# ENERGIS_Rack-PDU_1_1_0.net
KiCad netlist of a schematic drawn in EAGLE
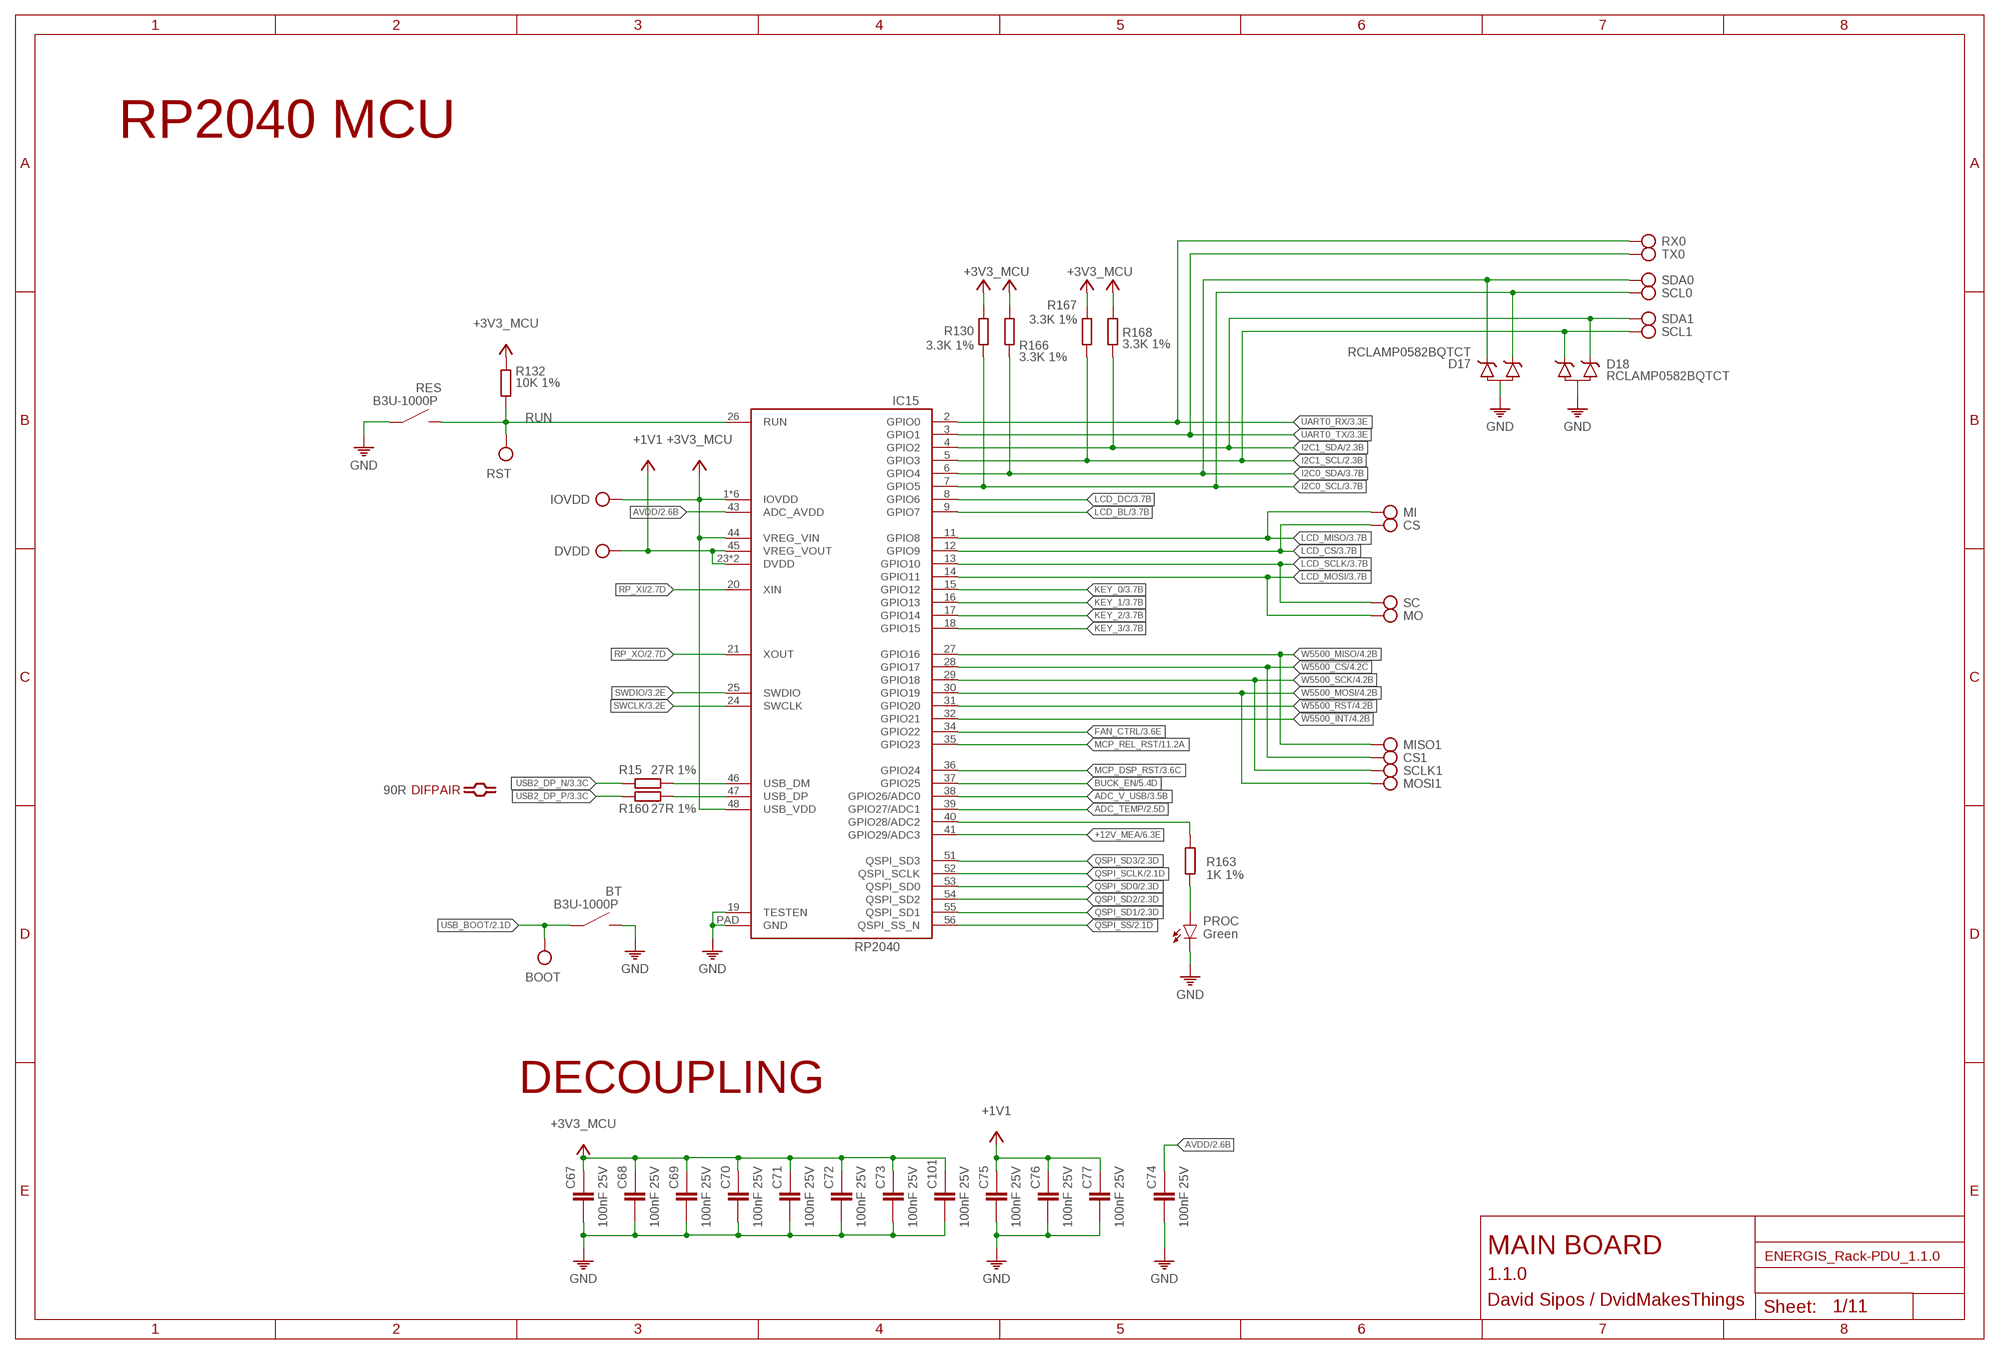
[diagram p0: schematic, sheet 1]
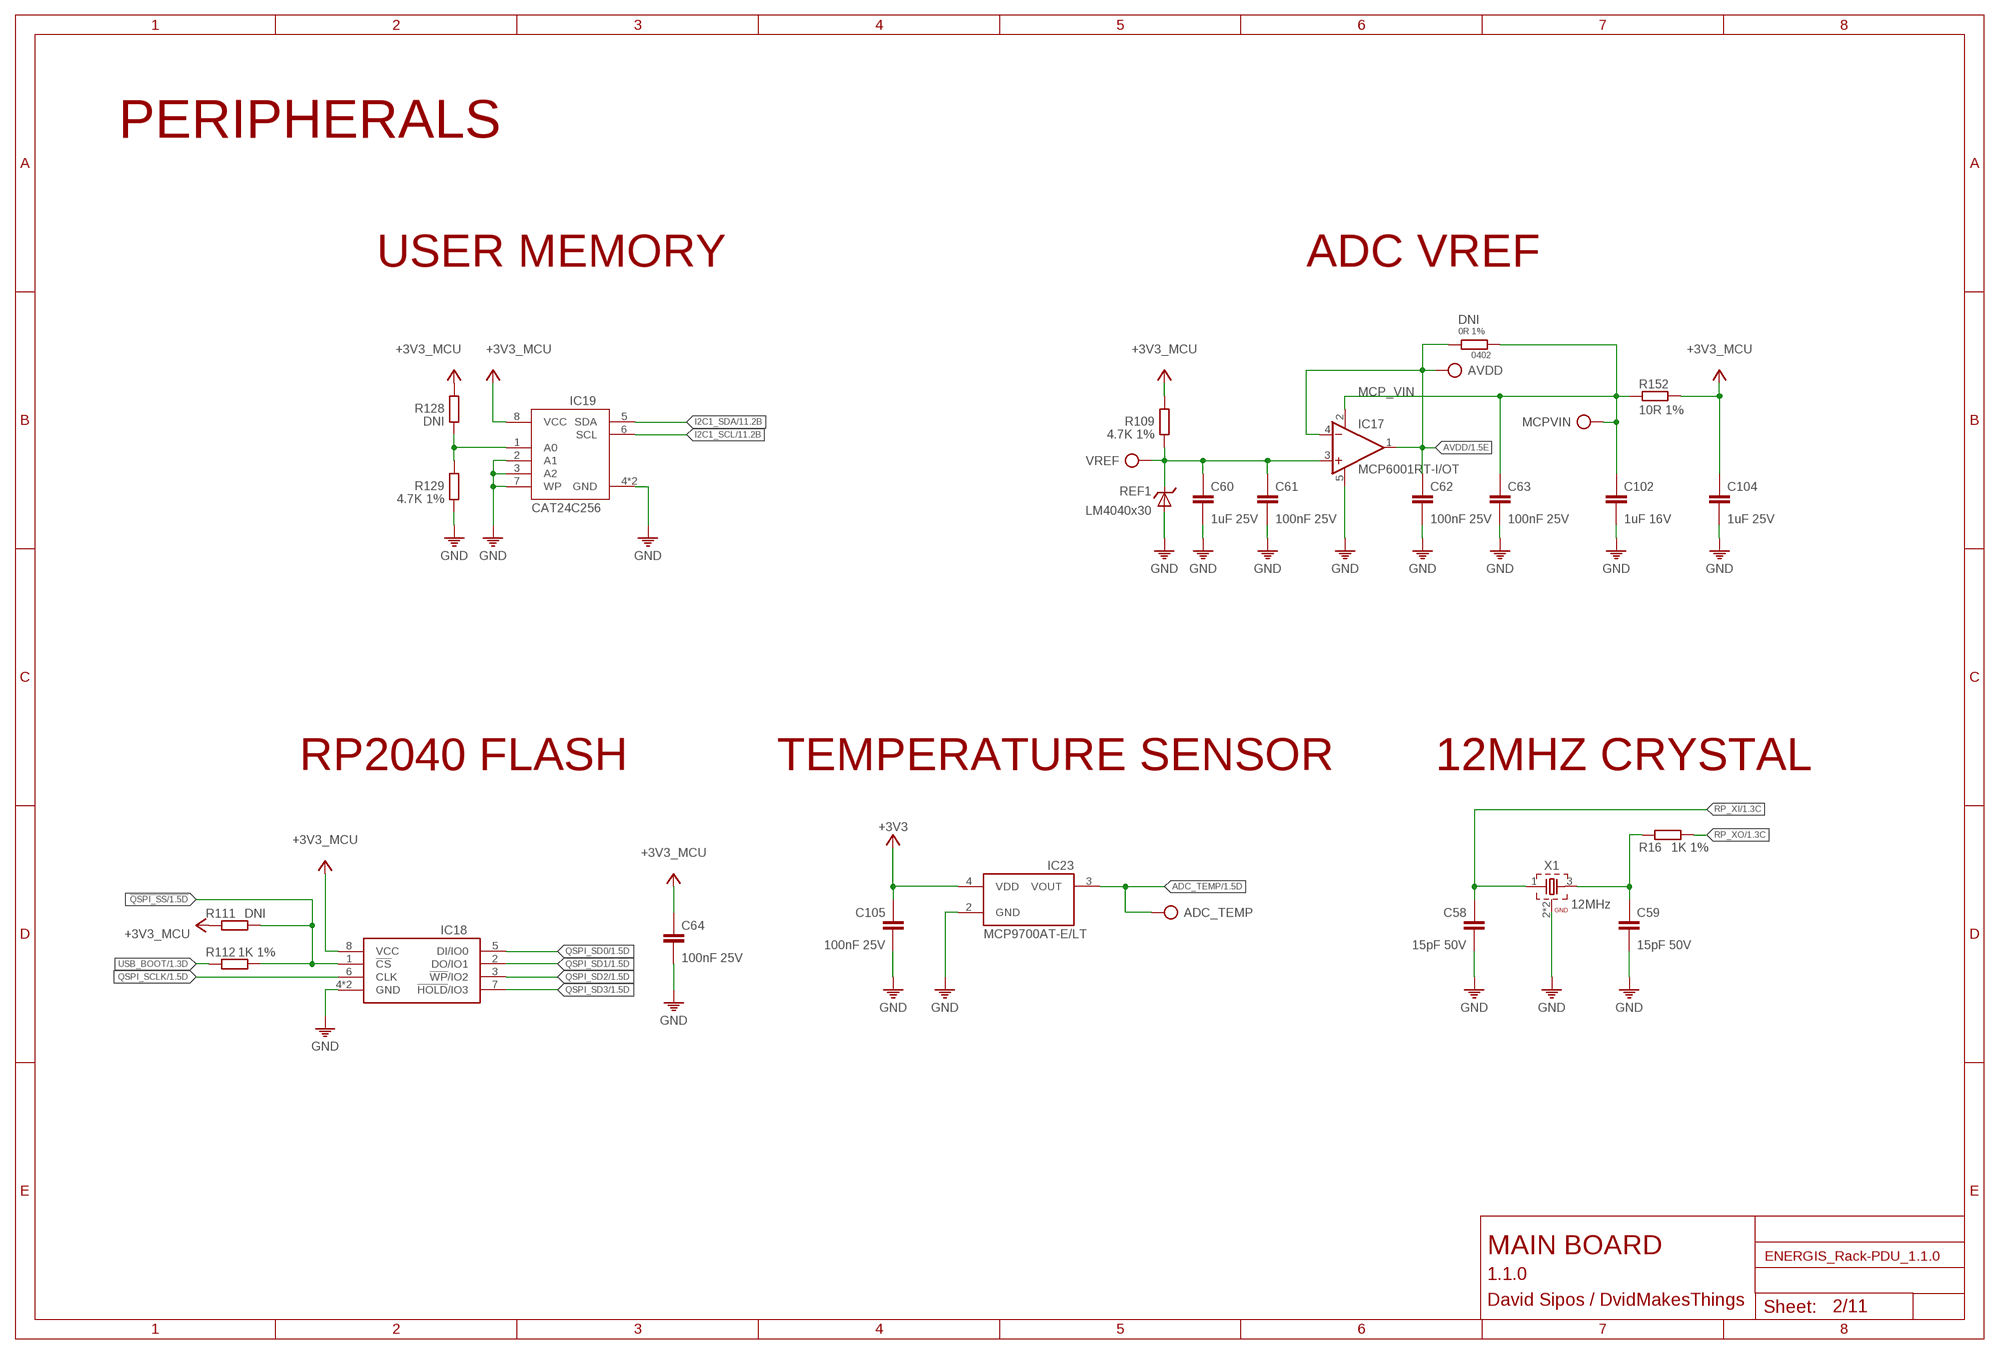
[diagram p1: schematic, sheet 2]
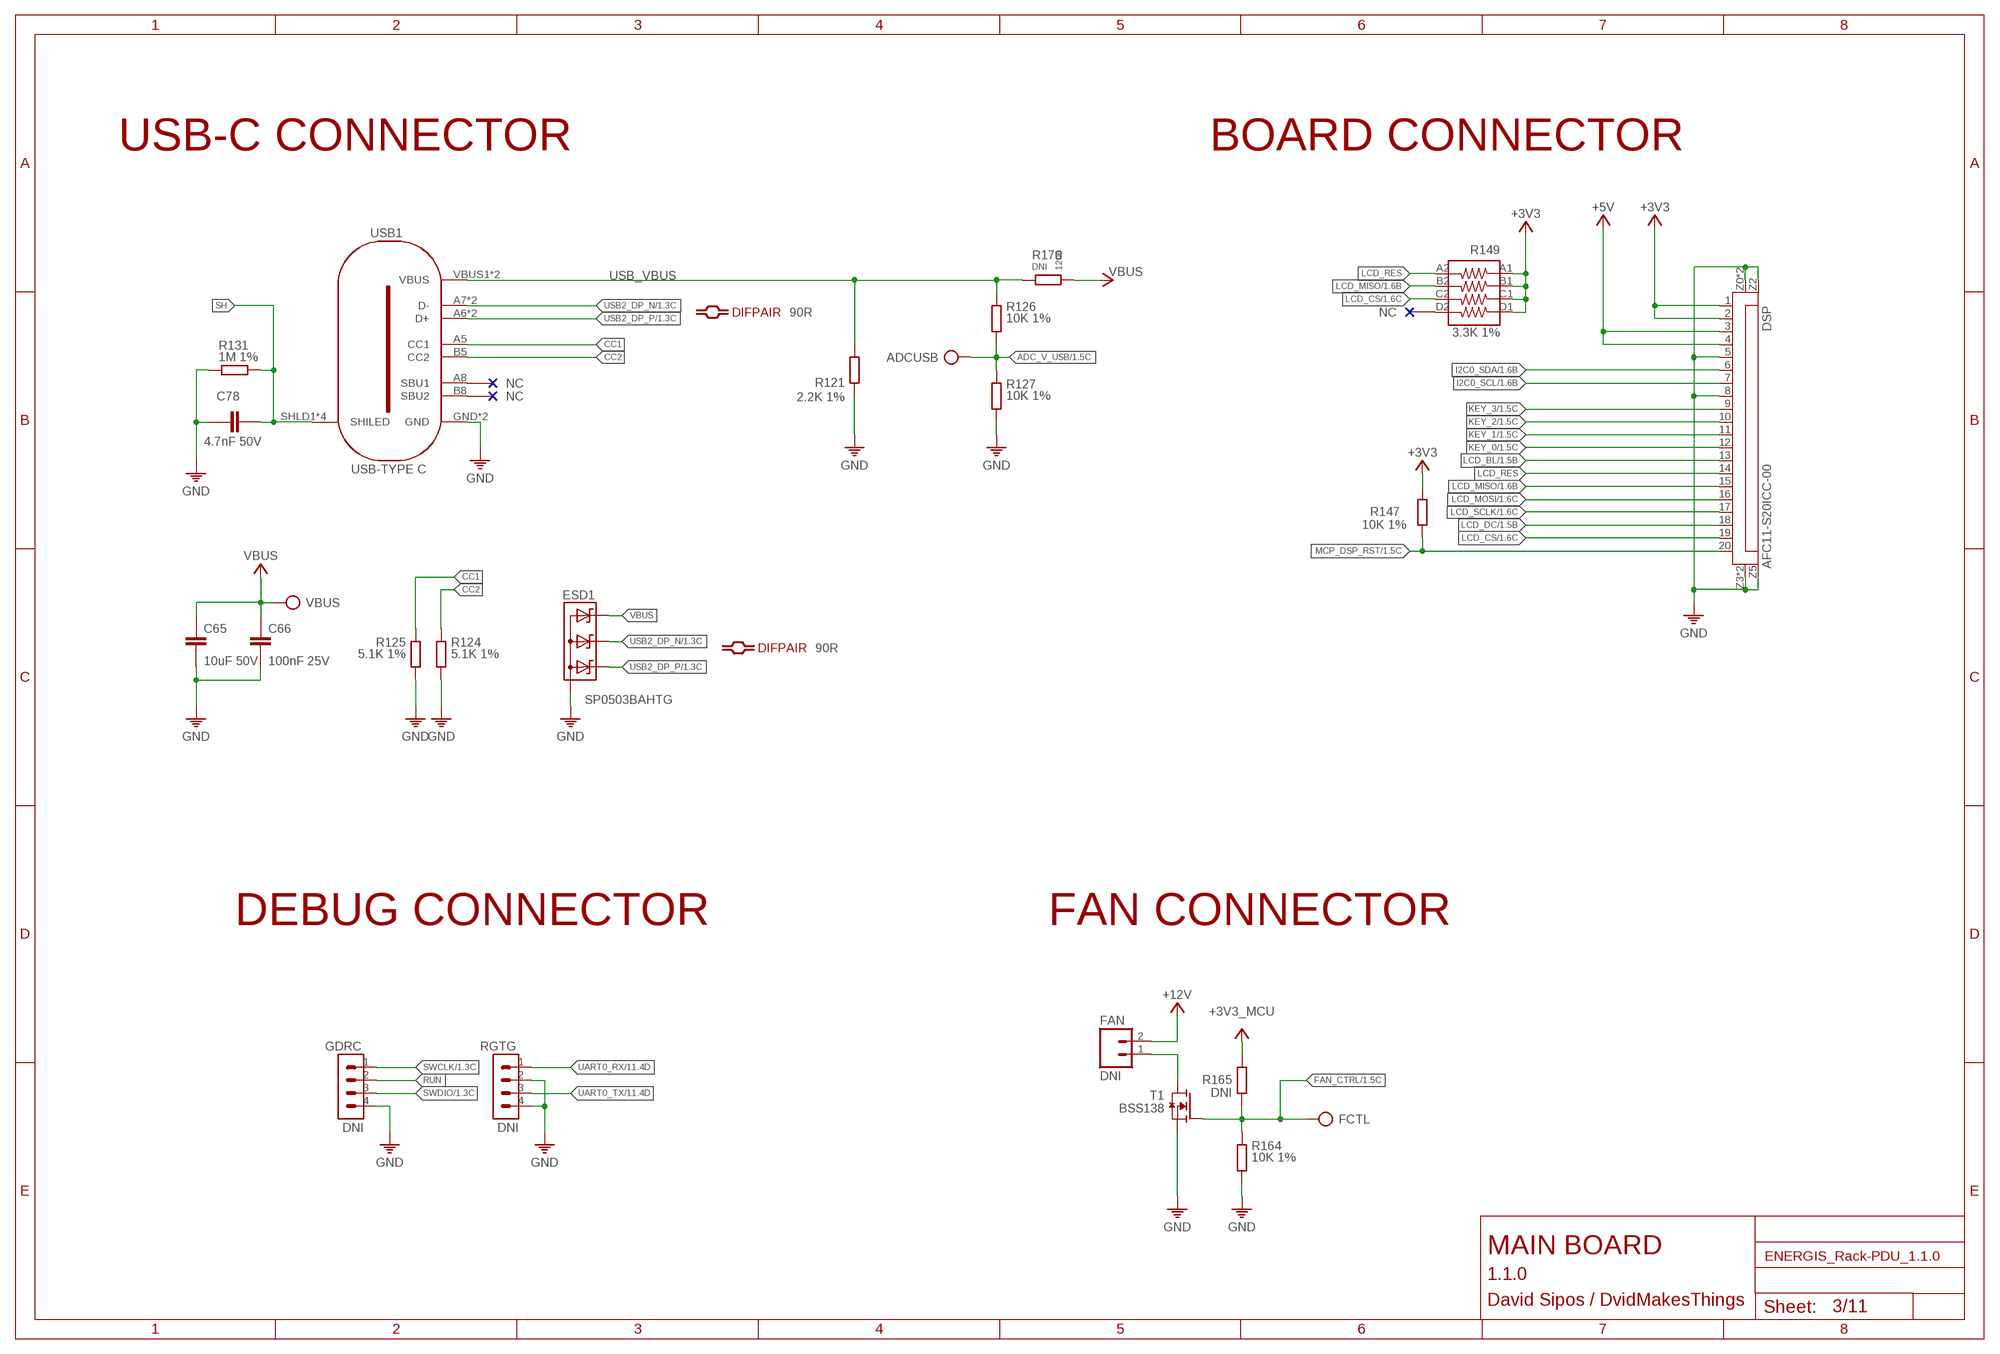
[diagram p2: schematic, sheet 3]
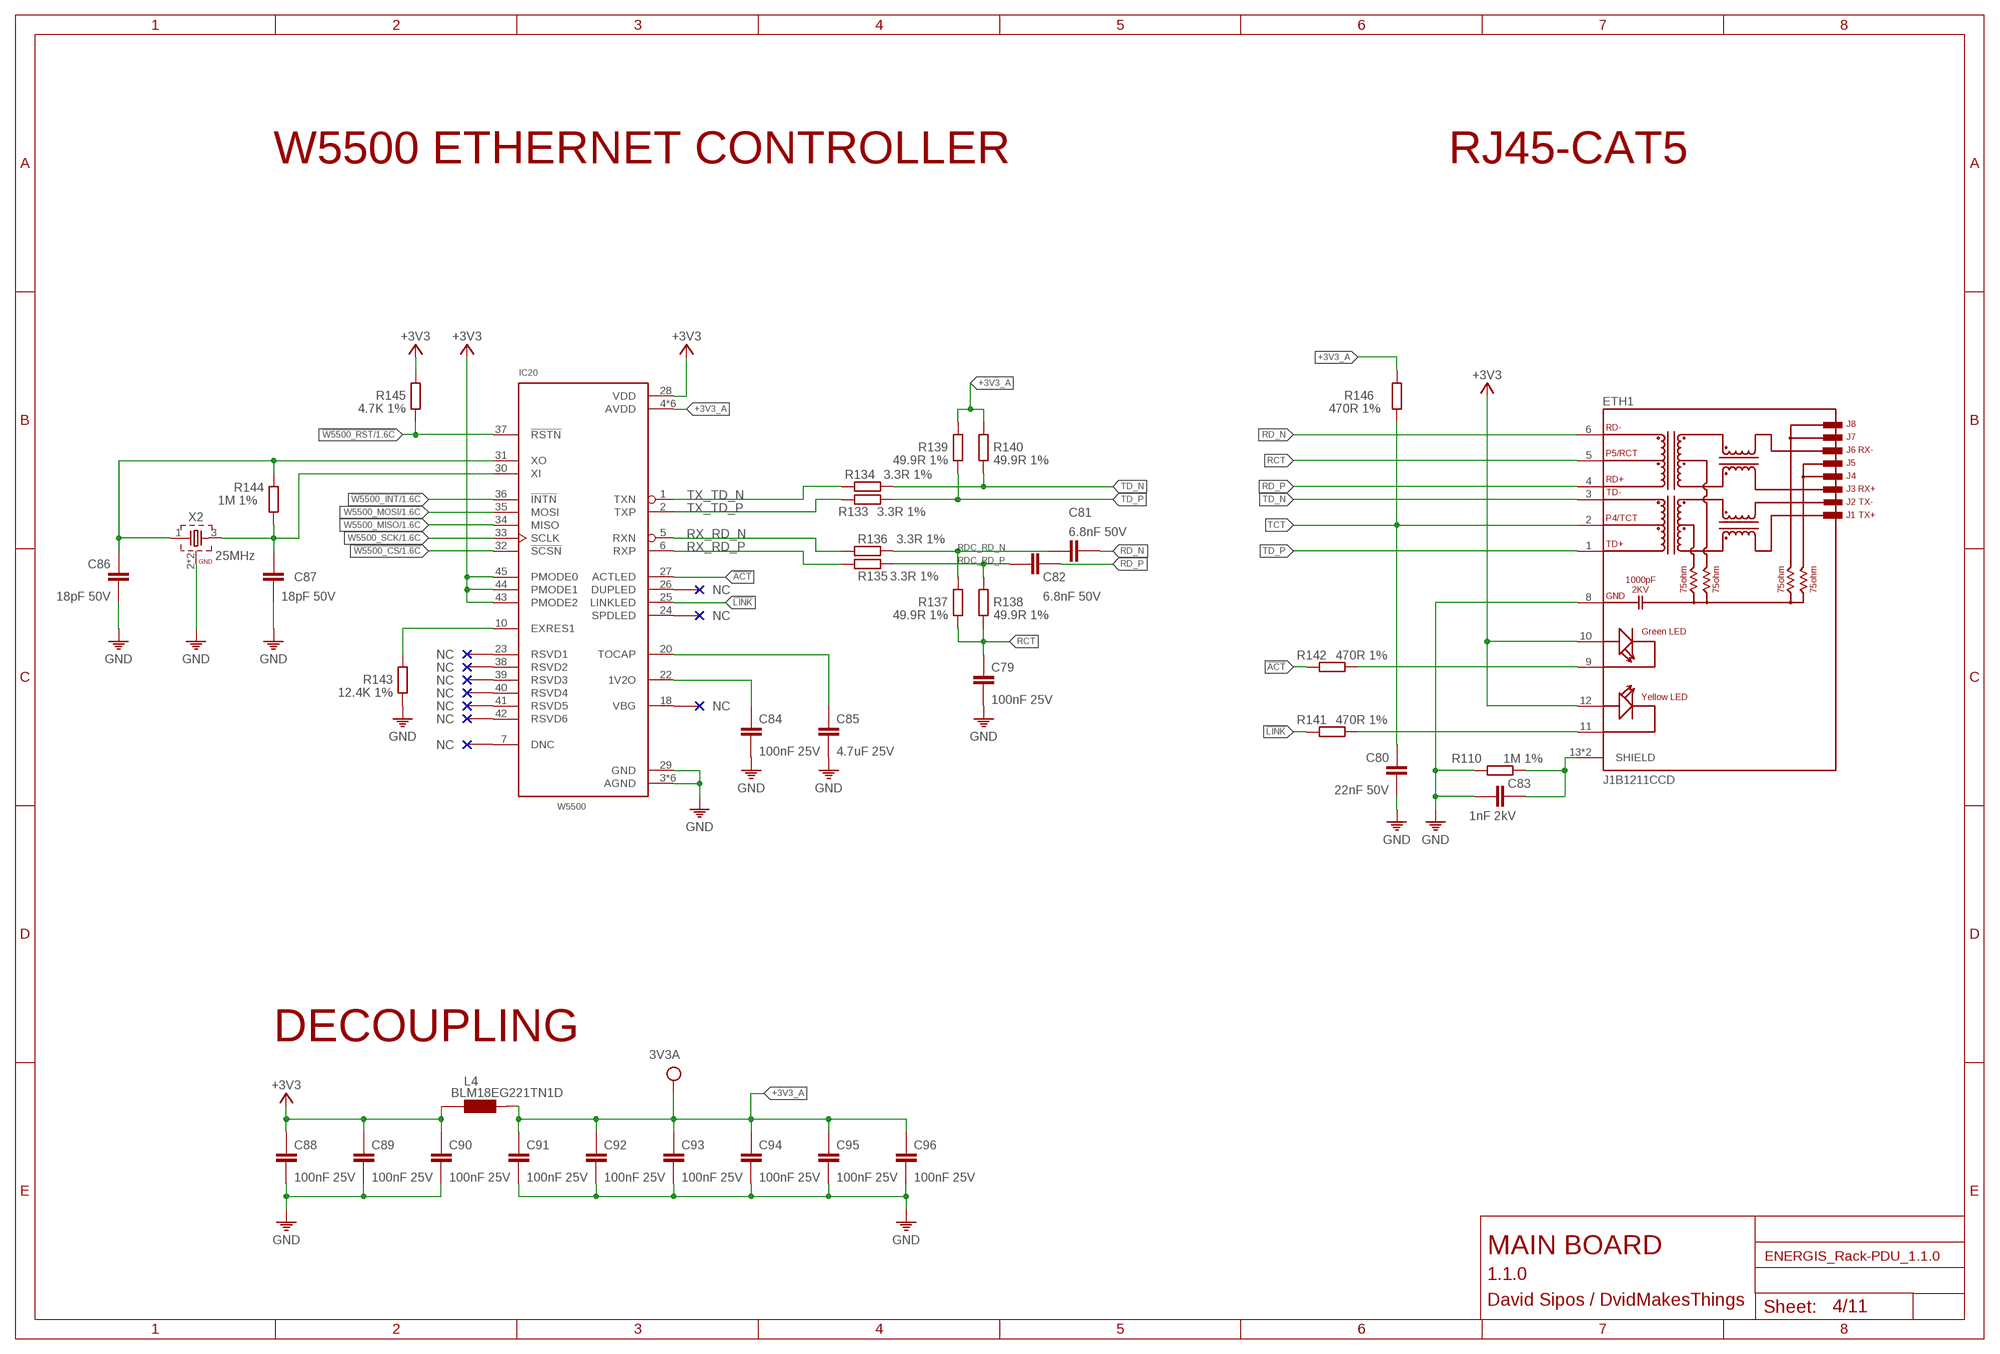
[diagram p3: schematic, sheet 4]
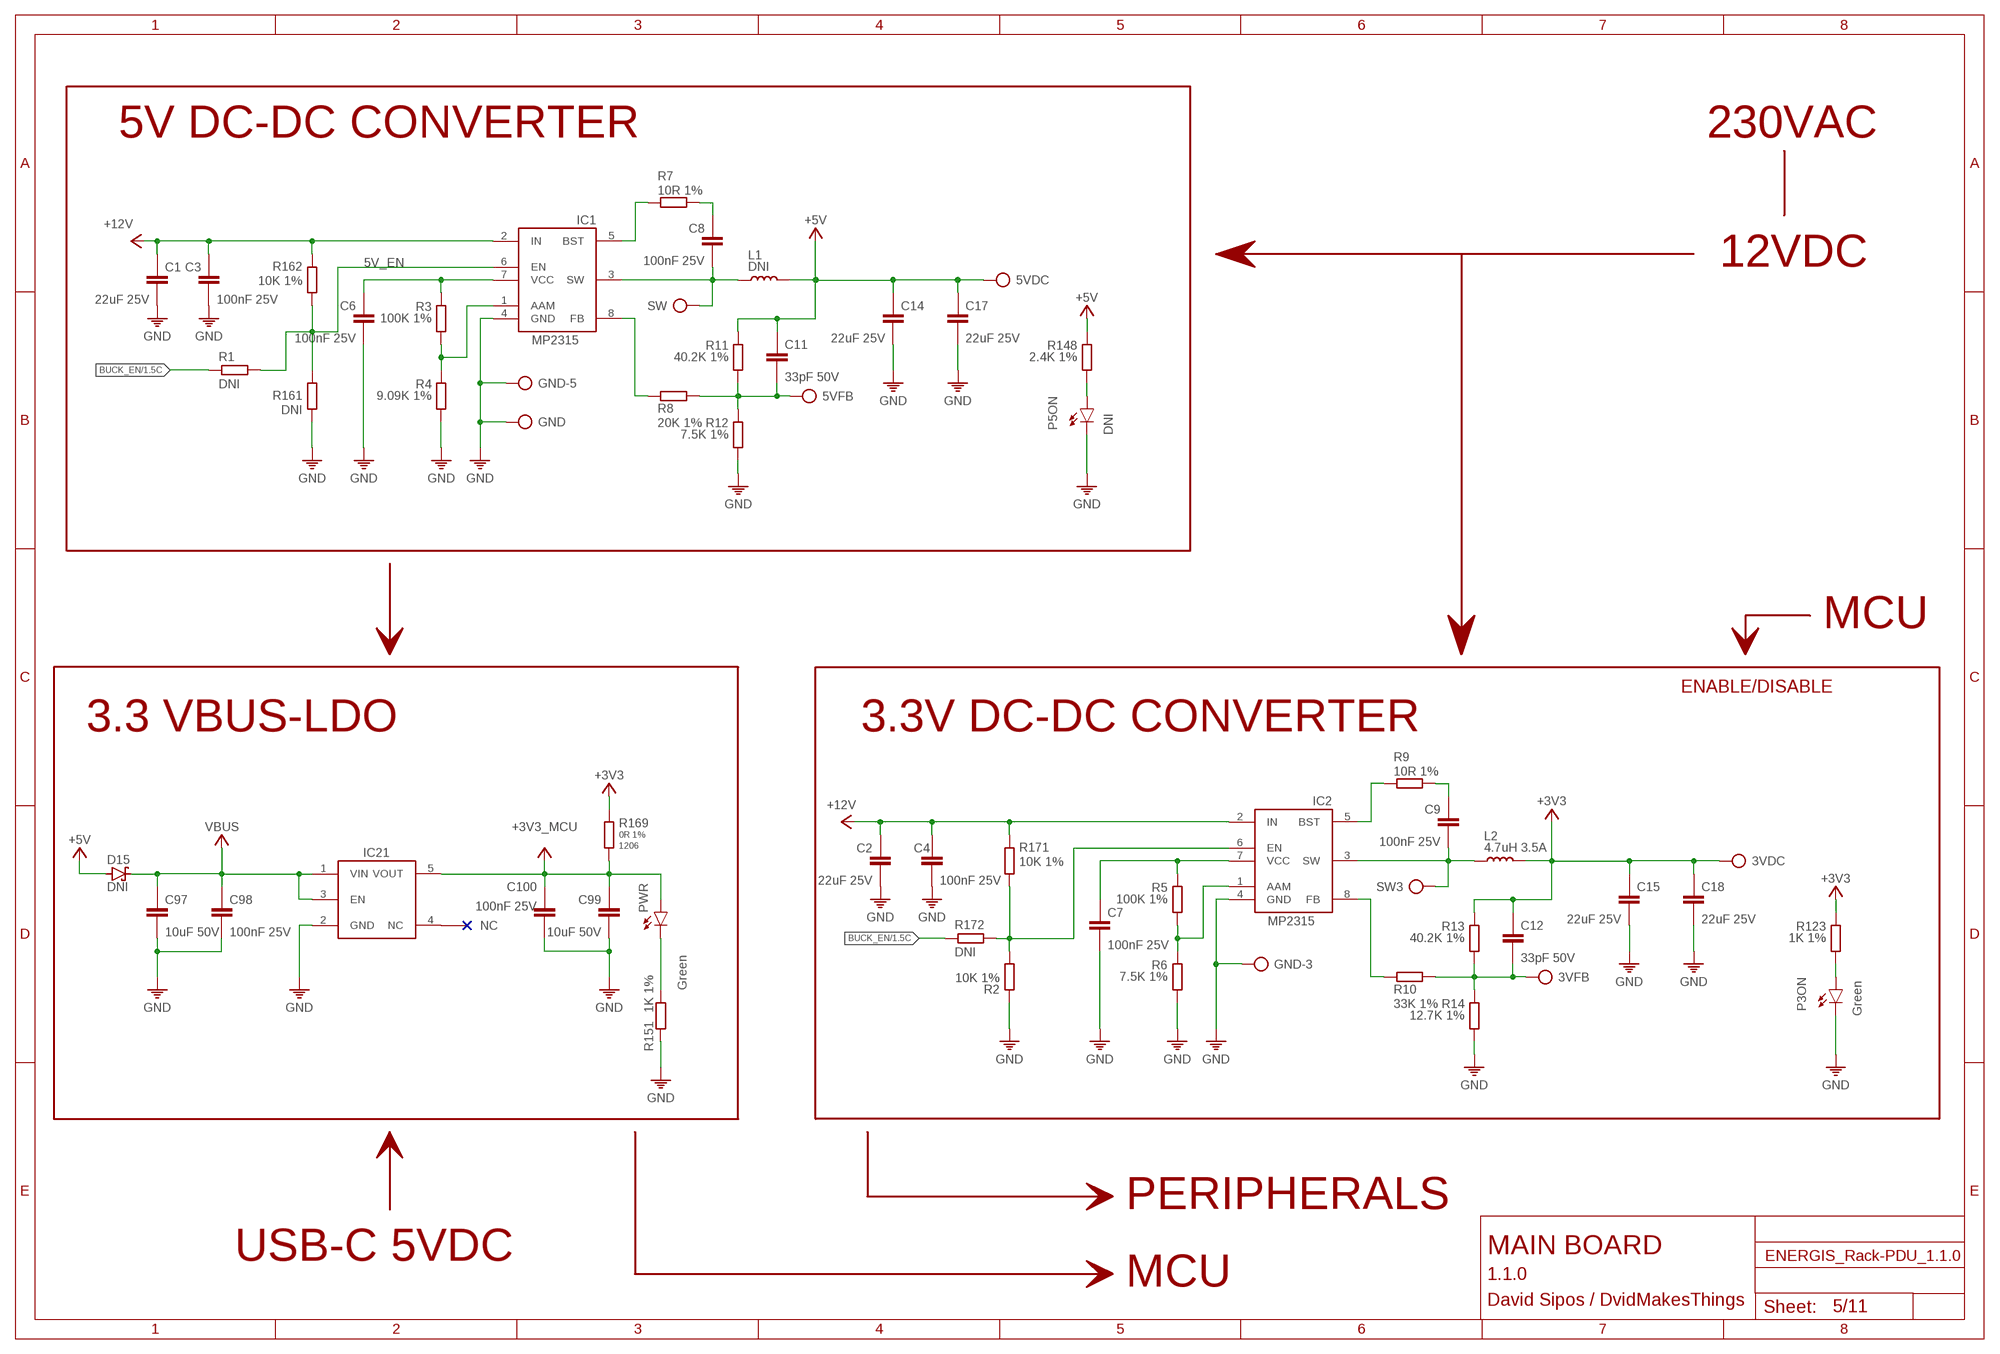
[diagram p4: schematic, sheet 5]
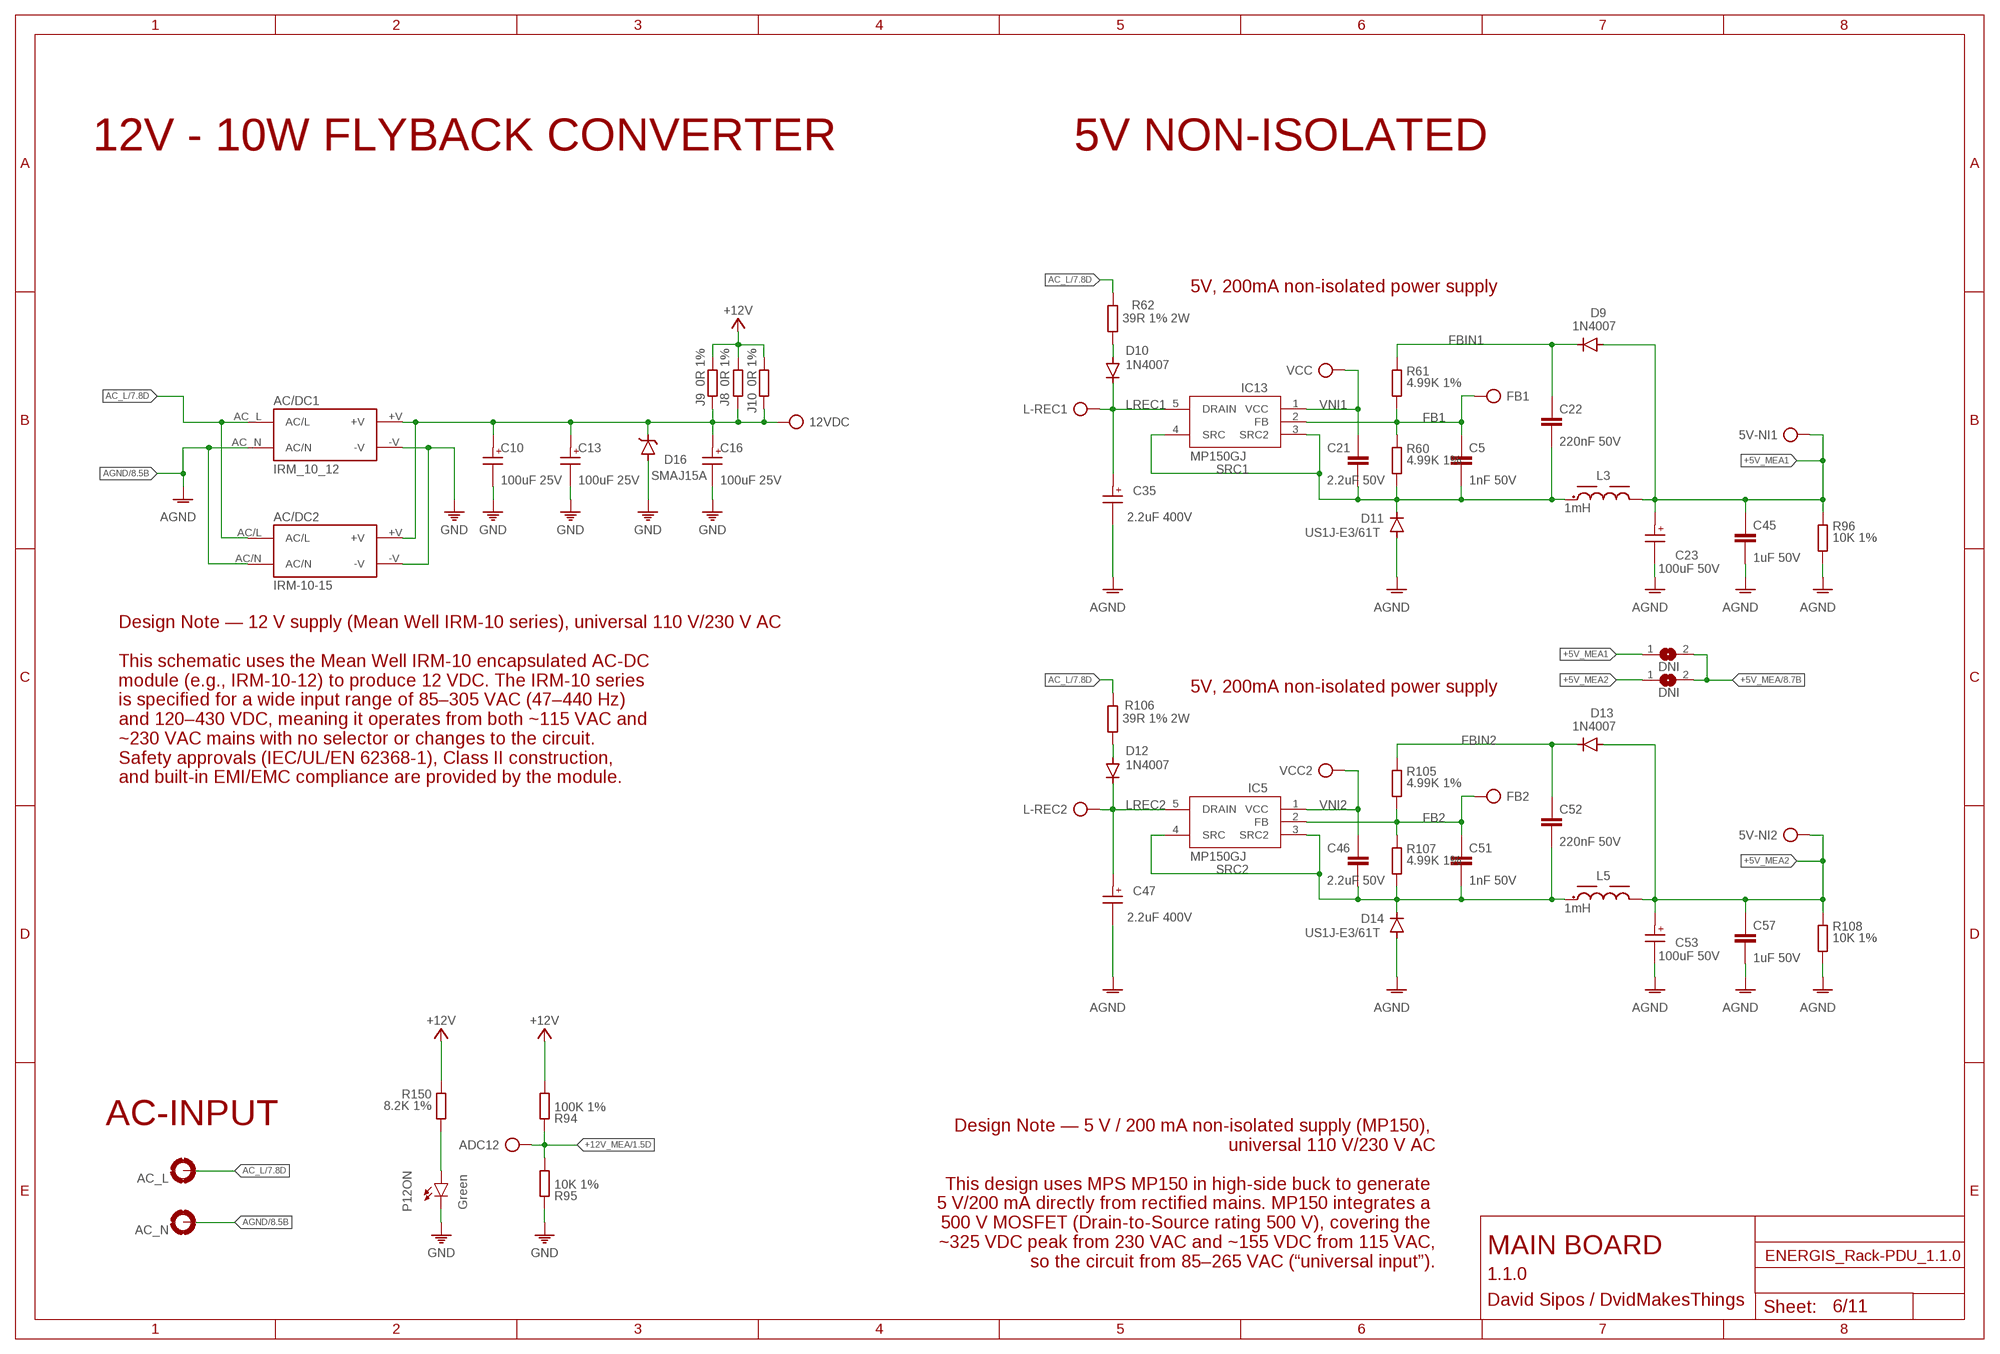
[diagram p5: schematic, sheet 6]
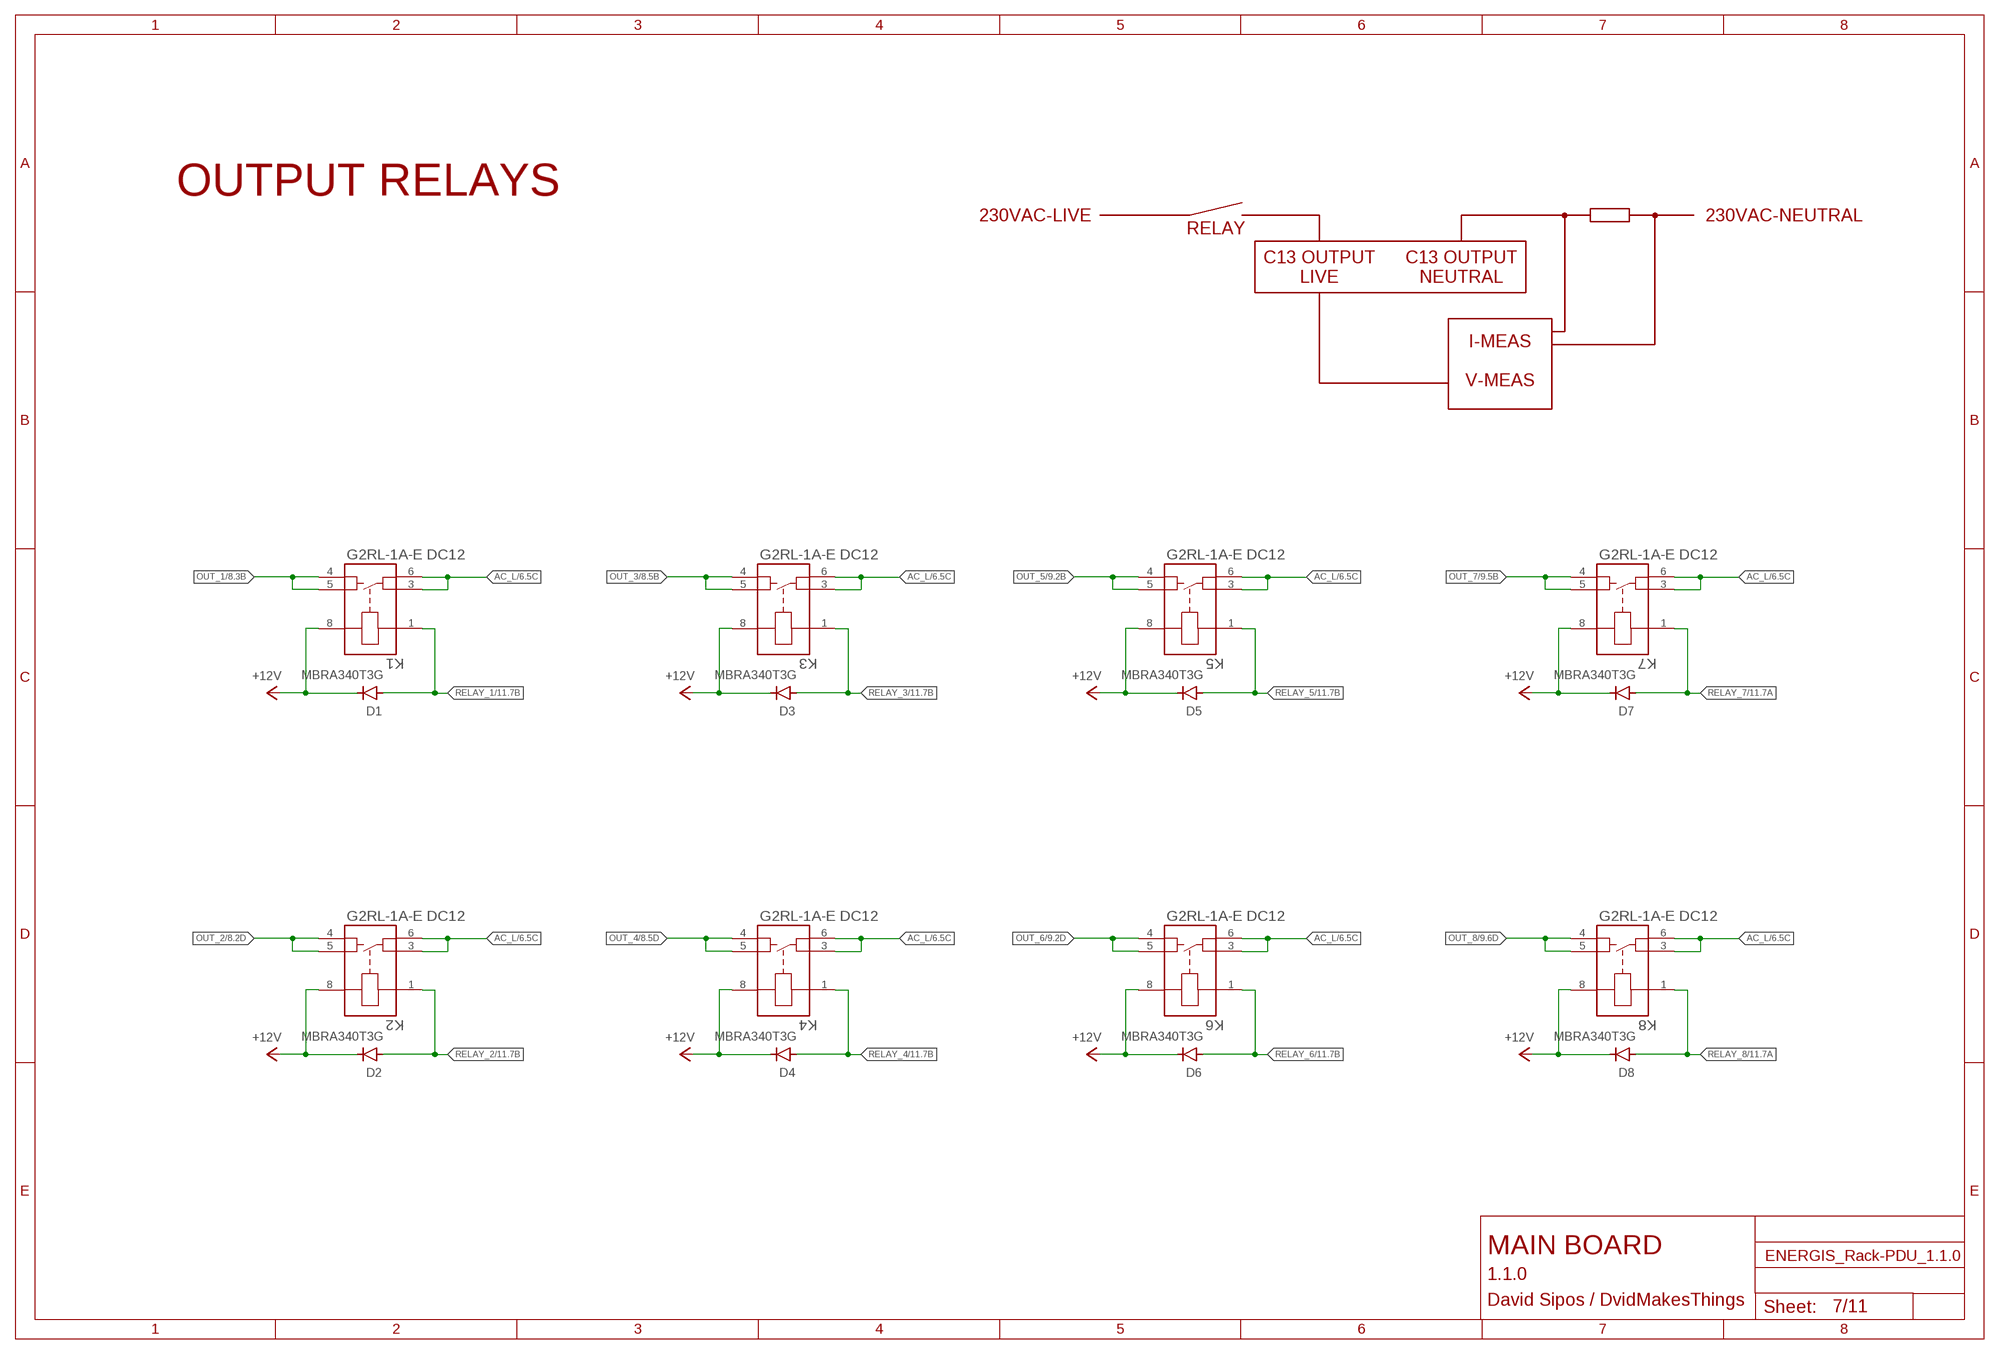
[diagram p6: schematic, sheet 7]
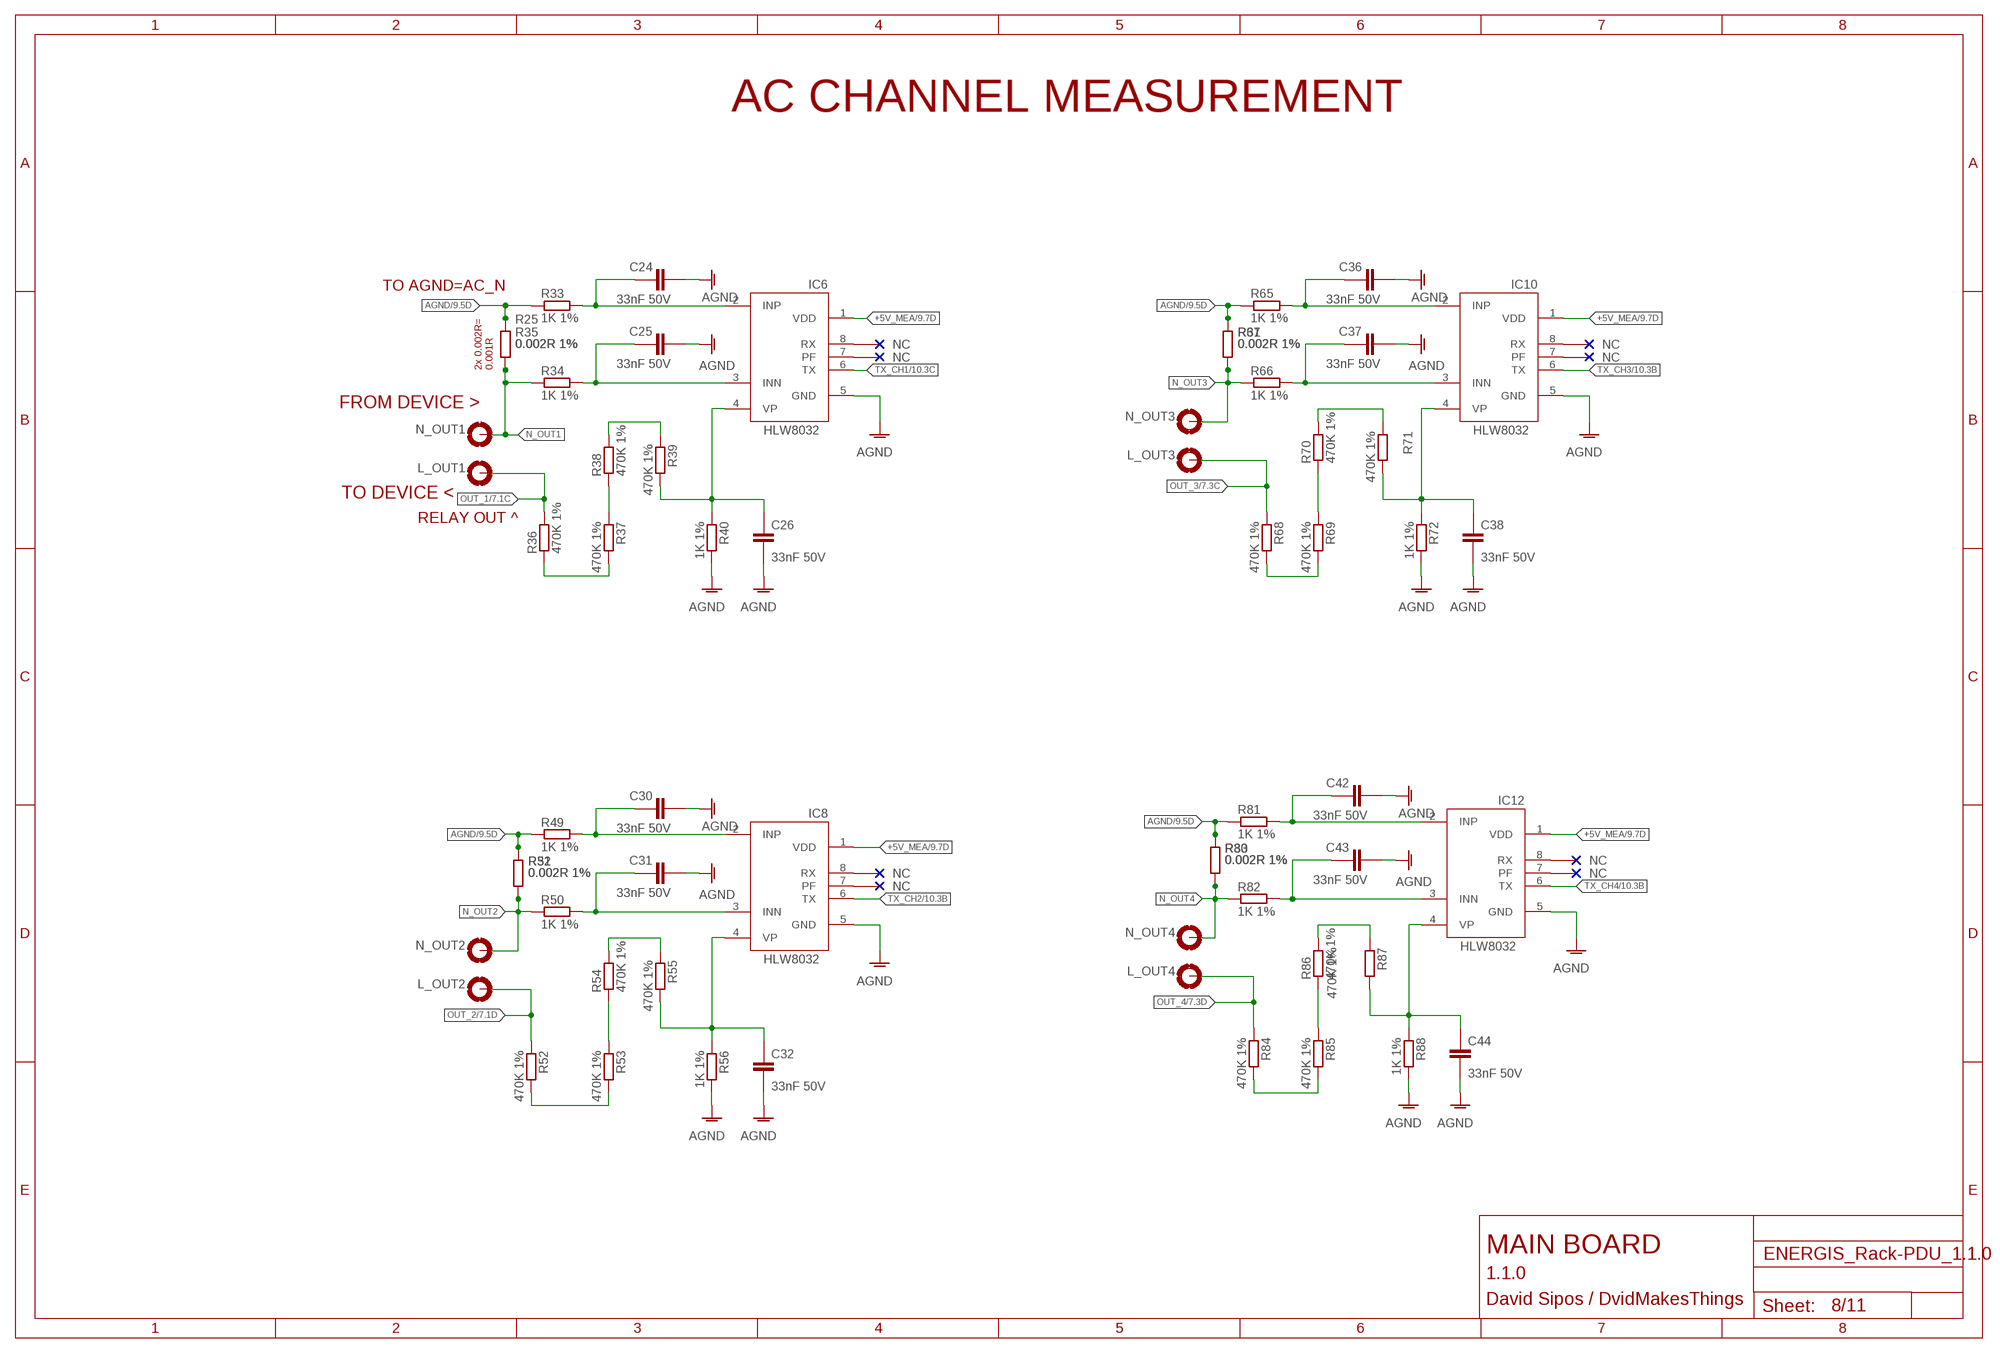
[diagram p7: schematic, sheet 8]
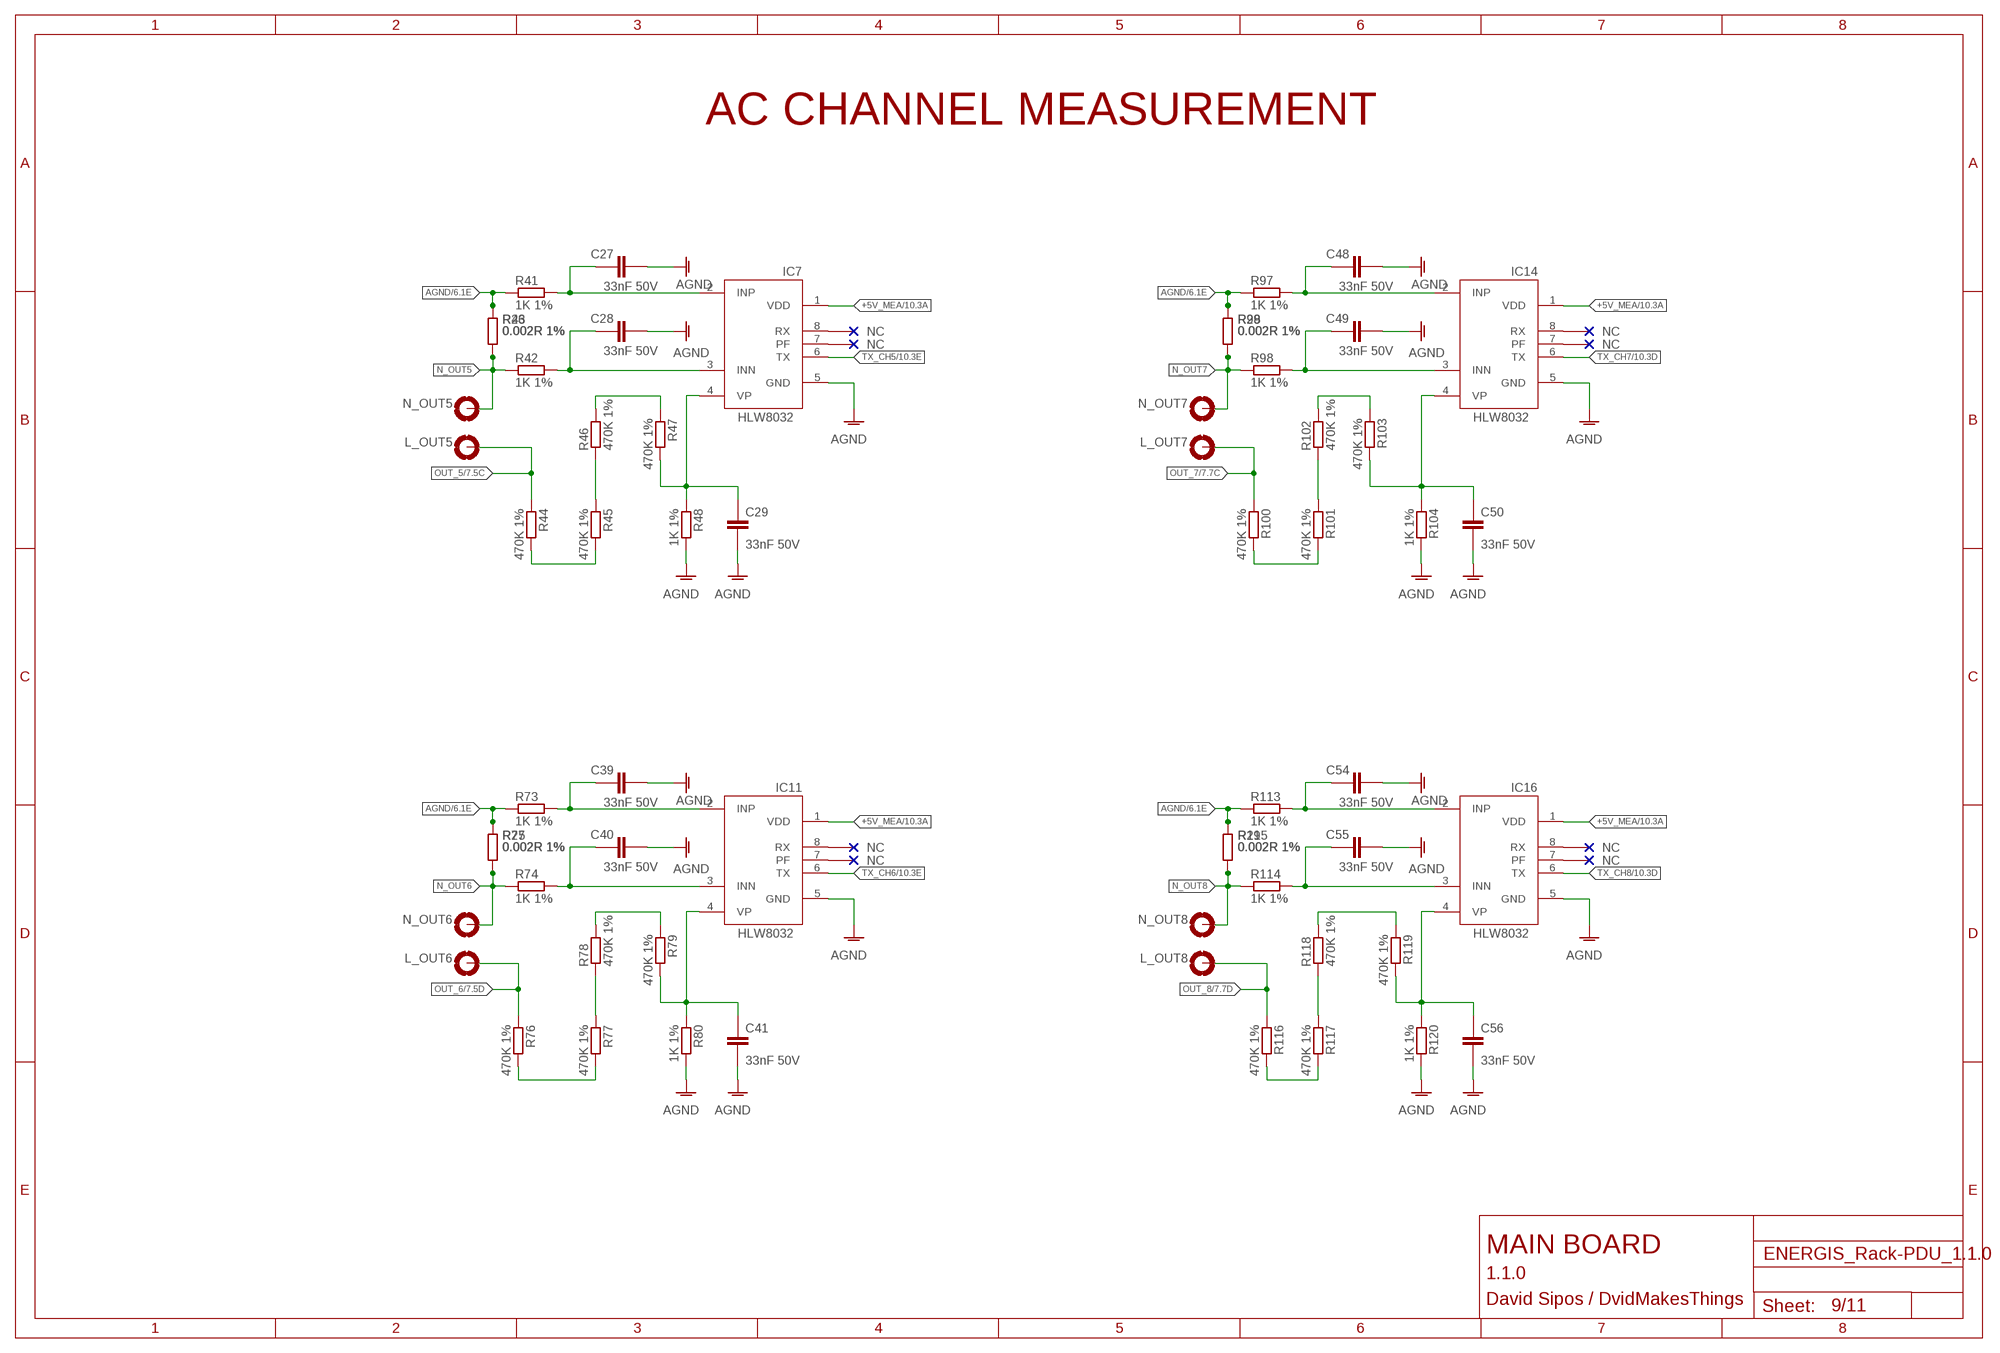
[diagram p8: schematic, sheet 9]
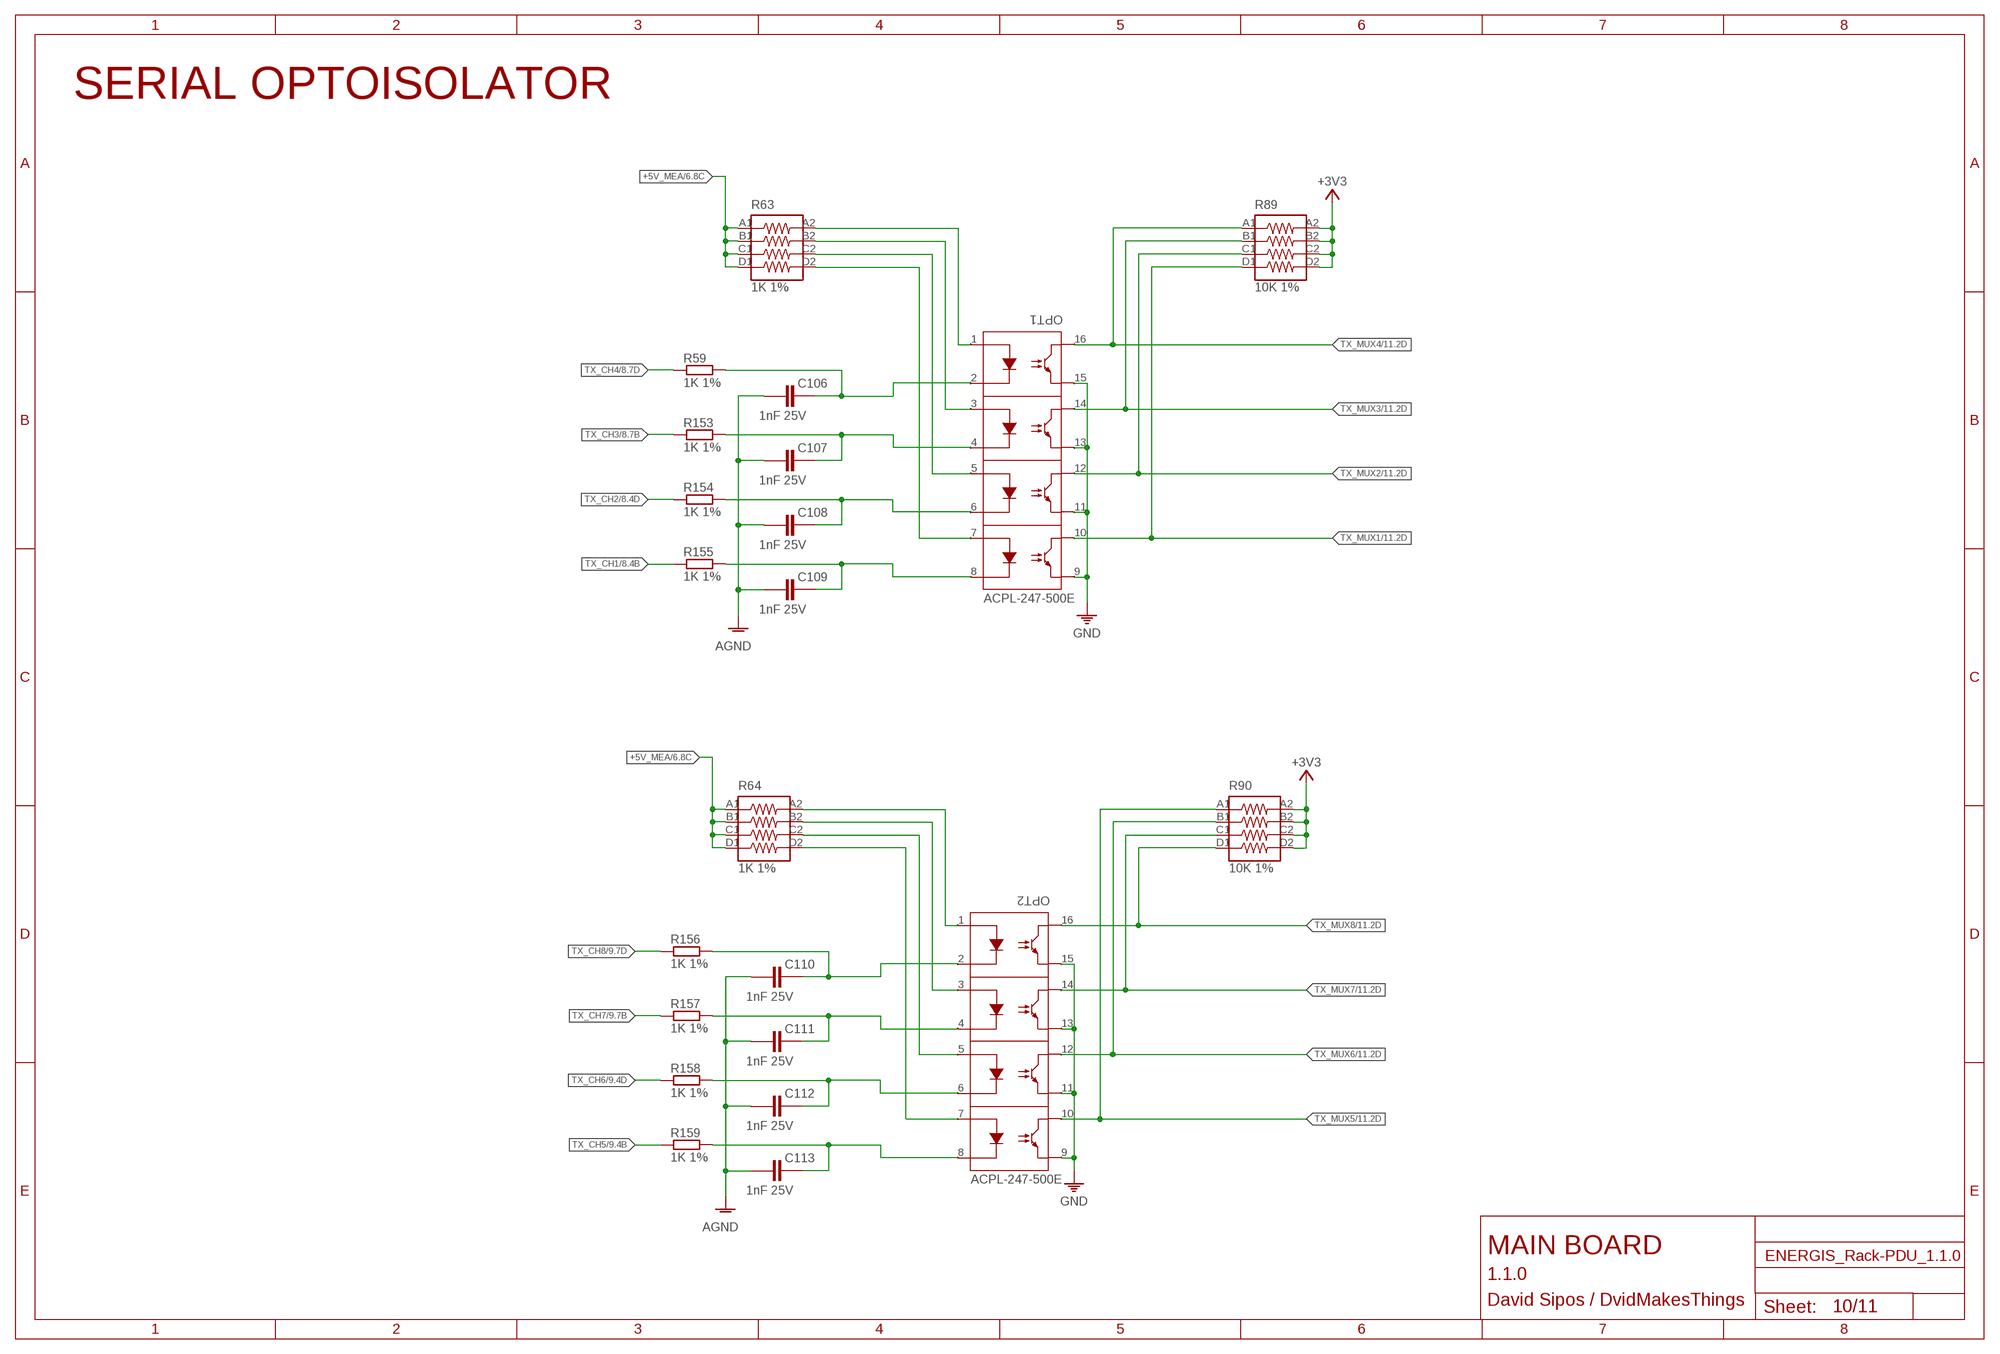
[diagram p9: schematic, sheet 10]
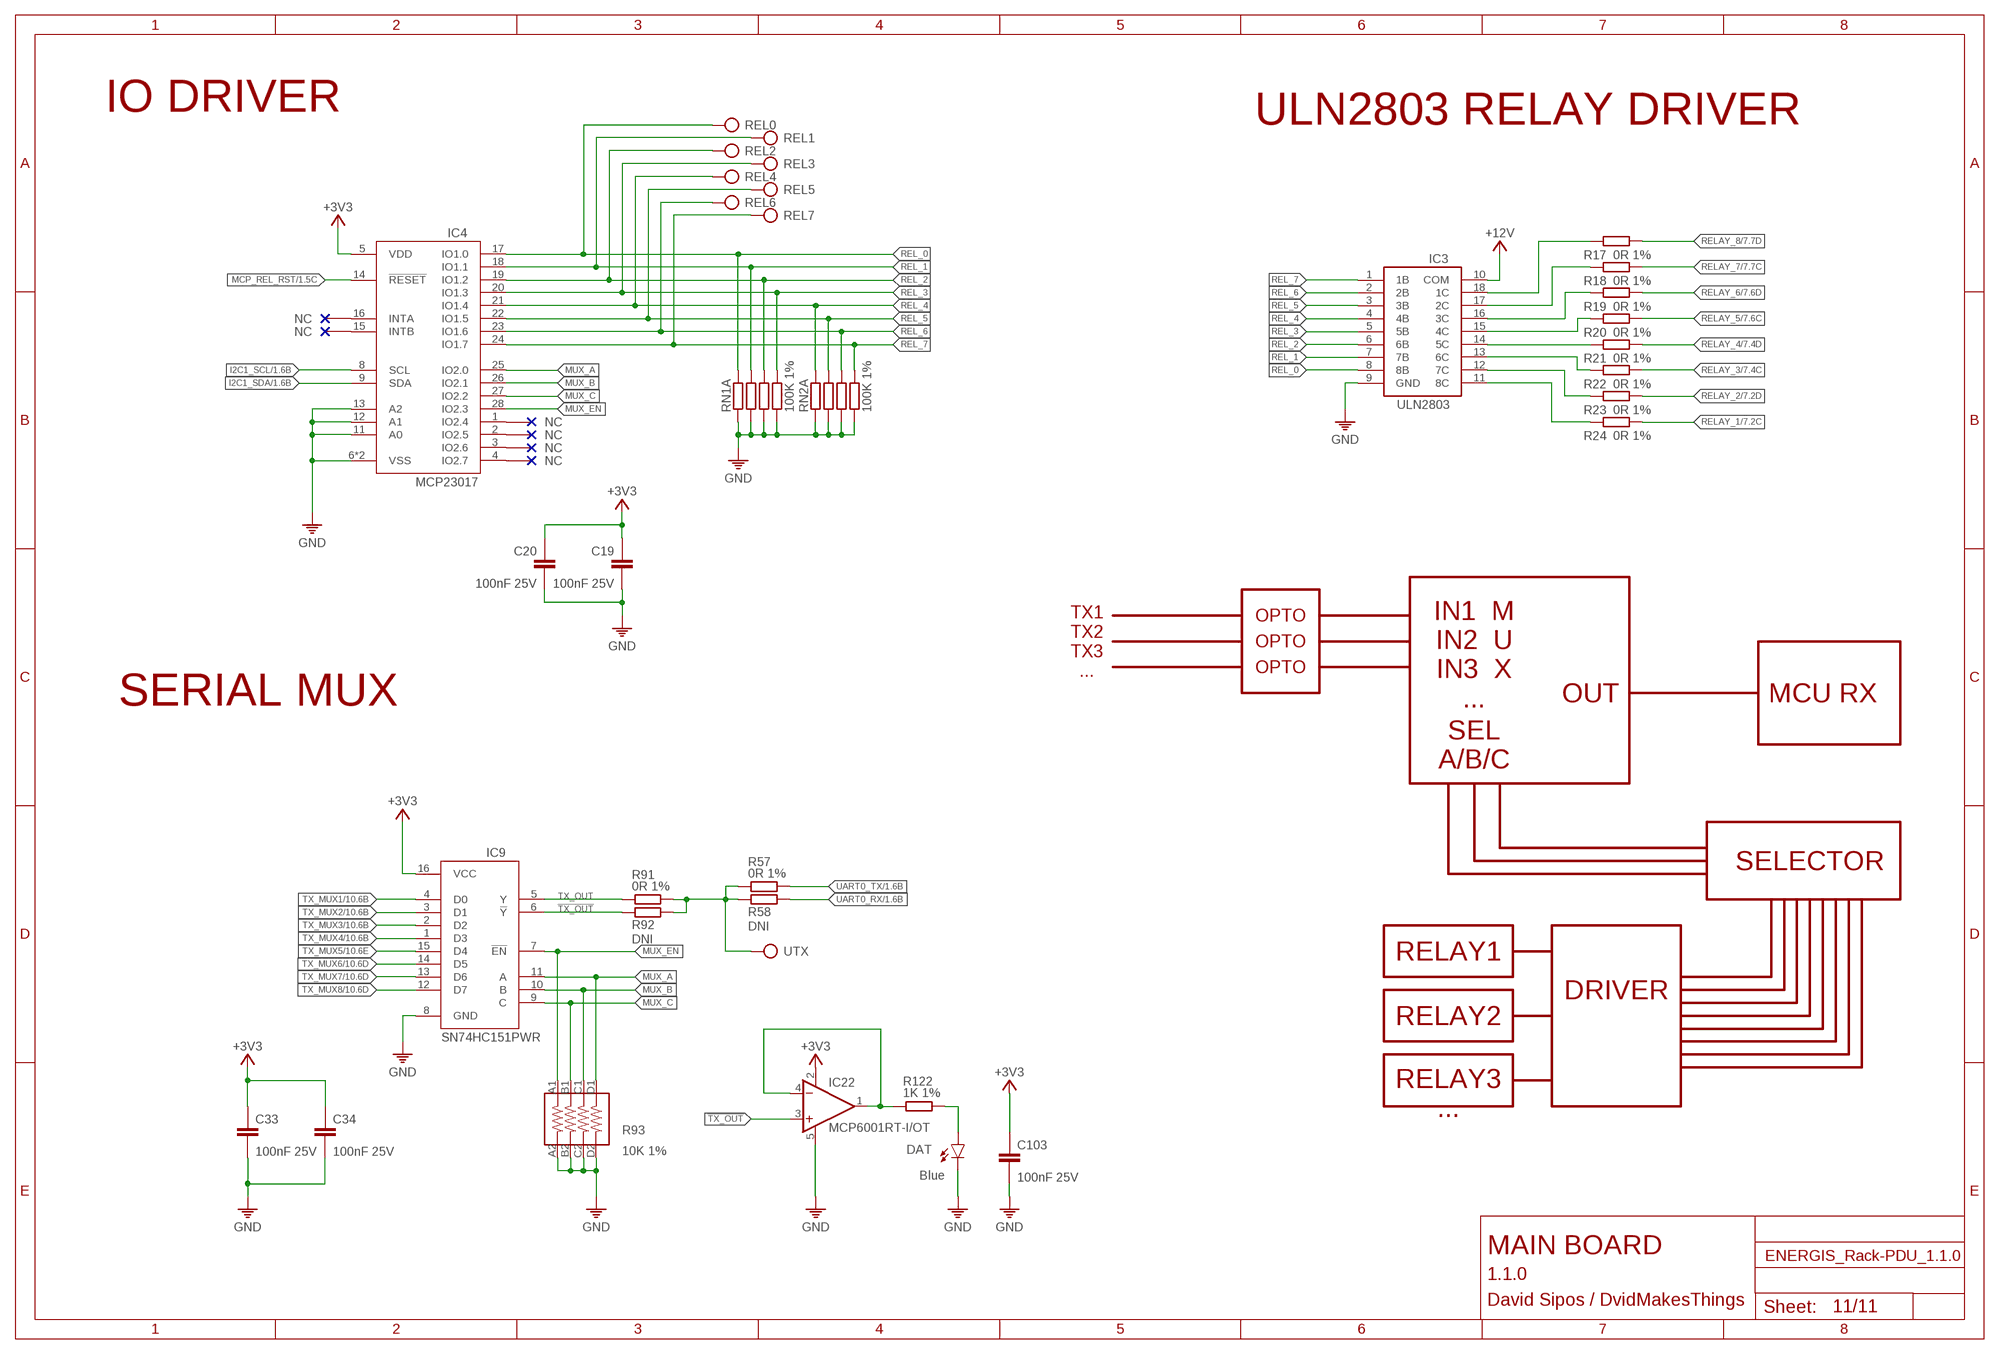
[diagram p10: schematic, sheet 11]

(export (version "E")
  (design (tool "Eeschema 10.0.6"))
  (components
    (comp (ref "BOOT")
      (value "DNI")
      (footprint "eagle-import:TP-ROUND")
      (libsource (lib "eagle-import") (part "TP-ROUND"))
    )
    (comp (ref "BT")
      (value "B3U-1000P")
      (footprint "eagle-import:B3U-1000P")
      (fields
        (field (name "HQ_PART") "SW0036094 ")
        (field (name "LCSC_PART") "C231329")
        (field (name "MANUFACTURER") "Omron")
      )
      (libsource (lib "eagle-import") (part "B3U-1000P"))
    )
    (comp (ref "C67")
      (value "100nF 25V")
      (footprint "eagle-import:0201")
      (fields
        (field (name "HQ_PART") "CA0183221")
        (field (name "LCSC_PART") "C76939")
        (field (name "MANUFACTURER") "Samsung")
      )
      (libsource (lib "eagle-import") (part "100NF-25V-0201"))
    )
    (comp (ref "C68")
      (value "100nF 25V")
      (footprint "eagle-import:0201")
      (fields
        (field (name "HQ_PART") "CA0183221")
        (field (name "LCSC_PART") "C76939")
        (field (name "MANUFACTURER") "Samsung")
      )
      (libsource (lib "eagle-import") (part "100NF-25V-0201"))
    )
    (comp (ref "C69")
      (value "100nF 25V")
      (footprint "eagle-import:0201")
      (fields
        (field (name "HQ_PART") "CA0183221")
        (field (name "LCSC_PART") "C76939")
        (field (name "MANUFACTURER") "Samsung")
      )
      (libsource (lib "eagle-import") (part "100NF-25V-0201"))
    )
    (comp (ref "C70")
      (value "100nF 25V")
      (footprint "eagle-import:0201")
      (fields
        (field (name "HQ_PART") "CA0183221")
        (field (name "LCSC_PART") "C76939")
        (field (name "MANUFACTURER") "Samsung")
      )
      (libsource (lib "eagle-import") (part "100NF-25V-0201"))
    )
    (comp (ref "C71")
      (value "100nF 25V")
      (footprint "eagle-import:0201")
      (fields
        (field (name "HQ_PART") "CA0183221")
        (field (name "LCSC_PART") "C76939")
        (field (name "MANUFACTURER") "Samsung")
      )
      (libsource (lib "eagle-import") (part "100NF-25V-0201"))
    )
    (comp (ref "C72")
      (value "100nF 25V")
      (footprint "eagle-import:0201")
      (fields
        (field (name "HQ_PART") "CA0183221")
        (field (name "LCSC_PART") "C76939")
        (field (name "MANUFACTURER") "Samsung")
      )
      (libsource (lib "eagle-import") (part "100NF-25V-0201"))
    )
    (comp (ref "C73")
      (value "100nF 25V")
      (footprint "eagle-import:0201")
      (fields
        (field (name "HQ_PART") "CA0183221")
        (field (name "LCSC_PART") "C76939")
        (field (name "MANUFACTURER") "Samsung")
      )
      (libsource (lib "eagle-import") (part "100NF-25V-0201"))
    )
    (comp (ref "C74")
      (value "100nF 25V")
      (footprint "eagle-import:0201")
      (fields
        (field (name "HQ_PART") "CA0183221")
        (field (name "LCSC_PART") "C76939")
        (field (name "MANUFACTURER") "Samsung")
      )
      (libsource (lib "eagle-import") (part "100NF-25V-0201"))
    )
    (comp (ref "C75")
      (value "100nF 25V")
      (footprint "eagle-import:0201")
      (fields
        (field (name "HQ_PART") "CA0183221")
        (field (name "LCSC_PART") "C76939")
        (field (name "MANUFACTURER") "Samsung")
      )
      (libsource (lib "eagle-import") (part "100NF-25V-0201"))
    )
    (comp (ref "C76")
      (value "100nF 25V")
      (footprint "eagle-import:0201")
      (fields
        (field (name "HQ_PART") "CA0183221")
        (field (name "LCSC_PART") "C76939")
        (field (name "MANUFACTURER") "Samsung")
      )
      (libsource (lib "eagle-import") (part "100NF-25V-0201"))
    )
    (comp (ref "C77")
      (value "100nF 25V")
      (footprint "eagle-import:0201")
      (fields
        (field (name "HQ_PART") "CA0183221")
        (field (name "LCSC_PART") "C76939")
        (field (name "MANUFACTURER") "Samsung")
      )
      (libsource (lib "eagle-import") (part "100NF-25V-0201"))
    )
    (comp (ref "C101")
      (value "100nF 25V")
      (footprint "eagle-import:0201")
      (fields
        (field (name "HQ_PART") "CA0183221")
        (field (name "LCSC_PART") "C76939")
        (field (name "MANUFACTURER") "Samsung")
      )
      (libsource (lib "eagle-import") (part "100NF-25V-0201"))
    )
    (comp (ref "CS")
      (value "DNI")
      (footprint "eagle-import:TP-ROUND")
      (libsource (lib "eagle-import") (part "TP-ROUND"))
    )
    (comp (ref "CS1")
      (value "DNI")
      (footprint "eagle-import:TP-ROUND")
      (libsource (lib "eagle-import") (part "TP-ROUND"))
    )
    (comp (ref "D17")
      (value "RCLAMP0582BQTCT")
      (footprint "eagle-import:SC75")
      (fields
        (field (name "HQ_PART") "PD0007296")
        (field (name "LCSC_PART") "C841193")
        (field (name "MANUFACTURER") "SEMTECH")
      )
      (libsource (lib "eagle-import") (part "RCLAMP0582BQTCT-"))
    )
    (comp (ref "D18")
      (value "RCLAMP0582BQTCT")
      (footprint "eagle-import:SC75")
      (fields
        (field (name "HQ_PART") "PD0007296")
        (field (name "LCSC_PART") "C841193")
        (field (name "MANUFACTURER") "SEMTECH")
      )
      (libsource (lib "eagle-import") (part "RCLAMP0582BQTCT-"))
    )
    (comp (ref "DVDD")
      (value "DNI")
      (footprint "eagle-import:TP-ROUND")
      (libsource (lib "eagle-import") (part "TP-ROUND"))
    )
    (comp (ref "IC15")
      (value "RP2040")
      (footprint "eagle-import:QFN56")
      (fields
        (field (name "HQ_PART") "ZHLM0164739")
        (field (name "LCSC_PART") "C2040")
        (field (name "MANUFACTURER") "Raspberry Pi ")
      )
      (libsource (lib "eagle-import") (part "RP2040"))
    )
    (comp (ref "IOVDD")
      (value "DNI")
      (footprint "eagle-import:TP-ROUND")
      (libsource (lib "eagle-import") (part "TP-ROUND"))
    )
    (comp (ref "MI")
      (value "DNI")
      (footprint "eagle-import:TP-ROUND")
      (libsource (lib "eagle-import") (part "TP-ROUND"))
    )
    (comp (ref "MISO1")
      (value "DNI")
      (footprint "eagle-import:TP-ROUND")
      (libsource (lib "eagle-import") (part "TP-ROUND"))
    )
    (comp (ref "MO")
      (value "DNI")
      (footprint "eagle-import:TP-ROUND")
      (libsource (lib "eagle-import") (part "TP-ROUND"))
    )
    (comp (ref "MOSI1")
      (value "DNI")
      (footprint "eagle-import:TP-ROUND")
      (libsource (lib "eagle-import") (part "TP-ROUND"))
    )
    (comp (ref "PROC")
      (value "Green")
      (footprint "eagle-import:LED-0603")
      (fields
        (field (name "HQ_PART") "PH0010430")
        (field (name "LCSC_PART") "C965804")
        (field (name "MANUFACTURER") "Wurth")
      )
      (libsource (lib "eagle-import") (part "LED-GREENLED-0603"))
    )
    (comp (ref "R15")
      (value "27R 1%")
      (footprint "eagle-import:0201")
      (fields
        (field (name "HQ_PART") "RE0209327 ")
        (field (name "LCSC_PART") "C473051")
        (field (name "MANUFACTURER") "FH")
      )
      (libsource (lib "eagle-import") (part "27R-1%0201"))
    )
    (comp (ref "R130")
      (value "3.3K 1%")
      (footprint "eagle-import:0402")
      (fields
        (field (name "HQ_PART") "RE0189064")
        (field (name "LCSC_PART") "C25890")
        (field (name "MANUFACTURER") "Uniohm")
      )
      (libsource (lib "eagle-import") (part "3.3K-1%0402"))
    )
    (comp (ref "R132")
      (value "10K 1%")
      (footprint "eagle-import:0402")
      (fields
        (field (name "HQ_PART") "RE0207399")
        (field (name "LCSC_PART") "C25744")
        (field (name "MANUFACTURER") "ROHM")
      )
      (libsource (lib "eagle-import") (part "10K-1%0402"))
    )
    (comp (ref "R160")
      (value "27R 1%")
      (footprint "eagle-import:0201")
      (fields
        (field (name "HQ_PART") "RE0209327 ")
        (field (name "LCSC_PART") "C473051")
        (field (name "MANUFACTURER") "FH")
      )
      (libsource (lib "eagle-import") (part "27R-1%0201"))
    )
    (comp (ref "R163")
      (value "1K 1%")
      (footprint "eagle-import:0402")
      (fields
        (field (name "HQ_PART") "RE0208724")
        (field (name "LCSC_PART") "C11702")
        (field (name "MANUFACTURER") "FH")
      )
      (libsource (lib "eagle-import") (part "1K-1%0402"))
    )
    (comp (ref "R166")
      (value "3.3K 1%")
      (footprint "eagle-import:0402")
      (fields
        (field (name "HQ_PART") "RE0189064")
        (field (name "LCSC_PART") "C25890")
        (field (name "MANUFACTURER") "Uniohm")
      )
      (libsource (lib "eagle-import") (part "3.3K-1%0402"))
    )
    (comp (ref "R167")
      (value "3.3K 1%")
      (footprint "eagle-import:0402")
      (fields
        (field (name "HQ_PART") "RE0189064")
        (field (name "LCSC_PART") "C25890")
        (field (name "MANUFACTURER") "Uniohm")
      )
      (libsource (lib "eagle-import") (part "3.3K-1%0402"))
    )
    (comp (ref "R168")
      (value "3.3K 1%")
      (footprint "eagle-import:0402")
      (fields
        (field (name "HQ_PART") "RE0189064")
        (field (name "LCSC_PART") "C25890")
        (field (name "MANUFACTURER") "Uniohm")
      )
      (libsource (lib "eagle-import") (part "3.3K-1%0402"))
    )
    (comp (ref "RES")
      (value "B3U-1000P")
      (footprint "eagle-import:B3U-1000P")
      (fields
        (field (name "HQ_PART") "SW0036094 ")
        (field (name "LCSC_PART") "C231329")
        (field (name "MANUFACTURER") "Omron")
      )
      (libsource (lib "eagle-import") (part "B3U-1000P"))
    )
    (comp (ref "RST")
      (value "DNI")
      (footprint "eagle-import:TP-ROUND")
      (libsource (lib "eagle-import") (part "TP-ROUND"))
    )
    (comp (ref "RX0")
      (value "DNI")
      (footprint "eagle-import:TP-ROUND")
      (libsource (lib "eagle-import") (part "TP-ROUND"))
    )
    (comp (ref "SC")
      (value "DNI")
      (footprint "eagle-import:TP-ROUND")
      (libsource (lib "eagle-import") (part "TP-ROUND"))
    )
    (comp (ref "SCL0")
      (value "DNI")
      (footprint "eagle-import:TP-ROUND")
      (libsource (lib "eagle-import") (part "TP-ROUND"))
    )
    (comp (ref "SCL1")
      (value "DNI")
      (footprint "eagle-import:TP-ROUND")
      (libsource (lib "eagle-import") (part "TP-ROUND"))
    )
    (comp (ref "SCLK1")
      (value "DNI")
      (footprint "eagle-import:TP-ROUND")
      (libsource (lib "eagle-import") (part "TP-ROUND"))
    )
    (comp (ref "SDA0")
      (value "DNI")
      (footprint "eagle-import:TP-ROUND")
      (libsource (lib "eagle-import") (part "TP-ROUND"))
    )
    (comp (ref "SDA1")
      (value "DNI")
      (footprint "eagle-import:TP-ROUND")
      (libsource (lib "eagle-import") (part "TP-ROUND"))
    )
    (comp (ref "TX0")
      (value "DNI")
      (footprint "eagle-import:TP-ROUND")
      (libsource (lib "eagle-import") (part "TP-ROUND"))
    )
    (comp (ref "5V-NI1")
      (value "DNI")
      (footprint "eagle-import:TP-ROUND")
      (libsource (lib "eagle-import") (part "TP-ROUND"))
    )
    (comp (ref "5V-NI2")
      (value "DNI")
      (footprint "eagle-import:TP-ROUND")
      (libsource (lib "eagle-import") (part "TP-ROUND"))
    )
    (comp (ref "12VDC")
      (value "DNI")
      (footprint "eagle-import:TP-ROUND")
      (libsource (lib "eagle-import") (part "TP-ROUND"))
    )
    (comp (ref "AC/DC1")
      (value "IRM_10_12")
      (footprint "eagle-import:IRM_10_12")
      (fields
        (field (name "HQ_PART") "ZHLM0215926")
        (field (name "LCSC_PART") "C20618065")
        (field (name "MANUFACTURER") "MW")
      )
      (libsource (lib "eagle-import") (part "IRM_10_12"))
    )
    (comp (ref "AC/DC2")
      (value "IRM-10-15")
      (footprint "eagle-import:IRM_15_12")
      (fields (field (name "LCSC_PART") "C5439799"))
      (libsource (lib "eagle-import") (part "IRM_10_12-2"))
    )
    (comp (ref "AC_L")
      (value "FASTON-1217861-1")
      (footprint "eagle-import:1217861-1")
      (fields
        (field (name "LCSC_PART") "C428480")
        (field (name "MANUFACTURER") "TE CONNECTIVITY")
        (field (name "MPN") "1217861-1")
      )
      (libsource (lib "eagle-import") (part "FASTON-1217861-1"))
    )
    (comp (ref "AC_N")
      (value "FASTON-1217861-1")
      (footprint "eagle-import:1217861-1")
      (fields
        (field (name "LCSC_PART") "C428480")
        (field (name "MANUFACTURER") "TE CONNECTIVITY")
        (field (name "MPN") "1217861-1")
      )
      (libsource (lib "eagle-import") (part "FASTON-1217861-1"))
    )
    (comp (ref "ADC12")
      (value "DNI")
      (footprint "eagle-import:TP-ROUND")
      (libsource (lib "eagle-import") (part "TP-ROUND"))
    )
    (comp (ref "C5")
      (value "1nF 50V")
      (footprint "eagle-import:0603")
      (fields
        (field (name "HQ_PART") "CA0481650")
        (field (name "LCSC_PART") "C1588")
        (field (name "MANUFACTURER") "TDK")
      )
      (libsource (lib "eagle-import") (part "1NF-50V-0603"))
    )
    (comp (ref "C10")
      (value "100uF 25V")
      (footprint "eagle-import:6.3X7.7(DXL)")
      (fields
        (field (name "HQ_PART") "CA0362255")
        (field (name "LCSC_PART") "C267469")
        (field (name "MANUFACTURER") "HONOR")
      )
      (libsource (lib "eagle-import") (part "100UF-25V6.3X7.7(DXL)"))
    )
    (comp (ref "C13")
      (value "100uF 25V")
      (footprint "eagle-import:6.3X7.7(DXL)")
      (fields
        (field (name "HQ_PART") "CA0362255")
        (field (name "LCSC_PART") "C267469")
        (field (name "MANUFACTURER") "HONOR")
      )
      (libsource (lib "eagle-import") (part "100UF-25V6.3X7.7(DXL)"))
    )
    (comp (ref "C16")
      (value "100uF 25V")
      (footprint "eagle-import:6.3X7.7(DXL)")
      (fields
        (field (name "HQ_PART") "CA0362255")
        (field (name "LCSC_PART") "C267469")
        (field (name "MANUFACTURER") "HONOR")
      )
      (libsource (lib "eagle-import") (part "100UF-25V6.3X7.7(DXL)"))
    )
    (comp (ref "C21")
      (value "2.2uF 50V")
      (footprint "eagle-import:0603")
      (fields
        (field (name "HQ_PART") "CA0174463")
        (field (name "LCSC_PART") "C913904")
        (field (name "MANUFACTURER") "FH")
      )
      (libsource (lib "eagle-import") (part "2.2UF-50V0603"))
    )
    (comp (ref "C22")
      (value "220nF 50V")
      (footprint "eagle-import:0805")
      (fields
        (field (name "HQ_PART") "CA0174157")
        (field (name "LCSC_PART") "C5378")
        (field (name "MANUFACTURER") "FH")
      )
      (libsource (lib "eagle-import") (part "220NF-50V0805"))
    )
    (comp (ref "C23")
      (value "100uF 50V")
      (footprint "eagle-import:6.3X7.7(DXL)")
      (fields
        (field (name "HQ_PART") "ZHLM0353527")
        (field (name "LCSC_PART") "C3151829")
        (field (name "MANUFACTURER") "ROQANG")
      )
      (libsource (lib "eagle-import") (part "100UF-50V6.3X7.7(DXL)"))
    )
    (comp (ref "C35")
      (value "2.2uF 400V")
      (footprint "eagle-import:6.3X7.7(DXL)")
      (fields (field (name "LCSC_PART") "C3345109"))
      (libsource (lib "eagle-import") (part "2.2UF-400V6.3X7.7(DXL)"))
    )
    (comp (ref "C45")
      (value "1uF 50V")
      (footprint "eagle-import:0805")
      (fields
        (field (name "HQ_PART") "CA0182352")
        (field (name "LCSC_PART") "C28323")
        (field (name "MANUFACTURER") "TDK")
      )
      (libsource (lib "eagle-import") (part "1UF-50V0805"))
    )
    (comp (ref "C46")
      (value "2.2uF 50V")
      (footprint "eagle-import:0603")
      (fields
        (field (name "HQ_PART") "CA0174463")
        (field (name "LCSC_PART") "C913904")
        (field (name "MANUFACTURER") "FH")
      )
      (libsource (lib "eagle-import") (part "2.2UF-50V0603"))
    )
    (comp (ref "C47")
      (value "2.2uF 400V")
      (footprint "eagle-import:6.3X7.7(DXL)")
      (fields (field (name "LCSC_PART") "C3345109"))
      (libsource (lib "eagle-import") (part "2.2UF-400V6.3X7.7(DXL)"))
    )
    (comp (ref "C51")
      (value "1nF 50V")
      (footprint "eagle-import:0603")
      (fields
        (field (name "HQ_PART") "CA0481650")
        (field (name "LCSC_PART") "C1588")
        (field (name "MANUFACTURER") "TDK")
      )
      (libsource (lib "eagle-import") (part "1NF-50V-0603"))
    )
    (comp (ref "C52")
      (value "220nF 50V")
      (footprint "eagle-import:0805")
      (fields
        (field (name "HQ_PART") "CA0174157")
        (field (name "LCSC_PART") "C5378")
        (field (name "MANUFACTURER") "FH")
      )
      (libsource (lib "eagle-import") (part "220NF-50V0805"))
    )
    (comp (ref "C53")
      (value "100uF 50V")
      (footprint "eagle-import:6.3X7.7(DXL)")
      (fields
        (field (name "HQ_PART") "ZHLM0353527")
        (field (name "LCSC_PART") "C3151829")
        (field (name "MANUFACTURER") "ROQANG")
      )
      (libsource (lib "eagle-import") (part "100UF-50V6.3X7.7(DXL)"))
    )
    (comp (ref "C57")
      (value "1uF 50V")
      (footprint "eagle-import:0805")
      (fields
        (field (name "HQ_PART") "CA0182352")
        (field (name "LCSC_PART") "C28323")
        (field (name "MANUFACTURER") "TDK")
      )
      (libsource (lib "eagle-import") (part "1UF-50V0805"))
    )
    (comp (ref "D9")
      (value "1N4007")
      (footprint "eagle-import:SMA_DO-214AC")
      (fields
        (field (name "HQ_PART") "UN0002522")
        (field (name "LCSC_PART") "C727081")
        (field (name "MANUFACTURER") "SK")
      )
      (libsource (lib "eagle-import") (part "1N4007"))
    )
    (comp (ref "D10")
      (value "1N4007")
      (footprint "eagle-import:SMA_DO-214AC")
      (fields
        (field (name "HQ_PART") "UN0002522")
        (field (name "LCSC_PART") "C727081")
        (field (name "MANUFACTURER") "SK")
      )
      (libsource (lib "eagle-import") (part "1N4007"))
    )
    (comp (ref "D11")
      (value "US1J-E3/61T")
      (footprint "eagle-import:SMA_DO-214AC")
      (fields
        (field (name "HQ_PART") "DS0007395")
        (field (name "LCSC_PART") "C44763")
        (field (name "MANUFACTURER") "Vishay")
      )
      (libsource (lib "eagle-import") (part "US1J-E3/61T"))
    )
    (comp (ref "D12")
      (value "1N4007")
      (footprint "eagle-import:SMA_DO-214AC")
      (fields
        (field (name "HQ_PART") "UN0002522")
        (field (name "LCSC_PART") "C727081")
        (field (name "MANUFACTURER") "SK")
      )
      (libsource (lib "eagle-import") (part "1N4007"))
    )
    (comp (ref "D13")
      (value "1N4007")
      (footprint "eagle-import:SMA_DO-214AC")
      (fields
        (field (name "HQ_PART") "UN0002522")
        (field (name "LCSC_PART") "C727081")
        (field (name "MANUFACTURER") "SK")
      )
      (libsource (lib "eagle-import") (part "1N4007"))
    )
    (comp (ref "D14")
      (value "US1J-E3/61T")
      (footprint "eagle-import:SMA_DO-214AC")
      (fields
        (field (name "HQ_PART") "DS0007395")
        (field (name "LCSC_PART") "C44763")
        (field (name "MANUFACTURER") "Vishay")
      )
      (libsource (lib "eagle-import") (part "US1J-E3/61T"))
    )
    (comp (ref "D16")
      (value "SMAJ15A")
      (footprint "eagle-import:SMA_DO-214AC")
      (fields
        (field (name "HQ_PART") "PD0003270")
        (field (name "LCSC_PART") "C23424")
        (field (name "MANUFACTURER") "TWGMC")
      )
      (libsource (lib "eagle-import") (part "SMAJ15A"))
    )
    (comp (ref "FB1")
      (value "DNI")
      (footprint "eagle-import:TP-ROUND")
      (libsource (lib "eagle-import") (part "TP-ROUND"))
    )
    (comp (ref "FB2")
      (value "DNI")
      (footprint "eagle-import:TP-ROUND")
      (libsource (lib "eagle-import") (part "TP-ROUND"))
    )
    (comp (ref "IC5")
      (value "MP150GJ")
      (footprint "eagle-import:SOT23-5")
      (fields
        (field (name "HQ_PART") "IC0001313")
        (field (name "MANUFACTURER") "MONOLITHIC POWER SYSTEMS ")
        (field (name "MPN") "MP150GJ-Z")
      )
      (libsource (lib "eagle-import") (part "MP150GJ"))
    )
    (comp (ref "IC13")
      (value "MP150GJ")
      (footprint "eagle-import:SOT23-5")
      (fields
        (field (name "HQ_PART") "IC0001313")
        (field (name "MANUFACTURER") "MONOLITHIC POWER SYSTEMS ")
        (field (name "MPN") "MP150GJ-Z")
      )
      (libsource (lib "eagle-import") (part "MP150GJ"))
    )
    (comp (ref "J2") (value "DNI") (footprint "eagle-import:SJ") (libsource (lib "eagle-import") (part "SJ")))
    (comp (ref "J7") (value "DNI") (footprint "eagle-import:SJ") (libsource (lib "eagle-import") (part "SJ")))
    (comp (ref "J8")
      (value "0R 1%")
      (footprint "eagle-import:0805")
      (fields
        (field (name "HQ_PART") "RE0013023")
        (field (name "LCSC_PART") "C17477")
        (field (name "MANUFACTURER") "Vishay")
      )
      (libsource (lib "eagle-import") (part "0R0805"))
    )
    (comp (ref "J9")
      (value "0R 1%")
      (footprint "eagle-import:0805")
      (fields
        (field (name "HQ_PART") "RE0013023")
        (field (name "LCSC_PART") "C17477")
        (field (name "MANUFACTURER") "Vishay")
      )
      (libsource (lib "eagle-import") (part "0R0805"))
    )
    (comp (ref "J10")
      (value "0R 1%")
      (footprint "eagle-import:0805")
      (fields
        (field (name "HQ_PART") "RE0013023")
        (field (name "LCSC_PART") "C17477")
        (field (name "MANUFACTURER") "Vishay")
      )
      (libsource (lib "eagle-import") (part "0R0805"))
    )
    (comp (ref "L-REC1")
      (value "DNI")
      (footprint "eagle-import:TP-ROUND")
      (libsource (lib "eagle-import") (part "TP-ROUND"))
    )
    (comp (ref "L-REC2")
      (value "DNI")
      (footprint "eagle-import:TP-ROUND")
      (libsource (lib "eagle-import") (part "TP-ROUND"))
    )
    (comp (ref "L3")
      (value "1mH")
      (footprint "eagle-import:L-6.6X6.6")
      (fields
        (field (name "HQ_PART") "IN0035691")
        (field (name "LCSC_PART") "C168049")
        (field (name "MANUFACTURER") "SXN")
      )
      (libsource (lib "eagle-import") (part "1MHL-6.6X6.6"))
    )
    (comp (ref "L5")
      (value "1mH")
      (footprint "eagle-import:L-6.6X6.6")
      (fields
        (field (name "HQ_PART") "IN0035691")
        (field (name "LCSC_PART") "C168049")
        (field (name "MANUFACTURER") "SXN")
      )
      (libsource (lib "eagle-import") (part "1MHL-6.6X6.6"))
    )
    (comp (ref "P12ON")
      (value "Green")
      (footprint "eagle-import:LED-0603")
      (fields
        (field (name "HQ_PART") "PH0010430")
        (field (name "LCSC_PART") "C965804")
        (field (name "MANUFACTURER") "Wurth")
      )
      (libsource (lib "eagle-import") (part "LED-GREENLED-0603"))
    )
    (comp (ref "R60")
      (value "4.99K 1%")
      (footprint "eagle-import:0603")
      (fields
        (field (name "HQ_PART") "RE0204816")
        (field (name "LCSC_PART") "C23046")
        (field (name "MANUFACTURER") "Yageo")
      )
      (libsource (lib "eagle-import") (part "4.99K-1%0603"))
    )
    (comp (ref "R61")
      (value "4.99K 1%")
      (footprint "eagle-import:0603")
      (fields
        (field (name "HQ_PART") "RE0204816")
        (field (name "LCSC_PART") "C23046")
        (field (name "MANUFACTURER") "Yageo")
      )
      (libsource (lib "eagle-import") (part "4.99K-1%0603"))
    )
    (comp (ref "R62")
      (value "39R 1% 2W")
      (footprint "eagle-import:2512")
      (fields
        (field (name "HQ_PART") "RE0461666")
        (field (name "LCSC_PART") "C175263")
        (field (name "MANUFACTURER") "Yageo")
      )
      (libsource (lib "eagle-import") (part "39R-1%2512"))
    )
    (comp (ref "R94")
      (value "100K 1%")
      (footprint "eagle-import:0402")
      (fields
        (field (name "HQ_PART") "RE0203322")
        (field (name "LCSC_PART") "C25741")
        (field (name "MANUFACTURER") "FH")
      )
      (libsource (lib "eagle-import") (part "100K-1%0402"))
    )
    (comp (ref "R95")
      (value "10K 1%")
      (footprint "eagle-import:0402")
      (fields
        (field (name "HQ_PART") "RE0207399")
        (field (name "LCSC_PART") "C25744")
        (field (name "MANUFACTURER") "ROHM")
      )
      (libsource (lib "eagle-import") (part "10K-1%0402"))
    )
    (comp (ref "R96")
      (value "10K 1%")
      (footprint "eagle-import:0805")
      (fields
        (field (name "HQ_PART") "RE0207376")
        (field (name "LCSC_PART") "C17414")
        (field (name "MANUFACTURER") "RALEC")
      )
      (libsource (lib "eagle-import") (part "10K-1%0805"))
    )
    (comp (ref "R105")
      (value "4.99K 1%")
      (footprint "eagle-import:0603")
      (fields
        (field (name "HQ_PART") "RE0204816")
        (field (name "LCSC_PART") "C23046")
        (field (name "MANUFACTURER") "Yageo")
      )
      (libsource (lib "eagle-import") (part "4.99K-1%0603"))
    )
    (comp (ref "R106")
      (value "39R 1% 2W")
      (footprint "eagle-import:2512")
      (fields
        (field (name "HQ_PART") "RE0461666")
        (field (name "LCSC_PART") "C175263")
        (field (name "MANUFACTURER") "Yageo")
      )
      (libsource (lib "eagle-import") (part "39R-1%2512"))
    )
    (comp (ref "R107")
      (value "4.99K 1%")
      (footprint "eagle-import:0603")
      (fields
        (field (name "HQ_PART") "RE0204816")
        (field (name "LCSC_PART") "C23046")
        (field (name "MANUFACTURER") "Yageo")
      )
      (libsource (lib "eagle-import") (part "4.99K-1%0603"))
    )
    (comp (ref "R108")
      (value "10K 1%")
      (footprint "eagle-import:0805")
      (fields
        (field (name "HQ_PART") "RE0207376")
        (field (name "LCSC_PART") "C17414")
        (field (name "MANUFACTURER") "RALEC")
      )
      (libsource (lib "eagle-import") (part "10K-1%0805"))
    )
    (comp (ref "R150")
      (value "8.2K 1%")
      (footprint "eagle-import:0402")
      (fields
        (field (name "HQ_PART") "RE0209227")
        (field (name "LCSC_PART") "C25924")
        (field (name "MANUFACTURER") "FH")
      )
      (libsource (lib "eagle-import") (part "8.2K-1%0402"))
    )
    (comp (ref "VCC")
      (value "DNI")
      (footprint "eagle-import:TP-ROUND")
      (libsource (lib "eagle-import") (part "TP-ROUND"))
    )
    (comp (ref "VCC2")
      (value "DNI")
      (footprint "eagle-import:TP-ROUND")
      (libsource (lib "eagle-import") (part "TP-ROUND"))
    )
    (comp (ref "3VDC")
      (value "DNI")
      (footprint "eagle-import:TP-ROUND")
      (libsource (lib "eagle-import") (part "TP-ROUND"))
    )
    (comp (ref "3VFB")
      (value "DNI")
      (footprint "eagle-import:TP-ROUND")
      (libsource (lib "eagle-import") (part "TP-ROUND"))
    )
    (comp (ref "5VDC")
      (value "DNI")
      (footprint "eagle-import:TP-ROUND")
      (libsource (lib "eagle-import") (part "TP-ROUND"))
    )
    (comp (ref "5VFB")
      (value "DNI")
      (footprint "eagle-import:TP-ROUND")
      (libsource (lib "eagle-import") (part "TP-ROUND"))
    )
    (comp (ref "C1")
      (value "22uF 25V")
      (footprint "eagle-import:1206")
      (fields
        (field (name "HQ_PART") "CA0182777")
        (field (name "LCSC_PART") "C12891")
        (field (name "MANUFACTURER") "FH")
      )
      (libsource (lib "eagle-import") (part "22UF-25V-1206"))
    )
    (comp (ref "C2")
      (value "22uF 25V")
      (footprint "eagle-import:1206")
      (fields
        (field (name "HQ_PART") "CA0182777")
        (field (name "LCSC_PART") "C12891")
        (field (name "MANUFACTURER") "FH")
      )
      (libsource (lib "eagle-import") (part "22UF-25V-1206"))
    )
    (comp (ref "C3")
      (value "100nF 25V")
      (footprint "eagle-import:0402")
      (fields
        (field (name "HQ_PART") "CA0176807")
        (field (name "LCSC_PART") "C56392")
        (field (name "MANUFACTURER") "Walsin")
      )
      (libsource (lib "eagle-import") (part "100NF-25V-0402"))
    )
    (comp (ref "C4")
      (value "100nF 25V")
      (footprint "eagle-import:0402")
      (fields
        (field (name "HQ_PART") "CA0176807")
        (field (name "LCSC_PART") "C56392")
        (field (name "MANUFACTURER") "Walsin")
      )
      (libsource (lib "eagle-import") (part "100NF-25V-0402"))
    )
    (comp (ref "C6")
      (value "100nF 25V")
      (footprint "eagle-import:0402")
      (fields
        (field (name "HQ_PART") "CA0176807")
        (field (name "LCSC_PART") "C56392")
        (field (name "MANUFACTURER") "Walsin")
      )
      (libsource (lib "eagle-import") (part "100NF-25V-0402"))
    )
    (comp (ref "C7")
      (value "100nF 25V")
      (footprint "eagle-import:0402")
      (fields
        (field (name "HQ_PART") "CA0176807")
        (field (name "LCSC_PART") "C56392")
        (field (name "MANUFACTURER") "Walsin")
      )
      (libsource (lib "eagle-import") (part "100NF-25V-0402"))
    )
    (comp (ref "C8")
      (value "100nF 25V")
      (footprint "eagle-import:0402")
      (fields
        (field (name "HQ_PART") "CA0176807")
        (field (name "LCSC_PART") "C56392")
        (field (name "MANUFACTURER") "Walsin")
      )
      (libsource (lib "eagle-import") (part "100NF-25V-0402"))
    )
    (comp (ref "C9")
      (value "100nF 25V")
      (footprint "eagle-import:0402")
      (fields
        (field (name "HQ_PART") "CA0176807")
        (field (name "LCSC_PART") "C56392")
        (field (name "MANUFACTURER") "Walsin")
      )
      (libsource (lib "eagle-import") (part "100NF-25V-0402"))
    )
    (comp (ref "C11")
      (value "33pF 50V")
      (footprint "eagle-import:0402")
      (fields
        (field (name "HQ_PART") "CA0484207")
        (field (name "LCSC_PART") "C107005")
        (field (name "MANUFACTURER") "PSA")
      )
      (libsource (lib "eagle-import") (part "33PF-50V0402"))
    )
    (comp (ref "C12")
      (value "33pF 50V")
      (footprint "eagle-import:0402")
      (fields
        (field (name "HQ_PART") "CA0484207")
        (field (name "LCSC_PART") "C107005")
        (field (name "MANUFACTURER") "PSA")
      )
      (libsource (lib "eagle-import") (part "33PF-50V0402"))
    )
    (comp (ref "C14")
      (value "22uF 25V")
      (footprint "eagle-import:1206")
      (fields
        (field (name "HQ_PART") "CA0182777")
        (field (name "LCSC_PART") "C12891")
        (field (name "MANUFACTURER") "FH")
      )
      (libsource (lib "eagle-import") (part "22UF-25V-1206"))
    )
    (comp (ref "C15")
      (value "22uF 25V")
      (footprint "eagle-import:1206")
      (fields
        (field (name "HQ_PART") "CA0182777")
        (field (name "LCSC_PART") "C12891")
        (field (name "MANUFACTURER") "FH")
      )
      (libsource (lib "eagle-import") (part "22UF-25V-1206"))
    )
    (comp (ref "C17")
      (value "22uF 25V")
      (footprint "eagle-import:1206")
      (fields
        (field (name "HQ_PART") "CA0182777")
        (field (name "LCSC_PART") "C12891")
        (field (name "MANUFACTURER") "FH")
      )
      (libsource (lib "eagle-import") (part "22UF-25V-1206"))
    )
    (comp (ref "C18")
      (value "22uF 25V")
      (footprint "eagle-import:1206")
      (fields
        (field (name "HQ_PART") "CA0182777")
        (field (name "LCSC_PART") "C12891")
        (field (name "MANUFACTURER") "FH")
      )
      (libsource (lib "eagle-import") (part "22UF-25V-1206"))
    )
    (comp (ref "C97")
      (value "10uF 50V")
      (footprint "eagle-import:0805")
      (fields (field (name "LCSC_PART") "C440198"))
      (libsource (lib "eagle-import") (part "10UF-50V-0805"))
    )
    (comp (ref "C98")
      (value "100nF 25V")
      (footprint "eagle-import:0201")
      (fields
        (field (name "HQ_PART") "CA0183221")
        (field (name "LCSC_PART") "C76939")
        (field (name "MANUFACTURER") "Samsung")
      )
      (libsource (lib "eagle-import") (part "100NF-25V-0201"))
    )
    (comp (ref "C99")
      (value "10uF 50V")
      (footprint "eagle-import:0805")
      (fields (field (name "LCSC_PART") "C440198"))
      (libsource (lib "eagle-import") (part "10UF-50V-0805"))
    )
    (comp (ref "C100")
      (value "100nF 25V")
      (footprint "eagle-import:0201")
      (fields
        (field (name "HQ_PART") "CA0183221")
        (field (name "LCSC_PART") "C76939")
        (field (name "MANUFACTURER") "Samsung")
      )
      (libsource (lib "eagle-import") (part "100NF-25V-0201"))
    )
    (comp (ref "D15")
      (value "DNI")
      (footprint "eagle-import:SMA_DO-214AC")
      (fields
        (field (name "HQ_PART") "DS0145075")
        (field (name "LCSC_PART") "C727049")
        (field (name "MANUFACTURER") "MDD")
      )
      (libsource (lib "eagle-import") (part "SS12"))
    )
    (comp (ref "GND")
      (value "DNI")
      (footprint "eagle-import:TP-ROUND")
      (libsource (lib "eagle-import") (part "TP-ROUND"))
    )
    (comp (ref "GND-3")
      (value "DNI")
      (footprint "eagle-import:TP-ROUND")
      (libsource (lib "eagle-import") (part "TP-ROUND"))
    )
    (comp (ref "GND-5")
      (value "DNI")
      (footprint "eagle-import:TP-ROUND")
      (libsource (lib "eagle-import") (part "TP-ROUND"))
    )
    (comp (ref "IC1")
      (value "DNI")
      (footprint "eagle-import:SOT65P280X110-8N")
      (fields
        (field (name "HQ_PART") "IC0339027")
        (field (name "LCSC_PART") "C45889")
        (field (name "MANUFACTURER") "MPS")
      )
      (libsource (lib "eagle-import") (part "MP2315TSOT23-8"))
    )
    (comp (ref "IC2")
      (value "MP2315GJ-Z")
      (footprint "eagle-import:SOT65P280X110-8N")
      (fields
        (field (name "HQ_PART") "IC0339027")
        (field (name "LCSC_PART") "C45889")
        (field (name "MANUFACTURER") "MPS")
      )
      (libsource (lib "eagle-import") (part "MP2315TSOT23-8"))
    )
    (comp (ref "IC21")
      (value "MIC5504-3.3YM5")
      (footprint "eagle-import:SOT23-5")
      (fields
        (field (name "HQ_PART") "IC0230296")
        (field (name "LCSC_PART") "C41348078")
        (field (name "MANUFACTURER") "Microchip")
      )
      (libsource (lib "eagle-import") (part "MIC5504-3.3YM5-TR"))
    )
    (comp (ref "L1")
      (value "DNI")
      (footprint "eagle-import:SRR5228A")
      (fields
        (field (name "HQ_PART") "IN0027228")
        (field (name "LCSC_PART") "C325964")
        (field (name "MANUFACTURER") "YJYCOIN")
      )
      (libsource (lib "eagle-import") (part "4.7UH"))
    )
    (comp (ref "L2")
      (value "4.7uH 3.5A")
      (footprint "eagle-import:SRR5228A")
      (fields
        (field (name "LCSC_PART") "C14258")
        (field (name "MANUFACTURER") "SXN")
        (field (name "MPN") "YP0503-4R7M")
      )
      (libsource (lib "eagle-import") (part "4.2UH"))
    )
    (comp (ref "P3ON")
      (value "Green")
      (footprint "eagle-import:LED-0603")
      (fields
        (field (name "HQ_PART") "PH0010430")
        (field (name "LCSC_PART") "C965804")
        (field (name "MANUFACTURER") "Wurth")
      )
      (libsource (lib "eagle-import") (part "LED-GREENLED-0603"))
    )
    (comp (ref "P5ON")
      (value "DNI")
      (footprint "eagle-import:LED-0603")
      (fields
        (field (name "HQ_PART") "PH0010430")
        (field (name "LCSC_PART") "C965804")
        (field (name "MANUFACTURER") "Wurth")
      )
      (libsource (lib "eagle-import") (part "LED-GREENLED-0603"))
    )
    (comp (ref "PWR")
      (value "Green")
      (footprint "eagle-import:LED-0603")
      (fields
        (field (name "HQ_PART") "PH0010430")
        (field (name "LCSC_PART") "C965804")
        (field (name "MANUFACTURER") "Wurth")
      )
      (libsource (lib "eagle-import") (part "LED-GREENLED-0603"))
    )
    (comp (ref "R1")
      (value "DNI")
      (footprint "eagle-import:0402")
      (libsource (lib "eagle-import") (part "R0402"))
    )
    (comp (ref "R2")
      (value "10K 1%")
      (footprint "eagle-import:0402")
      (fields
        (field (name "HQ_PART") "RE0207399")
        (field (name "LCSC_PART") "C25744")
        (field (name "MANUFACTURER") "ROHM")
      )
      (libsource (lib "eagle-import") (part "10K-1%0402"))
    )
    (comp (ref "R3")
      (value "100K 1%")
      (footprint "eagle-import:0402")
      (fields
        (field (name "HQ_PART") "RE0203322")
        (field (name "LCSC_PART") "C25741")
        (field (name "MANUFACTURER") "FH")
      )
      (libsource (lib "eagle-import") (part "100K-1%0402"))
    )
    (comp (ref "R4")
      (value "9.09K 1%")
      (footprint "eagle-import:0402")
      (fields
        (field (name "HQ_PART") "RE0203888")
        (field (name "LCSC_PART") "C11549")
        (field (name "MANUFACTURER") "Yageo")
      )
      (libsource (lib "eagle-import") (part "9.09K-1%0402"))
    )
    (comp (ref "R5")
      (value "100K 1%")
      (footprint "eagle-import:0402")
      (fields
        (field (name "HQ_PART") "RE0203322")
        (field (name "LCSC_PART") "C25741")
        (field (name "MANUFACTURER") "FH")
      )
      (libsource (lib "eagle-import") (part "100K-1%0402"))
    )
    (comp (ref "R6")
      (value "7.5K 1%")
      (footprint "eagle-import:0402")
      (fields
        (field (name "HQ_PART") "RE0188271")
        (field (name "LCSC_PART") "C25918")
        (field (name "MANUFACTURER") "Uniohm")
      )
      (libsource (lib "eagle-import") (part "7.5K-1%0402"))
    )
    (comp (ref "R7")
      (value "10R 1%")
      (footprint "eagle-import:0402")
      (fields
        (field (name "HQ_PART") "RE0191560")
        (field (name "LCSC_PART") "C25077")
        (field (name "MANUFACTURER") "Uniohm")
      )
      (libsource (lib "eagle-import") (part "10R-1%0402"))
    )
    (comp (ref "R8")
      (value "20K 1%")
      (footprint "eagle-import:0402")
      (fields
        (field (name "HQ_PART") "RE0203337")
        (field (name "LCSC_PART") "C25765")
        (field (name "MANUFACTURER") "FH")
      )
      (libsource (lib "eagle-import") (part "20K-1%0402"))
    )
    (comp (ref "R9")
      (value "10R 1%")
      (footprint "eagle-import:0402")
      (fields
        (field (name "HQ_PART") "RE0191560")
        (field (name "LCSC_PART") "C25077")
        (field (name "MANUFACTURER") "Uniohm")
      )
      (libsource (lib "eagle-import") (part "10R-1%0402"))
    )
    (comp (ref "R10")
      (value "33K 1%")
      (footprint "eagle-import:0402")
      (fields
        (field (name "HQ_PART") "RE0321838")
        (field (name "LCSC_PART") "C25779")
        (field (name "MANUFACTURER") "RALEC")
      )
      (libsource (lib "eagle-import") (part "33K-1%0402"))
    )
    (comp (ref "R11")
      (value "40.2K 1%")
      (footprint "eagle-import:0402")
      (fields
        (field (name "HQ_PART") "RE0063264")
        (field (name "LCSC_PART") "C25893")
        (field (name "MANUFACTURER") "Yageo")
      )
      (libsource (lib "eagle-import") (part "40.2K-1%0402"))
    )
    (comp (ref "R12")
      (value "7.5K 1%")
      (footprint "eagle-import:0402")
      (fields
        (field (name "HQ_PART") "RE0188271")
        (field (name "LCSC_PART") "C25918")
        (field (name "MANUFACTURER") "Uniohm")
      )
      (libsource (lib "eagle-import") (part "7.5K-1%0402"))
    )
    (comp (ref "R13")
      (value "40.2K 1%")
      (footprint "eagle-import:0402")
      (fields
        (field (name "HQ_PART") "RE0063264")
        (field (name "LCSC_PART") "C25893")
        (field (name "MANUFACTURER") "Yageo")
      )
      (libsource (lib "eagle-import") (part "40.2K-1%0402"))
    )
    (comp (ref "R14")
      (value "12.7K 1%")
      (footprint "eagle-import:0402")
      (fields
        (field (name "HQ_PART") "RE0202294")
        (field (name "LCSC_PART") "C25853")
        (field (name "MANUFACTURER") "Yageo")
      )
      (libsource (lib "eagle-import") (part "12.7K-1%0402"))
    )
    (comp (ref "R123")
      (value "1K 1%")
      (footprint "eagle-import:0402")
      (fields
        (field (name "HQ_PART") "RE0208724")
        (field (name "LCSC_PART") "C11702")
        (field (name "MANUFACTURER") "FH")
      )
      (libsource (lib "eagle-import") (part "1K-1%0402"))
    )
    (comp (ref "R148")
      (value "2.4K 1%")
      (footprint "eagle-import:0402")
      (fields
        (field (name "HQ_PART") "RE0202491")
        (field (name "LCSC_PART") "C25882")
        (field (name "MANUFACTURER") "LIZ")
      )
      (libsource (lib "eagle-import") (part "2.4K-1%0402"))
    )
    (comp (ref "R151")
      (value "1K 1%")
      (footprint "eagle-import:0402")
      (fields
        (field (name "HQ_PART") "RE0208724")
        (field (name "LCSC_PART") "C11702")
        (field (name "MANUFACTURER") "FH")
      )
      (libsource (lib "eagle-import") (part "1K-1%0402"))
    )
    (comp (ref "R161")
      (value "DNI")
      (footprint "eagle-import:0402")
      (libsource (lib "eagle-import") (part "R0402"))
    )
    (comp (ref "R162")
      (value "10K 1%")
      (footprint "eagle-import:0402")
      (fields
        (field (name "HQ_PART") "RE0207399")
        (field (name "LCSC_PART") "C25744")
        (field (name "MANUFACTURER") "ROHM")
      )
      (libsource (lib "eagle-import") (part "10K-1%0402"))
    )
    (comp (ref "R169")
      (value "0R 1%")
      (footprint "eagle-import:1206")
      (fields
        (field (name "PACKAGE") "1206")
        (field (name "HQ_PART") "RE0209081")
        (field (name "LCSC_PART") "C205296")
        (field (name "MANUFACTURER") "RALEC")
      )
      (libsource (lib "eagle-import") (part "0R1206"))
    )
    (comp (ref "R171")
      (value "10K 1%")
      (footprint "eagle-import:0402")
      (fields
        (field (name "HQ_PART") "RE0207399")
        (field (name "LCSC_PART") "C25744")
        (field (name "MANUFACTURER") "ROHM")
      )
      (libsource (lib "eagle-import") (part "10K-1%0402"))
    )
    (comp (ref "R172")
      (value "DNI")
      (footprint "eagle-import:0402")
      (libsource (lib "eagle-import") (part "R0402"))
    )
    (comp (ref "SW")
      (value "DNI")
      (footprint "eagle-import:TP-ROUND")
      (libsource (lib "eagle-import") (part "TP-ROUND"))
    )
    (comp (ref "SW3")
      (value "DNI")
      (footprint "eagle-import:TP-ROUND")
      (libsource (lib "eagle-import") (part "TP-ROUND"))
    )
    (comp (ref "D1")
      (value "MBRA340T3G")
      (footprint "eagle-import:SMA_DO-214AC")
      (fields
        (field (name "HQ_PART") "DS0002158")
        (field (name "LCSC_PART") "C26178")
        (field (name "MANUFACTURER") "ON")
      )
      (libsource (lib "eagle-import") (part "MBRA340T3G"))
    )
    (comp (ref "D2")
      (value "MBRA340T3G")
      (footprint "eagle-import:SMA_DO-214AC")
      (fields
        (field (name "HQ_PART") "DS0002158")
        (field (name "LCSC_PART") "C26178")
        (field (name "MANUFACTURER") "ON")
      )
      (libsource (lib "eagle-import") (part "MBRA340T3G"))
    )
    (comp (ref "D3")
      (value "MBRA340T3G")
      (footprint "eagle-import:SMA_DO-214AC")
      (fields
        (field (name "HQ_PART") "DS0002158")
        (field (name "LCSC_PART") "C26178")
        (field (name "MANUFACTURER") "ON")
      )
      (libsource (lib "eagle-import") (part "MBRA340T3G"))
    )
    (comp (ref "D4")
      (value "MBRA340T3G")
      (footprint "eagle-import:SMA_DO-214AC")
      (fields
        (field (name "HQ_PART") "DS0002158")
        (field (name "LCSC_PART") "C26178")
        (field (name "MANUFACTURER") "ON")
      )
      (libsource (lib "eagle-import") (part "MBRA340T3G"))
    )
    (comp (ref "D5")
      (value "MBRA340T3G")
      (footprint "eagle-import:SMA_DO-214AC")
      (fields
        (field (name "HQ_PART") "DS0002158")
        (field (name "LCSC_PART") "C26178")
        (field (name "MANUFACTURER") "ON")
      )
      (libsource (lib "eagle-import") (part "MBRA340T3G"))
    )
    (comp (ref "D6")
      (value "MBRA340T3G")
      (footprint "eagle-import:SMA_DO-214AC")
      (fields
        (field (name "HQ_PART") "DS0002158")
        (field (name "LCSC_PART") "C26178")
        (field (name "MANUFACTURER") "ON")
      )
      (libsource (lib "eagle-import") (part "MBRA340T3G"))
    )
    (comp (ref "D7")
      (value "MBRA340T3G")
      (footprint "eagle-import:SMA_DO-214AC")
      (fields
        (field (name "HQ_PART") "DS0002158")
        (field (name "LCSC_PART") "C26178")
        (field (name "MANUFACTURER") "ON")
      )
      (libsource (lib "eagle-import") (part "MBRA340T3G"))
    )
    (comp (ref "D8")
      (value "MBRA340T3G")
      (footprint "eagle-import:SMA_DO-214AC")
      (fields
        (field (name "HQ_PART") "DS0002158")
        (field (name "LCSC_PART") "C26178")
        (field (name "MANUFACTURER") "ON")
      )
      (libsource (lib "eagle-import") (part "MBRA340T3G"))
    )
    (comp (ref "K1")
      (value "G2RL-1A-E DC12")
      (footprint "eagle-import:RELAY_G2RL-1A-E_DC5_OMR")
      (fields (field (name "LCSC_PART") "C1564126") (field (name "MANUFACTURER") "Omron"))
      (libsource (lib "eagle-import") (part "G2RL-1A-E_DC12"))
    )
    (comp (ref "K2")
      (value "G2RL-1A-E DC12")
      (footprint "eagle-import:RELAY_G2RL-1A-E_DC5_OMR")
      (fields (field (name "LCSC_PART") "C1564126") (field (name "MANUFACTURER") "Omron"))
      (libsource (lib "eagle-import") (part "G2RL-1A-E_DC12"))
    )
    (comp (ref "K3")
      (value "G2RL-1A-E DC12")
      (footprint "eagle-import:RELAY_G2RL-1A-E_DC5_OMR")
      (fields (field (name "LCSC_PART") "C1564126") (field (name "MANUFACTURER") "Omron"))
      (libsource (lib "eagle-import") (part "G2RL-1A-E_DC12"))
    )
    (comp (ref "K4")
      (value "G2RL-1A-E DC12")
      (footprint "eagle-import:RELAY_G2RL-1A-E_DC5_OMR")
      (fields (field (name "LCSC_PART") "C1564126") (field (name "MANUFACTURER") "Omron"))
      (libsource (lib "eagle-import") (part "G2RL-1A-E_DC12"))
    )
    (comp (ref "K5")
      (value "G2RL-1A-E DC12")
      (footprint "eagle-import:RELAY_G2RL-1A-E_DC5_OMR")
      (fields (field (name "LCSC_PART") "C1564126") (field (name "MANUFACTURER") "Omron"))
      (libsource (lib "eagle-import") (part "G2RL-1A-E_DC12"))
    )
    (comp (ref "K6")
      (value "G2RL-1A-E DC12")
      (footprint "eagle-import:RELAY_G2RL-1A-E_DC5_OMR")
      (fields (field (name "LCSC_PART") "C1564126") (field (name "MANUFACTURER") "Omron"))
      (libsource (lib "eagle-import") (part "G2RL-1A-E_DC12"))
    )
    (comp (ref "K7")
      (value "G2RL-1A-E DC12")
      (footprint "eagle-import:RELAY_G2RL-1A-E_DC5_OMR")
      (fields (field (name "LCSC_PART") "C1564126") (field (name "MANUFACTURER") "Omron"))
      (libsource (lib "eagle-import") (part "G2RL-1A-E_DC12"))
    )
    (comp (ref "K8")
      (value "G2RL-1A-E DC12")
      (footprint "eagle-import:RELAY_G2RL-1A-E_DC5_OMR")
      (fields (field (name "LCSC_PART") "C1564126") (field (name "MANUFACTURER") "Omron"))
      (libsource (lib "eagle-import") (part "G2RL-1A-E_DC12"))
    )
    (comp (ref "ADCUSB")
      (value "DNI")
      (footprint "eagle-import:TP-ROUND")
      (libsource (lib "eagle-import") (part "TP-ROUND"))
    )
    (comp (ref "C65")
      (value "10uF 50V")
      (footprint "eagle-import:0805")
      (fields (field (name "LCSC_PART") "C440198"))
      (libsource (lib "eagle-import") (part "10UF-50V-0805"))
    )
    (comp (ref "C66")
      (value "100nF 25V")
      (footprint "eagle-import:0402")
      (fields
        (field (name "HQ_PART") "CA0176807")
        (field (name "LCSC_PART") "C56392")
        (field (name "MANUFACTURER") "Walsin")
      )
      (libsource (lib "eagle-import") (part "100NF-25V-0402"))
    )
    (comp (ref "C78")
      (value "4.7nF 50V")
      (footprint "eagle-import:0402")
      (fields
        (field (name "HQ_PART") "CA0176643")
        (field (name "LCSC_PART") "C1538")
        (field (name "MANUFACTURER") "Walsin")
      )
      (libsource (lib "eagle-import") (part "4.7NF-50V0402"))
    )
    (comp (ref "DSP")
      (value "AFC11-S20ICC-00")
      (footprint "eagle-import:FPC20")
      (fields
        (field (name "HQ_PART") "CO0889517")
        (field (name "LCSC_PART") "C466537")
        (field (name "MANUFACTURER") "JS")
      )
      (libsource (lib "eagle-import") (part "AFC11-S20ICC-00"))
    )
    (comp (ref "ESD1")
      (value "SP0503BAHTG")
      (footprint "eagle-import:SOT143")
      (fields
        (field (name "HQ_PART") "CP0003989")
        (field (name "LCSC_PART") "C3040626")
        (field (name "MANUFACTURER") "Littelfuse")
      )
      (libsource (lib "eagle-import") (part "SP0503BAHT"))
    )
    (comp (ref "FAN")
      (value "DNI")
      (footprint "eagle-import:02P")
      (libsource (lib "eagle-import") (part "M02"))
    )
    (comp (ref "FCTL")
      (value "DNI")
      (footprint "eagle-import:TP-ROUND")
      (libsource (lib "eagle-import") (part "TP-ROUND"))
    )
    (comp (ref "GDRC")
      (value "DNI")
      (footprint "eagle-import:1X4")
      (libsource (lib "eagle-import") (part "CON-1X4"))
    )
    (comp (ref "R121")
      (value "2.2K 1%")
      (footprint "eagle-import:0201")
      (fields
        (field (name "HQ_PART") "RE0209901")
        (field (name "LCSC_PART") "C473508")
        (field (name "MANUFACTURER") "FH")
      )
      (libsource (lib "eagle-import") (part "2.2K-1%0201"))
    )
    (comp (ref "R124")
      (value "5.1K 1%")
      (footprint "eagle-import:0201")
      (fields
        (field (name "HQ_PART") "RE0185972")
        (field (name "LCSC_PART") "C274341")
        (field (name "MANUFACTURER") "Yageo")
      )
      (libsource (lib "eagle-import") (part "5.1K-1%0201"))
    )
    (comp (ref "R125")
      (value "5.1K 1%")
      (footprint "eagle-import:0201")
      (fields
        (field (name "HQ_PART") "RE0185972")
        (field (name "LCSC_PART") "C274341")
        (field (name "MANUFACTURER") "Yageo")
      )
      (libsource (lib "eagle-import") (part "5.1K-1%0201"))
    )
    (comp (ref "R126")
      (value "10K 1%")
      (footprint "eagle-import:0201")
      (fields
        (field (name "HQ_PART") "RE0208620")
        (field (name "LCSC_PART") "C473048")
        (field (name "MANUFACTURER") "FH")
      )
      (libsource (lib "eagle-import") (part "10K-1%0201"))
    )
    (comp (ref "R127")
      (value "10K 1%")
      (footprint "eagle-import:0201")
      (fields
        (field (name "HQ_PART") "RE0208620")
        (field (name "LCSC_PART") "C473048")
        (field (name "MANUFACTURER") "FH")
      )
      (libsource (lib "eagle-import") (part "10K-1%0201"))
    )
    (comp (ref "R131")
      (value "1M 1%")
      (footprint "eagle-import:0402")
      (fields
        (field (name "HQ_PART") "RE0055809")
        (field (name "LCSC_PART") "C26083")
        (field (name "MANUFACTURER") "Vishay")
      )
      (libsource (lib "eagle-import") (part "1M-1%0402"))
    )
    (comp (ref "R147")
      (value "10K 1%")
      (footprint "eagle-import:0402")
      (fields
        (field (name "HQ_PART") "RE0207399")
        (field (name "LCSC_PART") "C25744")
        (field (name "MANUFACTURER") "ROHM")
      )
      (libsource (lib "eagle-import") (part "10K-1%0402"))
    )
    (comp (ref "R149")
      (value "3.3K 1%")
      (footprint "eagle-import:_0603X4-1206")
      (fields
        (field (name "HQ_PART") "RE0093863")
        (field (name "LCSC_PART") "C1734380")
        (field (name "MANUFACTURER") "Yageo")
      )
      (libsource (lib "eagle-import") (part "3.3K-1%_ARRAY0603X4-1206"))
    )
    (comp (ref "R164")
      (value "10K 1%")
      (footprint "eagle-import:0402")
      (fields
        (field (name "HQ_PART") "RE0207399")
        (field (name "LCSC_PART") "C25744")
        (field (name "MANUFACTURER") "ROHM")
      )
      (libsource (lib "eagle-import") (part "10K-1%0402"))
    )
    (comp (ref "R165")
      (value "DNI")
      (footprint "eagle-import:R0201")
      (libsource (lib "eagle-import") (part "R0201"))
    )
    (comp (ref "R170")
      (value "DNI")
      (footprint "eagle-import:1206")
      (fields
        (field (name "PACKAGE") "1206")
        (field (name "HQ_PART") "RE0209081")
        (field (name "LCSC_PART") "C205296")
        (field (name "MANUFACTURER") "RALEC")
      )
      (libsource (lib "eagle-import") (part "0R1206"))
    )
    (comp (ref "RGTG")
      (value "DNI")
      (footprint "eagle-import:1X4")
      (libsource (lib "eagle-import") (part "CON-1X4"))
    )
    (comp (ref "T1")
      (value "BSS138")
      (footprint "eagle-import:SOT23")
      (fields (field (name "HQ_PART") "DS0190318") (field (name "MANUFACTURER") "HUASHUO"))
      (libsource (lib "eagle-import") (part "BSS138"))
    )
    (comp (ref "USB1")
      (value "USB-TYPE-C-018")
      (footprint "eagle-import:USB-C")
      (fields
        (field (name "HQ_PART") "ZHLM0322915")
        (field (name "LCSC_PART") "C2927038")
        (field (name "MANUFACTURER") "DEALON")
      )
      (libsource (lib "eagle-import") (part "USB_C-THT"))
    )
    (comp (ref "VBUS")
      (value "DNI")
      (footprint "eagle-import:TP-ROUND")
      (libsource (lib "eagle-import") (part "TP-ROUND"))
    )
    (comp (ref "C106")
      (value "1nF 25V")
      (footprint "eagle-import:0201")
      (fields
        (field (name "HQ_PART") "CA0136821")
        (field (name "LCSC_PART") "C7694325V")
        (field (name "MANUFACTURER") "Samsung")
      )
      (libsource (lib "eagle-import") (part "1NF-25V-0201"))
    )
    (comp (ref "C107")
      (value "1nF 25V")
      (footprint "eagle-import:0201")
      (fields
        (field (name "HQ_PART") "CA0136821")
        (field (name "LCSC_PART") "C7694325V")
        (field (name "MANUFACTURER") "Samsung")
      )
      (libsource (lib "eagle-import") (part "1NF-25V-0201"))
    )
    (comp (ref "C108")
      (value "1nF 25V")
      (footprint "eagle-import:0201")
      (fields
        (field (name "HQ_PART") "CA0136821")
        (field (name "LCSC_PART") "C7694325V")
        (field (name "MANUFACTURER") "Samsung")
      )
      (libsource (lib "eagle-import") (part "1NF-25V-0201"))
    )
    (comp (ref "C109")
      (value "1nF 25V")
      (footprint "eagle-import:0201")
      (fields
        (field (name "HQ_PART") "CA0136821")
        (field (name "LCSC_PART") "C7694325V")
        (field (name "MANUFACTURER") "Samsung")
      )
      (libsource (lib "eagle-import") (part "1NF-25V-0201"))
    )
    (comp (ref "C110")
      (value "1nF 25V")
      (footprint "eagle-import:0201")
      (fields
        (field (name "HQ_PART") "CA0136821")
        (field (name "LCSC_PART") "C7694325V")
        (field (name "MANUFACTURER") "Samsung")
      )
      (libsource (lib "eagle-import") (part "1NF-25V-0201"))
    )
    (comp (ref "C111")
      (value "1nF 25V")
      (footprint "eagle-import:0201")
      (fields
        (field (name "HQ_PART") "CA0136821")
        (field (name "LCSC_PART") "C7694325V")
        (field (name "MANUFACTURER") "Samsung")
      )
      (libsource (lib "eagle-import") (part "1NF-25V-0201"))
    )
    (comp (ref "C112")
      (value "1nF 25V")
      (footprint "eagle-import:0201")
      (fields
        (field (name "HQ_PART") "CA0136821")
        (field (name "LCSC_PART") "C7694325V")
        (field (name "MANUFACTURER") "Samsung")
      )
      (libsource (lib "eagle-import") (part "1NF-25V-0201"))
    )
    (comp (ref "C113")
      (value "1nF 25V")
      (footprint "eagle-import:0201")
      (fields
        (field (name "HQ_PART") "CA0136821")
        (field (name "LCSC_PART") "C7694325V")
        (field (name "MANUFACTURER") "Samsung")
      )
      (libsource (lib "eagle-import") (part "1NF-25V-0201"))
    )
    (comp (ref "OPT1")
      (value "ACPL-247-500E")
      (footprint "eagle-import:SO16")
      (fields
        (field (name "HQ_PART") "IS0001505")
        (field (name "LCSC_PART") "C188681")
        (field (name "MANUFACTURER") "Broadcom")
      )
      (libsource (lib "eagle-import") (part "ACPL-2471"))
    )
    (comp (ref "OPT2")
      (value "ACPL-247-500E")
      (footprint "eagle-import:SO16")
      (fields
        (field (name "HQ_PART") "IS0001505")
        (field (name "LCSC_PART") "C188681")
        (field (name "MANUFACTURER") "Broadcom")
      )
      (libsource (lib "eagle-import") (part "ACPL-2471"))
    )
    (comp (ref "R59")
      (value "1K 1%")
      (footprint "eagle-import:0201")
      (fields
        (field (name "HQ_PART") "RE0015967")
        (field (name "LCSC_PART") "C270365")
        (field (name "MANUFACTURER") "Yageo")
      )
      (libsource (lib "eagle-import") (part "1K-1%0201"))
    )
    (comp (ref "R63")
      (value "1K 1%")
      (footprint "eagle-import:_0603X4-1206")
      (fields
        (field (name "HQ_PART") "RE0022532")
        (field (name "LCSC_PART") "C110021")
        (field (name "MANUFACTURER") "Yageo")
      )
      (libsource (lib "eagle-import") (part "1K-1%_ARRAY0603X4-1206"))
    )
    (comp (ref "R64")
      (value "1K 1%")
      (footprint "eagle-import:_0603X4-1206")
      (fields
        (field (name "HQ_PART") "RE0022532")
        (field (name "LCSC_PART") "C110021")
        (field (name "MANUFACTURER") "Yageo")
      )
      (libsource (lib "eagle-import") (part "1K-1%_ARRAY0603X4-1206"))
    )
    (comp (ref "R89")
      (value "10K 1%")
      (footprint "eagle-import:_0603X4-1206")
      (fields
        (field (name "HQ_PART") "RE0094682")
        (field (name "LCSC_PART") "C110924")
        (field (name "MANUFACTURER") "Yageo")
      )
      (libsource (lib "eagle-import") (part "10K-1%_ARRAY0603X4-1206"))
    )
    (comp (ref "R90")
      (value "10K 1%")
      (footprint "eagle-import:_0603X4-1206")
      (fields
        (field (name "HQ_PART") "RE0094682")
        (field (name "LCSC_PART") "C110924")
        (field (name "MANUFACTURER") "Yageo")
      )
      (libsource (lib "eagle-import") (part "10K-1%_ARRAY0603X4-1206"))
    )
    (comp (ref "R153")
      (value "1K 1%")
      (footprint "eagle-import:0201")
      (fields
        (field (name "HQ_PART") "RE0015967")
        (field (name "LCSC_PART") "C270365")
        (field (name "MANUFACTURER") "Yageo")
      )
      (libsource (lib "eagle-import") (part "1K-1%0201"))
    )
    (comp (ref "R154")
      (value "1K 1%")
      (footprint "eagle-import:0201")
      (fields
        (field (name "HQ_PART") "RE0015967")
        (field (name "LCSC_PART") "C270365")
        (field (name "MANUFACTURER") "Yageo")
      )
      (libsource (lib "eagle-import") (part "1K-1%0201"))
    )
    (comp (ref "R155")
      (value "1K 1%")
      (footprint "eagle-import:0201")
      (fields
        (field (name "HQ_PART") "RE0015967")
        (field (name "LCSC_PART") "C270365")
        (field (name "MANUFACTURER") "Yageo")
      )
      (libsource (lib "eagle-import") (part "1K-1%0201"))
    )
    (comp (ref "R156")
      (value "1K 1%")
      (footprint "eagle-import:0201")
      (fields
        (field (name "HQ_PART") "RE0015967")
        (field (name "LCSC_PART") "C270365")
        (field (name "MANUFACTURER") "Yageo")
      )
      (libsource (lib "eagle-import") (part "1K-1%0201"))
    )
    (comp (ref "R157")
      (value "1K 1%")
      (footprint "eagle-import:0201")
      (fields
        (field (name "HQ_PART") "RE0015967")
        (field (name "LCSC_PART") "C270365")
        (field (name "MANUFACTURER") "Yageo")
      )
      (libsource (lib "eagle-import") (part "1K-1%0201"))
    )
    (comp (ref "R158")
      (value "1K 1%")
      (footprint "eagle-import:0201")
      (fields
        (field (name "HQ_PART") "RE0015967")
        (field (name "LCSC_PART") "C270365")
        (field (name "MANUFACTURER") "Yageo")
      )
      (libsource (lib "eagle-import") (part "1K-1%0201"))
    )
    (comp (ref "R159")
      (value "1K 1%")
      (footprint "eagle-import:0201")
      (fields
        (field (name "HQ_PART") "RE0015967")
        (field (name "LCSC_PART") "C270365")
        (field (name "MANUFACTURER") "Yageo")
      )
      (libsource (lib "eagle-import") (part "1K-1%0201"))
    )
    (comp (ref "3V3A")
      (value "DNI")
      (footprint "eagle-import:TP-ROUND")
      (libsource (lib "eagle-import") (part "TP-ROUND"))
    )
    (comp (ref "C79")
      (value "100nF 25V")
      (footprint "eagle-import:0402")
      (fields
        (field (name "HQ_PART") "CA0176807")
        (field (name "LCSC_PART") "C56392")
        (field (name "MANUFACTURER") "Walsin")
      )
      (libsource (lib "eagle-import") (part "100NF-25V-0402"))
    )
    (comp (ref "C80")
      (value "22nF 50V")
      (footprint "eagle-import:0402")
      (fields
        (field (name "HQ_PART") "CA0171190")
        (field (name "LCSC_PART") "C1532")
        (field (name "MANUFACTURER") "Samsung")
      )
      (libsource (lib "eagle-import") (part "22NF-50V0402"))
    )
    (comp (ref "C81")
      (value "6.8nF 50V")
      (footprint "eagle-import:0201")
      (fields
        (field (name "HQ_PART") "CA0363038")
        (field (name "LCSC_PART") "C285015")
        (field (name "MANUFACTURER") "FH")
      )
      (libsource (lib "eagle-import") (part "6.8NF-50V0201"))
    )
    (comp (ref "C82")
      (value "6.8nF 50V")
      (footprint "eagle-import:0201")
      (fields
        (field (name "HQ_PART") "CA0363038")
        (field (name "LCSC_PART") "C285015")
        (field (name "MANUFACTURER") "FH")
      )
      (libsource (lib "eagle-import") (part "6.8NF-50V0201"))
    )
    (comp (ref "C83")
      (value "1nF 2kV")
      (footprint "eagle-import:1206")
      (fields
        (field (name "HQ_PART") "CA0134884")
        (field (name "LCSC_PART") "C173242")
        (field (name "MANUFACTURER") "Johanson Dielectrics ")
      )
      (libsource (lib "eagle-import") (part "1NF-2KV"))
    )
    (comp (ref "C84")
      (value "100nF 25V")
      (footprint "eagle-import:0201")
      (fields
        (field (name "HQ_PART") "CA0183221")
        (field (name "LCSC_PART") "C76939")
        (field (name "MANUFACTURER") "Samsung")
      )
      (libsource (lib "eagle-import") (part "100NF-25V-0201"))
    )
    (comp (ref "C85")
      (value "4.7uF 25V")
      (footprint "eagle-import:0402")
      (fields
        (field (name "HQ_PART") "ZHLM0023346")
        (field (name "LCSC_PART") "C22367824")
        (field (name "MANUFACTURER") "Murata")
      )
      (libsource (lib "eagle-import") (part "4.7UF-25V0402"))
    )
    (comp (ref "C86")
      (value "18pF 50V")
      (footprint "eagle-import:0201")
      (fields
        (field (name "HQ_PART") "CA0486739")
        (field (name "LCSC_PART") "C62164")
        (field (name "MANUFACTURER") "Yageo")
      )
      (libsource (lib "eagle-import") (part "18PF-50V-0201"))
    )
    (comp (ref "C87")
      (value "18pF 50V")
      (footprint "eagle-import:0201")
      (fields
        (field (name "HQ_PART") "CA0486739")
        (field (name "LCSC_PART") "C62164")
        (field (name "MANUFACTURER") "Yageo")
      )
      (libsource (lib "eagle-import") (part "18PF-50V-0201"))
    )
    (comp (ref "C88")
      (value "100nF 25V")
      (footprint "eagle-import:0201")
      (fields
        (field (name "HQ_PART") "CA0183221")
        (field (name "LCSC_PART") "C76939")
        (field (name "MANUFACTURER") "Samsung")
      )
      (libsource (lib "eagle-import") (part "100NF-25V-0201"))
    )
    (comp (ref "C89")
      (value "100nF 25V")
      (footprint "eagle-import:0201")
      (fields
        (field (name "HQ_PART") "CA0183221")
        (field (name "LCSC_PART") "C76939")
        (field (name "MANUFACTURER") "Samsung")
      )
      (libsource (lib "eagle-import") (part "100NF-25V-0201"))
    )
    (comp (ref "C90")
      (value "100nF 25V")
      (footprint "eagle-import:0201")
      (fields
        (field (name "HQ_PART") "CA0183221")
        (field (name "LCSC_PART") "C76939")
        (field (name "MANUFACTURER") "Samsung")
      )
      (libsource (lib "eagle-import") (part "100NF-25V-0201"))
    )
    (comp (ref "C91")
      (value "100nF 25V")
      (footprint "eagle-import:0201")
      (fields
        (field (name "HQ_PART") "CA0183221")
        (field (name "LCSC_PART") "C76939")
        (field (name "MANUFACTURER") "Samsung")
      )
      (libsource (lib "eagle-import") (part "100NF-25V-0201"))
    )
    (comp (ref "C92")
      (value "100nF 25V")
      (footprint "eagle-import:0201")
      (fields
        (field (name "HQ_PART") "CA0183221")
        (field (name "LCSC_PART") "C76939")
        (field (name "MANUFACTURER") "Samsung")
      )
      (libsource (lib "eagle-import") (part "100NF-25V-0201"))
    )
    (comp (ref "C93")
      (value "100nF 25V")
      (footprint "eagle-import:0201")
      (fields
        (field (name "HQ_PART") "CA0183221")
        (field (name "LCSC_PART") "C76939")
        (field (name "MANUFACTURER") "Samsung")
      )
      (libsource (lib "eagle-import") (part "100NF-25V-0201"))
    )
    (comp (ref "C94")
      (value "100nF 25V")
      (footprint "eagle-import:0201")
      (fields
        (field (name "HQ_PART") "CA0183221")
        (field (name "LCSC_PART") "C76939")
        (field (name "MANUFACTURER") "Samsung")
      )
      (libsource (lib "eagle-import") (part "100NF-25V-0201"))
    )
    (comp (ref "C95")
      (value "100nF 25V")
      (footprint "eagle-import:0201")
      (fields
        (field (name "HQ_PART") "CA0183221")
        (field (name "LCSC_PART") "C76939")
        (field (name "MANUFACTURER") "Samsung")
      )
      (libsource (lib "eagle-import") (part "100NF-25V-0201"))
    )
    (comp (ref "C96")
      (value "100nF 25V")
      (footprint "eagle-import:0201")
      (fields
        (field (name "HQ_PART") "CA0183221")
        (field (name "LCSC_PART") "C76939")
        (field (name "MANUFACTURER") "Samsung")
      )
      (libsource (lib "eagle-import") (part "100NF-25V-0201"))
    )
    (comp (ref "ETH1")
      (value "J1B1211CCD")
      (footprint "eagle-import:J1B1211CCD")
      (fields
        (field (name "HQ_PART") "UN0002907")
        (field (name "LCSC_PART") "C910371")
        (field (name "MANUFACTURER") "WIZnet")
      )
      (libsource (lib "eagle-import") (part "J1B1211CCD"))
    )
    (comp (ref "IC20")
      (value "W5500")
      (footprint "eagle-import:LQFP48")
      (fields
        (field (name "HQ_PART") "IC0084426")
        (field (name "LCSC_PART") "C32843")
        (field (name "MANUFACTURER") "WIZNET")
      )
      (libsource (lib "eagle-import") (part "W5500"))
    )
    (comp (ref "L4")
      (value "BLM18EG221TN1D")
      (footprint "eagle-import:0603")
      (fields
        (field (name "HQ_PART") "WF0012312")
        (field (name "LCSC_PART") "C113025")
        (field (name "MANUFACTURER") "Murata")
      )
      (libsource (lib "eagle-import") (part "BLM18EG221TN1D"))
    )
    (comp (ref "R110")
      (value "1M 1%")
      (footprint "eagle-import:1206")
      (fields
        (field (name "HQ_PART") "RE0188103")
        (field (name "LCSC_PART") "C17927")
        (field (name "MANUFACTURER") "Uniohm")
      )
      (libsource (lib "eagle-import") (part "1M-1%1206"))
    )
    (comp (ref "R133")
      (value "3.3R 1%")
      (footprint "eagle-import:0201")
      (fields
        (field (name "HQ_PART") "RE0422979")
        (field (name "LCSC_PART") "C158547")
        (field (name "MANUFACTURER") "Uniohm")
      )
      (libsource (lib "eagle-import") (part "3.3R-1%0201"))
    )
    (comp (ref "R134")
      (value "3.3R 1%")
      (footprint "eagle-import:0201")
      (fields
        (field (name "HQ_PART") "RE0422979")
        (field (name "LCSC_PART") "C158547")
        (field (name "MANUFACTURER") "Uniohm")
      )
      (libsource (lib "eagle-import") (part "3.3R-1%0201"))
    )
    (comp (ref "R135")
      (value "3.3R 1%")
      (footprint "eagle-import:0201")
      (fields
        (field (name "HQ_PART") "RE0422979")
        (field (name "LCSC_PART") "C158547")
        (field (name "MANUFACTURER") "Uniohm")
      )
      (libsource (lib "eagle-import") (part "3.3R-1%0201"))
    )
    (comp (ref "R136")
      (value "3.3R 1%")
      (footprint "eagle-import:0201")
      (fields
        (field (name "HQ_PART") "RE0422979")
        (field (name "LCSC_PART") "C158547")
        (field (name "MANUFACTURER") "Uniohm")
      )
      (libsource (lib "eagle-import") (part "3.3R-1%0201"))
    )
    (comp (ref "R137")
      (value "49.9R 1%")
      (footprint "eagle-import:0201")
      (fields
        (field (name "HQ_PART") "RE0721921")
        (field (name "LCSC_PART") "C155744")
        (field (name "MANUFACTURER") "FH")
      )
      (libsource (lib "eagle-import") (part "49.9R-1%0201"))
    )
    (comp (ref "R138")
      (value "49.9R 1%")
      (footprint "eagle-import:0201")
      (fields
        (field (name "HQ_PART") "RE0721921")
        (field (name "LCSC_PART") "C155744")
        (field (name "MANUFACTURER") "FH")
      )
      (libsource (lib "eagle-import") (part "49.9R-1%0201"))
    )
    (comp (ref "R139")
      (value "49.9R 1%")
      (footprint "eagle-import:0201")
      (fields
        (field (name "HQ_PART") "RE0721921")
        (field (name "LCSC_PART") "C155744")
        (field (name "MANUFACTURER") "FH")
      )
      (libsource (lib "eagle-import") (part "49.9R-1%0201"))
    )
    (comp (ref "R140")
      (value "49.9R 1%")
      (footprint "eagle-import:0201")
      (fields
        (field (name "HQ_PART") "RE0721921")
        (field (name "LCSC_PART") "C155744")
        (field (name "MANUFACTURER") "FH")
      )
      (libsource (lib "eagle-import") (part "49.9R-1%0201"))
    )
    (comp (ref "R141")
      (value "470R 1%")
      (footprint "eagle-import:0402")
      (fields
        (field (name "HQ_PART") "RE0205922")
        (field (name "LCSC_PART") "C25117")
        (field (name "MANUFACTURER") "Panasonic")
      )
      (libsource (lib "eagle-import") (part "470R-1%0402"))
    )
    (comp (ref "R142")
      (value "470R 1%")
      (footprint "eagle-import:0402")
      (fields
        (field (name "HQ_PART") "RE0205922")
        (field (name "LCSC_PART") "C25117")
        (field (name "MANUFACTURER") "Panasonic")
      )
      (libsource (lib "eagle-import") (part "470R-1%0402"))
    )
    (comp (ref "R143")
      (value "12.4K 1%")
      (footprint "eagle-import:0201")
      (fields
        (field (name "HQ_PART") "RE0186667")
        (field (name "LCSC_PART") "C423760")
        (field (name "MANUFACTURER") "Yageo")
      )
      (libsource (lib "eagle-import") (part "12.4K-1%0201"))
    )
    (comp (ref "R144")
      (value "1M 1%")
      (footprint "eagle-import:0201")
      (fields
        (field (name "HQ_PART") "RE0422946")
        (field (name "LCSC_PART") "C295786")
        (field (name "MANUFACTURER") "Yageo")
      )
      (libsource (lib "eagle-import") (part "1M-1%0201"))
    )
    (comp (ref "R145")
      (value "4.7K 1%")
      (footprint "eagle-import:0201")
      (fields
        (field (name "HQ_PART") "RE0208670")
        (field (name "LCSC_PART") "C270346")
        (field (name "MANUFACTURER") "RALEC")
      )
      (libsource (lib "eagle-import") (part "4.7K-1%0201"))
    )
    (comp (ref "R146")
      (value "470R 1%")
      (footprint "eagle-import:0402")
      (fields
        (field (name "HQ_PART") "RE0205922")
        (field (name "LCSC_PART") "C25117")
        (field (name "MANUFACTURER") "Panasonic")
      )
      (libsource (lib "eagle-import") (part "470R-1%0402"))
    )
    (comp (ref "X2")
      (value "25MHz")
      (footprint "eagle-import:WE-XTAL_CFPX-180")
      (fields
        (field (name "HQ_PART") "CR0250343")
        (field (name "LCSC_PART") "C13740")
        (field (name "MANUFACTURER") "Epson")
      )
      (libsource (lib "eagle-import") (part "CRYSTAL-3225X322525MOB4SI"))
    )
    (comp (ref "C27")
      (value "33nF 50V")
      (footprint "eagle-import:0805")
      (fields
        (field (name "HQ_PART") "UN0000063")
        (field (name "LCSC_PART") "C107150")
        (field (name "MANUFACTURER") "FH")
      )
      (libsource (lib "eagle-import") (part "33NF-50V0805"))
    )
    (comp (ref "C28")
      (value "33nF 50V")
      (footprint "eagle-import:0805")
      (fields
        (field (name "HQ_PART") "UN0000063")
        (field (name "LCSC_PART") "C107150")
        (field (name "MANUFACTURER") "FH")
      )
      (libsource (lib "eagle-import") (part "33NF-50V0805"))
    )
    (comp (ref "C29")
      (value "33nF 50V")
      (footprint "eagle-import:0805")
      (fields
        (field (name "HQ_PART") "UN0000063")
        (field (name "LCSC_PART") "C107150")
        (field (name "MANUFACTURER") "FH")
      )
      (libsource (lib "eagle-import") (part "33NF-50V0805"))
    )
    (comp (ref "C39")
      (value "33nF 50V")
      (footprint "eagle-import:0805")
      (fields
        (field (name "HQ_PART") "UN0000063")
        (field (name "LCSC_PART") "C107150")
        (field (name "MANUFACTURER") "FH")
      )
      (libsource (lib "eagle-import") (part "33NF-50V0805"))
    )
    (comp (ref "C40")
      (value "33nF 50V")
      (footprint "eagle-import:0805")
      (fields
        (field (name "HQ_PART") "UN0000063")
        (field (name "LCSC_PART") "C107150")
        (field (name "MANUFACTURER") "FH")
      )
      (libsource (lib "eagle-import") (part "33NF-50V0805"))
    )
    (comp (ref "C41")
      (value "33nF 50V")
      (footprint "eagle-import:0805")
      (fields
        (field (name "HQ_PART") "UN0000063")
        (field (name "LCSC_PART") "C107150")
        (field (name "MANUFACTURER") "FH")
      )
      (libsource (lib "eagle-import") (part "33NF-50V0805"))
    )
    (comp (ref "C48")
      (value "33nF 50V")
      (footprint "eagle-import:0805")
      (fields
        (field (name "HQ_PART") "UN0000063")
        (field (name "LCSC_PART") "C107150")
        (field (name "MANUFACTURER") "FH")
      )
      (libsource (lib "eagle-import") (part "33NF-50V0805"))
    )
    (comp (ref "C49")
      (value "33nF 50V")
      (footprint "eagle-import:0805")
      (fields
        (field (name "HQ_PART") "UN0000063")
        (field (name "LCSC_PART") "C107150")
        (field (name "MANUFACTURER") "FH")
      )
      (libsource (lib "eagle-import") (part "33NF-50V0805"))
    )
    (comp (ref "C50")
      (value "33nF 50V")
      (footprint "eagle-import:0805")
      (fields
        (field (name "HQ_PART") "UN0000063")
        (field (name "LCSC_PART") "C107150")
        (field (name "MANUFACTURER") "FH")
      )
      (libsource (lib "eagle-import") (part "33NF-50V0805"))
    )
    (comp (ref "C54")
      (value "33nF 50V")
      (footprint "eagle-import:0805")
      (fields
        (field (name "HQ_PART") "UN0000063")
        (field (name "LCSC_PART") "C107150")
        (field (name "MANUFACTURER") "FH")
      )
      (libsource (lib "eagle-import") (part "33NF-50V0805"))
    )
    (comp (ref "C55")
      (value "33nF 50V")
      (footprint "eagle-import:0805")
      (fields
        (field (name "HQ_PART") "UN0000063")
        (field (name "LCSC_PART") "C107150")
        (field (name "MANUFACTURER") "FH")
      )
      (libsource (lib "eagle-import") (part "33NF-50V0805"))
    )
    (comp (ref "C56")
      (value "33nF 50V")
      (footprint "eagle-import:0805")
      (fields
        (field (name "HQ_PART") "UN0000063")
        (field (name "LCSC_PART") "C107150")
        (field (name "MANUFACTURER") "FH")
      )
      (libsource (lib "eagle-import") (part "33NF-50V0805"))
    )
    (comp (ref "IC7")
      (value "HLW8032")
      (footprint "eagle-import:SO8")
      (fields
        (field (name "HQ_PART") "MD0751024")
        (field (name "LCSC_PART") "C128023")
        (field (name "MANUFACTURER") "Hiliwei Tech")
      )
      (libsource (lib "eagle-import") (part "HLW8032"))
    )
    (comp (ref "IC11")
      (value "HLW8032")
      (footprint "eagle-import:SO8")
      (fields
        (field (name "HQ_PART") "MD0751024")
        (field (name "LCSC_PART") "C128023")
        (field (name "MANUFACTURER") "Hiliwei Tech")
      )
      (libsource (lib "eagle-import") (part "HLW8032"))
    )
    (comp (ref "IC14")
      (value "HLW8032")
      (footprint "eagle-import:SO8")
      (fields
        (field (name "HQ_PART") "MD0751024")
        (field (name "LCSC_PART") "C128023")
        (field (name "MANUFACTURER") "Hiliwei Tech")
      )
      (libsource (lib "eagle-import") (part "HLW8032"))
    )
    (comp (ref "IC16")
      (value "HLW8032")
      (footprint "eagle-import:SO8")
      (fields
        (field (name "HQ_PART") "MD0751024")
        (field (name "LCSC_PART") "C128023")
        (field (name "MANUFACTURER") "Hiliwei Tech")
      )
      (libsource (lib "eagle-import") (part "HLW8032"))
    )
    (comp (ref "L_OUT5")
      (value "FASTON-1217861-1")
      (footprint "eagle-import:1217861-1")
      (fields
        (field (name "LCSC_PART") "C428480")
        (field (name "MANUFACTURER") "TE CONNECTIVITY")
        (field (name "MPN") "1217861-1")
      )
      (libsource (lib "eagle-import") (part "FASTON-1217861-1"))
    )
    (comp (ref "L_OUT6")
      (value "FASTON-1217861-1")
      (footprint "eagle-import:1217861-1")
      (fields
        (field (name "LCSC_PART") "C428480")
        (field (name "MANUFACTURER") "TE CONNECTIVITY")
        (field (name "MPN") "1217861-1")
      )
      (libsource (lib "eagle-import") (part "FASTON-1217861-1"))
    )
    (comp (ref "L_OUT7")
      (value "FASTON-1217861-1")
      (footprint "eagle-import:1217861-1")
      (fields
        (field (name "LCSC_PART") "C428480")
        (field (name "MANUFACTURER") "TE CONNECTIVITY")
        (field (name "MPN") "1217861-1")
      )
      (libsource (lib "eagle-import") (part "FASTON-1217861-1"))
    )
    (comp (ref "L_OUT8")
      (value "FASTON-1217861-1")
      (footprint "eagle-import:1217861-1")
      (fields
        (field (name "LCSC_PART") "C428480")
        (field (name "MANUFACTURER") "TE CONNECTIVITY")
        (field (name "MPN") "1217861-1")
      )
      (libsource (lib "eagle-import") (part "FASTON-1217861-1"))
    )
    (comp (ref "N_OUT5")
      (value "FASTON-1217861-1")
      (footprint "eagle-import:1217861-1")
      (fields
        (field (name "LCSC_PART") "C428480")
        (field (name "MANUFACTURER") "TE CONNECTIVITY")
        (field (name "MPN") "1217861-1")
      )
      (libsource (lib "eagle-import") (part "FASTON-1217861-1"))
    )
    (comp (ref "N_OUT6")
      (value "FASTON-1217861-1")
      (footprint "eagle-import:1217861-1")
      (fields
        (field (name "LCSC_PART") "C428480")
        (field (name "MANUFACTURER") "TE CONNECTIVITY")
        (field (name "MPN") "1217861-1")
      )
      (libsource (lib "eagle-import") (part "FASTON-1217861-1"))
    )
    (comp (ref "N_OUT7")
      (value "FASTON-1217861-1")
      (footprint "eagle-import:1217861-1")
      (fields
        (field (name "LCSC_PART") "C428480")
        (field (name "MANUFACTURER") "TE CONNECTIVITY")
        (field (name "MPN") "1217861-1")
      )
      (libsource (lib "eagle-import") (part "FASTON-1217861-1"))
    )
    (comp (ref "N_OUT8")
      (value "FASTON-1217861-1")
      (footprint "eagle-import:1217861-1")
      (fields
        (field (name "LCSC_PART") "C428480")
        (field (name "MANUFACTURER") "TE CONNECTIVITY")
        (field (name "MPN") "1217861-1")
      )
      (libsource (lib "eagle-import") (part "FASTON-1217861-1"))
    )
    (comp (ref "R26")
      (value "0.002R 1%")
      (footprint "eagle-import:2512")
      (fields
        (field (name "HQ_PART") "RE0716514")
        (field (name "LCSC_PART") "C728320")
        (field (name "MANUFACTURER") "Viking")
      )
      (libsource (lib "eagle-import") (part "0.002R-1%2512"))
    )
    (comp (ref "R27")
      (value "0.002R 1%")
      (footprint "eagle-import:2512")
      (fields
        (field (name "HQ_PART") "RE0716514")
        (field (name "LCSC_PART") "C728320")
        (field (name "MANUFACTURER") "Viking")
      )
      (libsource (lib "eagle-import") (part "0.002R-1%2512"))
    )
    (comp (ref "R28")
      (value "0.002R 1%")
      (footprint "eagle-import:2512")
      (fields
        (field (name "HQ_PART") "RE0716514")
        (field (name "LCSC_PART") "C728320")
        (field (name "MANUFACTURER") "Viking")
      )
      (libsource (lib "eagle-import") (part "0.002R-1%2512"))
    )
    (comp (ref "R29")
      (value "0.002R 1%")
      (footprint "eagle-import:2512")
      (fields
        (field (name "HQ_PART") "RE0716514")
        (field (name "LCSC_PART") "C728320")
        (field (name "MANUFACTURER") "Viking")
      )
      (libsource (lib "eagle-import") (part "0.002R-1%2512"))
    )
    (comp (ref "R41")
      (value "1K 1%")
      (footprint "eagle-import:0805")
      (fields
        (field (name "HQ_PART") "RE0203459")
        (field (name "LCSC_PART") "C17513")
        (field (name "MANUFACTURER") "FH")
      )
      (libsource (lib "eagle-import") (part "1K-1%0805"))
    )
    (comp (ref "R42")
      (value "1K 1%")
      (footprint "eagle-import:0805")
      (fields
        (field (name "HQ_PART") "RE0203459")
        (field (name "LCSC_PART") "C17513")
        (field (name "MANUFACTURER") "FH")
      )
      (libsource (lib "eagle-import") (part "1K-1%0805"))
    )
    (comp (ref "R43")
      (value "0.002R 1%")
      (footprint "eagle-import:2512")
      (fields
        (field (name "HQ_PART") "RE0716514")
        (field (name "LCSC_PART") "C728320")
        (field (name "MANUFACTURER") "Viking")
      )
      (libsource (lib "eagle-import") (part "0.002R-1%2512"))
    )
    (comp (ref "R44")
      (value "470K 1%")
      (footprint "eagle-import:0805")
      (fields
        (field (name "HQ_PART") "RE0205756")
        (field (name "LCSC_PART") "C17709")
        (field (name "MANUFACTURER") "Panasonic")
      )
      (libsource (lib "eagle-import") (part "470K-1%0805"))
    )
    (comp (ref "R45")
      (value "470K 1%")
      (footprint "eagle-import:0805")
      (fields
        (field (name "HQ_PART") "RE0205756")
        (field (name "LCSC_PART") "C17709")
        (field (name "MANUFACTURER") "Panasonic")
      )
      (libsource (lib "eagle-import") (part "470K-1%0805"))
    )
    (comp (ref "R46")
      (value "470K 1%")
      (footprint "eagle-import:0805")
      (fields
        (field (name "HQ_PART") "RE0205756")
        (field (name "LCSC_PART") "C17709")
        (field (name "MANUFACTURER") "Panasonic")
      )
      (libsource (lib "eagle-import") (part "470K-1%0805"))
    )
    (comp (ref "R47")
      (value "470K 1%")
      (footprint "eagle-import:0805")
      (fields
        (field (name "HQ_PART") "RE0205756")
        (field (name "LCSC_PART") "C17709")
        (field (name "MANUFACTURER") "Panasonic")
      )
      (libsource (lib "eagle-import") (part "470K-1%0805"))
    )
    (comp (ref "R48")
      (value "1K 1%")
      (footprint "eagle-import:0805")
      (fields
        (field (name "HQ_PART") "RE0203459")
        (field (name "LCSC_PART") "C17513")
        (field (name "MANUFACTURER") "FH")
      )
      (libsource (lib "eagle-import") (part "1K-1%0805"))
    )
    (comp (ref "R73")
      (value "1K 1%")
      (footprint "eagle-import:0805")
      (fields
        (field (name "HQ_PART") "RE0203459")
        (field (name "LCSC_PART") "C17513")
        (field (name "MANUFACTURER") "FH")
      )
      (libsource (lib "eagle-import") (part "1K-1%0805"))
    )
    (comp (ref "R74")
      (value "1K 1%")
      (footprint "eagle-import:0805")
      (fields
        (field (name "HQ_PART") "RE0203459")
        (field (name "LCSC_PART") "C17513")
        (field (name "MANUFACTURER") "FH")
      )
      (libsource (lib "eagle-import") (part "1K-1%0805"))
    )
    (comp (ref "R75")
      (value "0.002R 1%")
      (footprint "eagle-import:2512")
      (fields
        (field (name "HQ_PART") "RE0716514")
        (field (name "LCSC_PART") "C728320")
        (field (name "MANUFACTURER") "Viking")
      )
      (libsource (lib "eagle-import") (part "0.002R-1%2512"))
    )
    (comp (ref "R76")
      (value "470K 1%")
      (footprint "eagle-import:0805")
      (fields
        (field (name "HQ_PART") "RE0205756")
        (field (name "LCSC_PART") "C17709")
        (field (name "MANUFACTURER") "Panasonic")
      )
      (libsource (lib "eagle-import") (part "470K-1%0805"))
    )
    (comp (ref "R77")
      (value "470K 1%")
      (footprint "eagle-import:0805")
      (fields
        (field (name "HQ_PART") "RE0205756")
        (field (name "LCSC_PART") "C17709")
        (field (name "MANUFACTURER") "Panasonic")
      )
      (libsource (lib "eagle-import") (part "470K-1%0805"))
    )
    (comp (ref "R78")
      (value "470K 1%")
      (footprint "eagle-import:0805")
      (fields
        (field (name "HQ_PART") "RE0205756")
        (field (name "LCSC_PART") "C17709")
        (field (name "MANUFACTURER") "Panasonic")
      )
      (libsource (lib "eagle-import") (part "470K-1%0805"))
    )
    (comp (ref "R79")
      (value "470K 1%")
      (footprint "eagle-import:0805")
      (fields
        (field (name "HQ_PART") "RE0205756")
        (field (name "LCSC_PART") "C17709")
        (field (name "MANUFACTURER") "Panasonic")
      )
      (libsource (lib "eagle-import") (part "470K-1%0805"))
    )
    (comp (ref "R80")
      (value "1K 1%")
      (footprint "eagle-import:0805")
      (fields
        (field (name "HQ_PART") "RE0203459")
        (field (name "LCSC_PART") "C17513")
        (field (name "MANUFACTURER") "FH")
      )
      (libsource (lib "eagle-import") (part "1K-1%0805"))
    )
    (comp (ref "R97")
      (value "1K 1%")
      (footprint "eagle-import:0805")
      (fields
        (field (name "HQ_PART") "RE0203459")
        (field (name "LCSC_PART") "C17513")
        (field (name "MANUFACTURER") "FH")
      )
      (libsource (lib "eagle-import") (part "1K-1%0805"))
    )
    (comp (ref "R98")
      (value "1K 1%")
      (footprint "eagle-import:0805")
      (fields
        (field (name "HQ_PART") "RE0203459")
        (field (name "LCSC_PART") "C17513")
        (field (name "MANUFACTURER") "FH")
      )
      (libsource (lib "eagle-import") (part "1K-1%0805"))
    )
    (comp (ref "R99")
      (value "0.002R 1%")
      (footprint "eagle-import:2512")
      (fields
        (field (name "HQ_PART") "RE0716514")
        (field (name "LCSC_PART") "C728320")
        (field (name "MANUFACTURER") "Viking")
      )
      (libsource (lib "eagle-import") (part "0.002R-1%2512"))
    )
    (comp (ref "R100")
      (value "470K 1%")
      (footprint "eagle-import:0805")
      (fields
        (field (name "HQ_PART") "RE0205756")
        (field (name "LCSC_PART") "C17709")
        (field (name "MANUFACTURER") "Panasonic")
      )
      (libsource (lib "eagle-import") (part "470K-1%0805"))
    )
    (comp (ref "R101")
      (value "470K 1%")
      (footprint "eagle-import:0805")
      (fields
        (field (name "HQ_PART") "RE0205756")
        (field (name "LCSC_PART") "C17709")
        (field (name "MANUFACTURER") "Panasonic")
      )
      (libsource (lib "eagle-import") (part "470K-1%0805"))
    )
    (comp (ref "R102")
      (value "470K 1%")
      (footprint "eagle-import:0805")
      (fields
        (field (name "HQ_PART") "RE0205756")
        (field (name "LCSC_PART") "C17709")
        (field (name "MANUFACTURER") "Panasonic")
      )
      (libsource (lib "eagle-import") (part "470K-1%0805"))
    )
    (comp (ref "R103")
      (value "470K 1%")
      (footprint "eagle-import:0805")
      (fields
        (field (name "HQ_PART") "RE0205756")
        (field (name "LCSC_PART") "C17709")
        (field (name "MANUFACTURER") "Panasonic")
      )
      (libsource (lib "eagle-import") (part "470K-1%0805"))
    )
    (comp (ref "R104")
      (value "1K 1%")
      (footprint "eagle-import:0805")
      (fields
        (field (name "HQ_PART") "RE0203459")
        (field (name "LCSC_PART") "C17513")
        (field (name "MANUFACTURER") "FH")
      )
      (libsource (lib "eagle-import") (part "1K-1%0805"))
    )
    (comp (ref "R113")
      (value "1K 1%")
      (footprint "eagle-import:0805")
      (fields
        (field (name "HQ_PART") "RE0203459")
        (field (name "LCSC_PART") "C17513")
        (field (name "MANUFACTURER") "FH")
      )
      (libsource (lib "eagle-import") (part "1K-1%0805"))
    )
    (comp (ref "R114")
      (value "1K 1%")
      (footprint "eagle-import:0805")
      (fields
        (field (name "HQ_PART") "RE0203459")
        (field (name "LCSC_PART") "C17513")
        (field (name "MANUFACTURER") "FH")
      )
      (libsource (lib "eagle-import") (part "1K-1%0805"))
    )
    (comp (ref "R115")
      (value "0.002R 1%")
      (footprint "eagle-import:2512")
      (fields
        (field (name "HQ_PART") "RE0716514")
        (field (name "LCSC_PART") "C728320")
        (field (name "MANUFACTURER") "Viking")
      )
      (libsource (lib "eagle-import") (part "0.002R-1%2512"))
    )
    (comp (ref "R116")
      (value "470K 1%")
      (footprint "eagle-import:0805")
      (fields
        (field (name "HQ_PART") "RE0205756")
        (field (name "LCSC_PART") "C17709")
        (field (name "MANUFACTURER") "Panasonic")
      )
      (libsource (lib "eagle-import") (part "470K-1%0805"))
    )
    (comp (ref "R117")
      (value "470K 1%")
      (footprint "eagle-import:0805")
      (fields
        (field (name "HQ_PART") "RE0205756")
        (field (name "LCSC_PART") "C17709")
        (field (name "MANUFACTURER") "Panasonic")
      )
      (libsource (lib "eagle-import") (part "470K-1%0805"))
    )
    (comp (ref "R118")
      (value "470K 1%")
      (footprint "eagle-import:0805")
      (fields
        (field (name "HQ_PART") "RE0205756")
        (field (name "LCSC_PART") "C17709")
        (field (name "MANUFACTURER") "Panasonic")
      )
      (libsource (lib "eagle-import") (part "470K-1%0805"))
    )
    (comp (ref "R119")
      (value "470K 1%")
      (footprint "eagle-import:0805")
      (fields
        (field (name "HQ_PART") "RE0205756")
        (field (name "LCSC_PART") "C17709")
        (field (name "MANUFACTURER") "Panasonic")
      )
      (libsource (lib "eagle-import") (part "470K-1%0805"))
    )
    (comp (ref "R120")
      (value "1K 1%")
      (footprint "eagle-import:0805")
      (fields
        (field (name "HQ_PART") "RE0203459")
        (field (name "LCSC_PART") "C17513")
        (field (name "MANUFACTURER") "FH")
      )
      (libsource (lib "eagle-import") (part "1K-1%0805"))
    )
    (comp (ref "C19")
      (value "100nF 25V")
      (footprint "eagle-import:0402")
      (fields
        (field (name "HQ_PART") "CA0176807")
        (field (name "LCSC_PART") "C56392")
        (field (name "MANUFACTURER") "Walsin")
      )
      (libsource (lib "eagle-import") (part "100NF-25V-0402"))
    )
    (comp (ref "C20")
      (value "100nF 25V")
      (footprint "eagle-import:0402")
      (fields
        (field (name "HQ_PART") "CA0176807")
        (field (name "LCSC_PART") "C56392")
        (field (name "MANUFACTURER") "Walsin")
      )
      (libsource (lib "eagle-import") (part "100NF-25V-0402"))
    )
    (comp (ref "C33")
      (value "100nF 25V")
      (footprint "eagle-import:0402")
      (fields
        (field (name "HQ_PART") "CA0176807")
        (field (name "LCSC_PART") "C56392")
        (field (name "MANUFACTURER") "Walsin")
      )
      (libsource (lib "eagle-import") (part "100NF-25V-0402"))
    )
    (comp (ref "C34")
      (value "100nF 25V")
      (footprint "eagle-import:0402")
      (fields
        (field (name "HQ_PART") "CA0176807")
        (field (name "LCSC_PART") "C56392")
        (field (name "MANUFACTURER") "Walsin")
      )
      (libsource (lib "eagle-import") (part "100NF-25V-0402"))
    )
    (comp (ref "C103")
      (value "100nF 25V")
      (footprint "eagle-import:0201")
      (fields
        (field (name "HQ_PART") "CA0183221")
        (field (name "LCSC_PART") "C76939")
        (field (name "MANUFACTURER") "Samsung")
      )
      (libsource (lib "eagle-import") (part "100NF-25V-0201"))
    )
    (comp (ref "DAT")
      (value "Blue")
      (footprint "eagle-import:LED-0603")
      (fields
        (field (name "HQ_PART") "PH0093698")
        (field (name "LCSC_PART") "C965807")
        (field (name "MANUFACTURER") "NATIONSTAR")
      )
      (libsource (lib "eagle-import") (part "LED-BLUELED-0603"))
    )
    (comp (ref "IC3")
      (value "ULN2803AFWG")
      (footprint "eagle-import:SO18")
      (fields
        (field (name "HQ_PART") "ZHLM0322921")
        (field (name "LCSC_PART") "C845537")
        (field (name "MANUFACTURER") "UMW")
      )
      (libsource (lib "eagle-import") (part "ULN2803"))
    )
    (comp (ref "IC4")
      (value "MCP23017T-E/ML")
      (footprint "eagle-import:QFN28[6X6]ML")
      (fields
        (field (name "HQ_PART") "IC0080215")
        (field (name "LCSC_PART") "C629439")
        (field (name "MANUFACTURER") "MICROCHIP")
      )
      (libsource (lib "eagle-import") (part "MCP23017-E/ML"))
    )
    (comp (ref "IC9")
      (value "SN74HC151PWR")
      (footprint "eagle-import:TSSOP16")
      (fields
        (field (name "HQ_PART") "IC0244620")
        (field (name "LCSC_PART") "C2653837")
        (field (name "MANUFACTURER") "Texas Instruments")
      )
      (libsource (lib "eagle-import") (part "74AC151"))
    )
    (comp (ref "IC22")
      (value "MCP6001RT-I/OT")
      (footprint "eagle-import:SOT23-5")
      (fields
        (field (name "HQ_PART") "IC0119727")
        (field (name "LCSC_PART") "C154973")
        (field (name "MANUFACTURER") "MICROCHIP")
      )
      (libsource (lib "eagle-import") (part "MCP6001RT"))
    )
    (comp (ref "R17")
      (value "0R 1%")
      (footprint "eagle-import:2512")
      (fields
        (field (name "HQ_PART") "RE0460225")
        (field (name "LCSC_PART") "C25469")
        (field (name "MANUFACTURER") "KOA")
      )
      (libsource (lib "eagle-import") (part "0R2512"))
    )
    (comp (ref "R18")
      (value "0R 1%")
      (footprint "eagle-import:2512")
      (fields
        (field (name "HQ_PART") "RE0460225")
        (field (name "LCSC_PART") "C25469")
        (field (name "MANUFACTURER") "KOA")
      )
      (libsource (lib "eagle-import") (part "0R2512"))
    )
    (comp (ref "R19")
      (value "0R 1%")
      (footprint "eagle-import:2512")
      (fields
        (field (name "HQ_PART") "RE0460225")
        (field (name "LCSC_PART") "C25469")
        (field (name "MANUFACTURER") "KOA")
      )
      (libsource (lib "eagle-import") (part "0R2512"))
    )
    (comp (ref "R20")
      (value "0R 1%")
      (footprint "eagle-import:2512")
      (fields
        (field (name "HQ_PART") "RE0460225")
        (field (name "LCSC_PART") "C25469")
        (field (name "MANUFACTURER") "KOA")
      )
      (libsource (lib "eagle-import") (part "0R2512"))
    )
    (comp (ref "R21")
      (value "0R 1%")
      (footprint "eagle-import:2512")
      (fields
        (field (name "HQ_PART") "RE0460225")
        (field (name "LCSC_PART") "C25469")
        (field (name "MANUFACTURER") "KOA")
      )
      (libsource (lib "eagle-import") (part "0R2512"))
    )
    (comp (ref "R22")
      (value "0R 1%")
      (footprint "eagle-import:2512")
      (fields
        (field (name "HQ_PART") "RE0460225")
        (field (name "LCSC_PART") "C25469")
        (field (name "MANUFACTURER") "KOA")
      )
      (libsource (lib "eagle-import") (part "0R2512"))
    )
    (comp (ref "R23")
      (value "0R 1%")
      (footprint "eagle-import:2512")
      (fields
        (field (name "HQ_PART") "RE0460225")
        (field (name "LCSC_PART") "C25469")
        (field (name "MANUFACTURER") "KOA")
      )
      (libsource (lib "eagle-import") (part "0R2512"))
    )
    (comp (ref "R24")
      (value "0R 1%")
      (footprint "eagle-import:2512")
      (fields
        (field (name "HQ_PART") "RE0460225")
        (field (name "LCSC_PART") "C25469")
        (field (name "MANUFACTURER") "KOA")
      )
      (libsource (lib "eagle-import") (part "0R2512"))
    )
    (comp (ref "R57")
      (value "0R 1%")
      (footprint "eagle-import:0402")
      (fields
        (field (name "HQ_PART") "RE0250181")
        (field (name "LCSC_PART") "C17168")
        (field (name "MANUFACTURER") "YAGEO")
      )
      (libsource (lib "eagle-import") (part "0R0402"))
    )
    (comp (ref "R58")
      (value "DNI")
      (footprint "eagle-import:0402")
      (libsource (lib "eagle-import") (part "R0402"))
    )
    (comp (ref "R91")
      (value "0R 1%")
      (footprint "eagle-import:0402")
      (fields
        (field (name "HQ_PART") "RE0250181")
        (field (name "LCSC_PART") "C17168")
        (field (name "MANUFACTURER") "YAGEO")
      )
      (libsource (lib "eagle-import") (part "0R0402"))
    )
    (comp (ref "R92")
      (value "DNI")
      (footprint "eagle-import:0402")
      (libsource (lib "eagle-import") (part "R0402"))
    )
    (comp (ref "R93")
      (value "10K 1%")
      (footprint "eagle-import:_0603X4-1206")
      (fields
        (field (name "HQ_PART") "RE0094682")
        (field (name "LCSC_PART") "C110924")
        (field (name "MANUFACTURER") "Yageo")
      )
      (libsource (lib "eagle-import") (part "10K-1%_ARRAY0603X4-1206"))
    )
    (comp (ref "R122")
      (value "1K 1%")
      (footprint "eagle-import:0402")
      (fields
        (field (name "HQ_PART") "RE0208724")
        (field (name "LCSC_PART") "C11702")
        (field (name "MANUFACTURER") "FH")
      )
      (libsource (lib "eagle-import") (part "1K-1%0402"))
    )
    (comp (ref "REL0")
      (value "DNI")
      (footprint "eagle-import:TP-ROUND")
      (libsource (lib "eagle-import") (part "TP-ROUND"))
    )
    (comp (ref "REL1")
      (value "DNI")
      (footprint "eagle-import:TP-ROUND")
      (libsource (lib "eagle-import") (part "TP-ROUND"))
    )
    (comp (ref "REL2")
      (value "DNI")
      (footprint "eagle-import:TP-ROUND")
      (libsource (lib "eagle-import") (part "TP-ROUND"))
    )
    (comp (ref "REL3")
      (value "DNI")
      (footprint "eagle-import:TP-ROUND")
      (libsource (lib "eagle-import") (part "TP-ROUND"))
    )
    (comp (ref "REL4")
      (value "DNI")
      (footprint "eagle-import:TP-ROUND")
      (libsource (lib "eagle-import") (part "TP-ROUND"))
    )
    (comp (ref "REL5")
      (value "DNI")
      (footprint "eagle-import:TP-ROUND")
      (libsource (lib "eagle-import") (part "TP-ROUND"))
    )
    (comp (ref "REL6")
      (value "DNI")
      (footprint "eagle-import:TP-ROUND")
      (libsource (lib "eagle-import") (part "TP-ROUND"))
    )
    (comp (ref "REL7")
      (value "DNI")
      (footprint "eagle-import:TP-ROUND")
      (libsource (lib "eagle-import") (part "TP-ROUND"))
    )
    (comp (ref "RN1")
      (value "100K 1%")
      (footprint "eagle-import:_0603X4-1206")
      (fields
        (field (name "HQ_PART") "RE0094681")
        (field (name "LCSC_PART") "C110374")
        (field (name "MANUFACTURER") "Yageo")
      )
      (libsource (lib "eagle-import") (part "100K-1%_ARRAY0603X4-1206"))
    )
    (comp (ref "RN2")
      (value "100K 1%")
      (footprint "eagle-import:_0603X4-1206")
      (fields
        (field (name "HQ_PART") "RE0094681")
        (field (name "LCSC_PART") "C110374")
        (field (name "MANUFACTURER") "Yageo")
      )
      (libsource (lib "eagle-import") (part "100K-1%_ARRAY0603X4-1206"))
    )
    (comp (ref "UTX")
      (value "DNI")
      (footprint "eagle-import:TP-ROUND")
      (libsource (lib "eagle-import") (part "TP-ROUND"))
    )
    (comp (ref "C24")
      (value "33nF 50V")
      (footprint "eagle-import:0805")
      (fields
        (field (name "HQ_PART") "UN0000063")
        (field (name "LCSC_PART") "C107150")
        (field (name "MANUFACTURER") "FH")
      )
      (libsource (lib "eagle-import") (part "33NF-50V0805"))
    )
    (comp (ref "C25")
      (value "33nF 50V")
      (footprint "eagle-import:0805")
      (fields
        (field (name "HQ_PART") "UN0000063")
        (field (name "LCSC_PART") "C107150")
        (field (name "MANUFACTURER") "FH")
      )
      (libsource (lib "eagle-import") (part "33NF-50V0805"))
    )
    (comp (ref "C26")
      (value "33nF 50V")
      (footprint "eagle-import:0805")
      (fields
        (field (name "HQ_PART") "UN0000063")
        (field (name "LCSC_PART") "C107150")
        (field (name "MANUFACTURER") "FH")
      )
      (libsource (lib "eagle-import") (part "33NF-50V0805"))
    )
    (comp (ref "C30")
      (value "33nF 50V")
      (footprint "eagle-import:0805")
      (fields
        (field (name "HQ_PART") "UN0000063")
        (field (name "LCSC_PART") "C107150")
        (field (name "MANUFACTURER") "FH")
      )
      (libsource (lib "eagle-import") (part "33NF-50V0805"))
    )
    (comp (ref "C31")
      (value "33nF 50V")
      (footprint "eagle-import:0805")
      (fields
        (field (name "HQ_PART") "UN0000063")
        (field (name "LCSC_PART") "C107150")
        (field (name "MANUFACTURER") "FH")
      )
      (libsource (lib "eagle-import") (part "33NF-50V0805"))
    )
    (comp (ref "C32")
      (value "33nF 50V")
      (footprint "eagle-import:0805")
      (fields
        (field (name "HQ_PART") "UN0000063")
        (field (name "LCSC_PART") "C107150")
        (field (name "MANUFACTURER") "FH")
      )
      (libsource (lib "eagle-import") (part "33NF-50V0805"))
    )
    (comp (ref "C36")
      (value "33nF 50V")
      (footprint "eagle-import:0805")
      (fields
        (field (name "HQ_PART") "UN0000063")
        (field (name "LCSC_PART") "C107150")
        (field (name "MANUFACTURER") "FH")
      )
      (libsource (lib "eagle-import") (part "33NF-50V0805"))
    )
    (comp (ref "C37")
      (value "33nF 50V")
      (footprint "eagle-import:0805")
      (fields
        (field (name "HQ_PART") "UN0000063")
        (field (name "LCSC_PART") "C107150")
        (field (name "MANUFACTURER") "FH")
      )
      (libsource (lib "eagle-import") (part "33NF-50V0805"))
    )
    (comp (ref "C38")
      (value "33nF 50V")
      (footprint "eagle-import:0805")
      (fields
        (field (name "HQ_PART") "UN0000063")
        (field (name "LCSC_PART") "C107150")
        (field (name "MANUFACTURER") "FH")
      )
      (libsource (lib "eagle-import") (part "33NF-50V0805"))
    )
    (comp (ref "C42")
      (value "33nF 50V")
      (footprint "eagle-import:0805")
      (fields
        (field (name "HQ_PART") "UN0000063")
        (field (name "LCSC_PART") "C107150")
        (field (name "MANUFACTURER") "FH")
      )
      (libsource (lib "eagle-import") (part "33NF-50V0805"))
    )
    (comp (ref "C43")
      (value "33nF 50V")
      (footprint "eagle-import:0805")
      (fields
        (field (name "HQ_PART") "UN0000063")
        (field (name "LCSC_PART") "C107150")
        (field (name "MANUFACTURER") "FH")
      )
      (libsource (lib "eagle-import") (part "33NF-50V0805"))
    )
    (comp (ref "C44")
      (value "33nF 50V")
      (footprint "eagle-import:0805")
      (fields
        (field (name "HQ_PART") "UN0000063")
        (field (name "LCSC_PART") "C107150")
        (field (name "MANUFACTURER") "FH")
      )
      (libsource (lib "eagle-import") (part "33NF-50V0805"))
    )
    (comp (ref "IC6")
      (value "HLW8032")
      (footprint "eagle-import:SO8")
      (fields
        (field (name "HQ_PART") "MD0751024")
        (field (name "LCSC_PART") "C128023")
        (field (name "MANUFACTURER") "Hiliwei Tech")
      )
      (libsource (lib "eagle-import") (part "HLW8032"))
    )
    (comp (ref "IC8")
      (value "HLW8032")
      (footprint "eagle-import:SO8")
      (fields
        (field (name "HQ_PART") "MD0751024")
        (field (name "LCSC_PART") "C128023")
        (field (name "MANUFACTURER") "Hiliwei Tech")
      )
      (libsource (lib "eagle-import") (part "HLW8032"))
    )
    (comp (ref "IC10")
      (value "HLW8032")
      (footprint "eagle-import:SO8")
      (fields
        (field (name "HQ_PART") "MD0751024")
        (field (name "LCSC_PART") "C128023")
        (field (name "MANUFACTURER") "Hiliwei Tech")
      )
      (libsource (lib "eagle-import") (part "HLW8032"))
    )
    (comp (ref "IC12")
      (value "HLW8032")
      (footprint "eagle-import:SO8")
      (fields
        (field (name "HQ_PART") "MD0751024")
        (field (name "LCSC_PART") "C128023")
        (field (name "MANUFACTURER") "Hiliwei Tech")
      )
      (libsource (lib "eagle-import") (part "HLW8032"))
    )
    (comp (ref "L_OUT1")
      (value "FASTON-1217861-1")
      (footprint "eagle-import:1217861-1")
      (fields
        (field (name "LCSC_PART") "C428480")
        (field (name "MANUFACTURER") "TE CONNECTIVITY")
        (field (name "MPN") "1217861-1")
      )
      (libsource (lib "eagle-import") (part "FASTON-1217861-1"))
    )
    (comp (ref "L_OUT2")
      (value "FASTON-1217861-1")
      (footprint "eagle-import:1217861-1")
      (fields
        (field (name "LCSC_PART") "C428480")
        (field (name "MANUFACTURER") "TE CONNECTIVITY")
        (field (name "MPN") "1217861-1")
      )
      (libsource (lib "eagle-import") (part "FASTON-1217861-1"))
    )
    (comp (ref "L_OUT3")
      (value "FASTON-1217861-1")
      (footprint "eagle-import:1217861-1")
      (fields
        (field (name "LCSC_PART") "C428480")
        (field (name "MANUFACTURER") "TE CONNECTIVITY")
        (field (name "MPN") "1217861-1")
      )
      (libsource (lib "eagle-import") (part "FASTON-1217861-1"))
    )
    (comp (ref "L_OUT4")
      (value "FASTON-1217861-1")
      (footprint "eagle-import:1217861-1")
      (fields
        (field (name "LCSC_PART") "C428480")
        (field (name "MANUFACTURER") "TE CONNECTIVITY")
        (field (name "MPN") "1217861-1")
      )
      (libsource (lib "eagle-import") (part "FASTON-1217861-1"))
    )
    (comp (ref "N_OUT1")
      (value "FASTON-1217861-1")
      (footprint "eagle-import:1217861-1")
      (fields
        (field (name "LCSC_PART") "C428480")
        (field (name "MANUFACTURER") "TE CONNECTIVITY")
        (field (name "MPN") "1217861-1")
      )
      (libsource (lib "eagle-import") (part "FASTON-1217861-1"))
    )
    (comp (ref "N_OUT2")
      (value "FASTON-1217861-1")
      (footprint "eagle-import:1217861-1")
      (fields
        (field (name "LCSC_PART") "C428480")
        (field (name "MANUFACTURER") "TE CONNECTIVITY")
        (field (name "MPN") "1217861-1")
      )
      (libsource (lib "eagle-import") (part "FASTON-1217861-1"))
    )
    (comp (ref "N_OUT3")
      (value "FASTON-1217861-1")
      (footprint "eagle-import:1217861-1")
      (fields
        (field (name "LCSC_PART") "C428480")
        (field (name "MANUFACTURER") "TE CONNECTIVITY")
        (field (name "MPN") "1217861-1")
      )
      (libsource (lib "eagle-import") (part "FASTON-1217861-1"))
    )
    (comp (ref "N_OUT4")
      (value "FASTON-1217861-1")
      (footprint "eagle-import:1217861-1")
      (fields
        (field (name "LCSC_PART") "C428480")
        (field (name "MANUFACTURER") "TE CONNECTIVITY")
        (field (name "MPN") "1217861-1")
      )
      (libsource (lib "eagle-import") (part "FASTON-1217861-1"))
    )
    (comp (ref "R25")
      (value "0.002R 1%")
      (footprint "eagle-import:2512")
      (fields
        (field (name "HQ_PART") "RE0716514")
        (field (name "LCSC_PART") "C728320")
        (field (name "MANUFACTURER") "Viking")
      )
      (libsource (lib "eagle-import") (part "0.002R-1%2512"))
    )
    (comp (ref "R30")
      (value "0.002R 1%")
      (footprint "eagle-import:2512")
      (fields
        (field (name "HQ_PART") "RE0716514")
        (field (name "LCSC_PART") "C728320")
        (field (name "MANUFACTURER") "Viking")
      )
      (libsource (lib "eagle-import") (part "0.002R-1%2512"))
    )
    (comp (ref "R31")
      (value "0.002R 1%")
      (footprint "eagle-import:2512")
      (fields
        (field (name "HQ_PART") "RE0716514")
        (field (name "LCSC_PART") "C728320")
        (field (name "MANUFACTURER") "Viking")
      )
      (libsource (lib "eagle-import") (part "0.002R-1%2512"))
    )
    (comp (ref "R32")
      (value "0.002R 1%")
      (footprint "eagle-import:2512")
      (fields
        (field (name "HQ_PART") "RE0716514")
        (field (name "LCSC_PART") "C728320")
        (field (name "MANUFACTURER") "Viking")
      )
      (libsource (lib "eagle-import") (part "0.002R-1%2512"))
    )
    (comp (ref "R33")
      (value "1K 1%")
      (footprint "eagle-import:0805")
      (fields
        (field (name "HQ_PART") "RE0203459")
        (field (name "LCSC_PART") "C17513")
        (field (name "MANUFACTURER") "FH")
      )
      (libsource (lib "eagle-import") (part "1K-1%0805"))
    )
    (comp (ref "R34")
      (value "1K 1%")
      (footprint "eagle-import:0805")
      (fields
        (field (name "HQ_PART") "RE0203459")
        (field (name "LCSC_PART") "C17513")
        (field (name "MANUFACTURER") "FH")
      )
      (libsource (lib "eagle-import") (part "1K-1%0805"))
    )
    (comp (ref "R35")
      (value "0.002R 1%")
      (footprint "eagle-import:2512")
      (fields
        (field (name "HQ_PART") "RE0716514")
        (field (name "LCSC_PART") "C728320")
        (field (name "MANUFACTURER") "Viking")
      )
      (libsource (lib "eagle-import") (part "0.002R-1%2512"))
    )
    (comp (ref "R36")
      (value "470K 1%")
      (footprint "eagle-import:0805")
      (fields
        (field (name "HQ_PART") "RE0205756")
        (field (name "LCSC_PART") "C17709")
        (field (name "MANUFACTURER") "Panasonic")
      )
      (libsource (lib "eagle-import") (part "470K-1%0805"))
    )
    (comp (ref "R37")
      (value "470K 1%")
      (footprint "eagle-import:0805")
      (fields
        (field (name "HQ_PART") "RE0205756")
        (field (name "LCSC_PART") "C17709")
        (field (name "MANUFACTURER") "Panasonic")
      )
      (libsource (lib "eagle-import") (part "470K-1%0805"))
    )
    (comp (ref "R38")
      (value "470K 1%")
      (footprint "eagle-import:0805")
      (fields
        (field (name "HQ_PART") "RE0205756")
        (field (name "LCSC_PART") "C17709")
        (field (name "MANUFACTURER") "Panasonic")
      )
      (libsource (lib "eagle-import") (part "470K-1%0805"))
    )
    (comp (ref "R39")
      (value "470K 1%")
      (footprint "eagle-import:0805")
      (fields
        (field (name "HQ_PART") "RE0205756")
        (field (name "LCSC_PART") "C17709")
        (field (name "MANUFACTURER") "Panasonic")
      )
      (libsource (lib "eagle-import") (part "470K-1%0805"))
    )
    (comp (ref "R40")
      (value "1K 1%")
      (footprint "eagle-import:0805")
      (fields
        (field (name "HQ_PART") "RE0203459")
        (field (name "LCSC_PART") "C17513")
        (field (name "MANUFACTURER") "FH")
      )
      (libsource (lib "eagle-import") (part "1K-1%0805"))
    )
    (comp (ref "R49")
      (value "1K 1%")
      (footprint "eagle-import:0805")
      (fields
        (field (name "HQ_PART") "RE0203459")
        (field (name "LCSC_PART") "C17513")
        (field (name "MANUFACTURER") "FH")
      )
      (libsource (lib "eagle-import") (part "1K-1%0805"))
    )
    (comp (ref "R50")
      (value "1K 1%")
      (footprint "eagle-import:0805")
      (fields
        (field (name "HQ_PART") "RE0203459")
        (field (name "LCSC_PART") "C17513")
        (field (name "MANUFACTURER") "FH")
      )
      (libsource (lib "eagle-import") (part "1K-1%0805"))
    )
    (comp (ref "R51")
      (value "0.002R 1%")
      (footprint "eagle-import:2512")
      (fields
        (field (name "HQ_PART") "RE0716514")
        (field (name "LCSC_PART") "C728320")
        (field (name "MANUFACTURER") "Viking")
      )
      (libsource (lib "eagle-import") (part "0.002R-1%2512"))
    )
    (comp (ref "R52")
      (value "470K 1%")
      (footprint "eagle-import:0805")
      (fields
        (field (name "HQ_PART") "RE0205756")
        (field (name "LCSC_PART") "C17709")
        (field (name "MANUFACTURER") "Panasonic")
      )
      (libsource (lib "eagle-import") (part "470K-1%0805"))
    )
    (comp (ref "R53")
      (value "470K 1%")
      (footprint "eagle-import:0805")
      (fields
        (field (name "HQ_PART") "RE0205756")
        (field (name "LCSC_PART") "C17709")
        (field (name "MANUFACTURER") "Panasonic")
      )
      (libsource (lib "eagle-import") (part "470K-1%0805"))
    )
    (comp (ref "R54")
      (value "470K 1%")
      (footprint "eagle-import:0805")
      (fields
        (field (name "HQ_PART") "RE0205756")
        (field (name "LCSC_PART") "C17709")
        (field (name "MANUFACTURER") "Panasonic")
      )
      (libsource (lib "eagle-import") (part "470K-1%0805"))
    )
    (comp (ref "R55")
      (value "470K 1%")
      (footprint "eagle-import:0805")
      (fields
        (field (name "HQ_PART") "RE0205756")
        (field (name "LCSC_PART") "C17709")
        (field (name "MANUFACTURER") "Panasonic")
      )
      (libsource (lib "eagle-import") (part "470K-1%0805"))
    )
    (comp (ref "R56")
      (value "1K 1%")
      (footprint "eagle-import:0805")
      (fields
        (field (name "HQ_PART") "RE0203459")
        (field (name "LCSC_PART") "C17513")
        (field (name "MANUFACTURER") "FH")
      )
      (libsource (lib "eagle-import") (part "1K-1%0805"))
    )
    (comp (ref "R65")
      (value "1K 1%")
      (footprint "eagle-import:0805")
      (fields
        (field (name "HQ_PART") "RE0203459")
        (field (name "LCSC_PART") "C17513")
        (field (name "MANUFACTURER") "FH")
      )
      (libsource (lib "eagle-import") (part "1K-1%0805"))
    )
    (comp (ref "R66")
      (value "1K 1%")
      (footprint "eagle-import:0805")
      (fields
        (field (name "HQ_PART") "RE0203459")
        (field (name "LCSC_PART") "C17513")
        (field (name "MANUFACTURER") "FH")
      )
      (libsource (lib "eagle-import") (part "1K-1%0805"))
    )
    (comp (ref "R67")
      (value "0.002R 1%")
      (footprint "eagle-import:2512")
      (fields
        (field (name "HQ_PART") "RE0716514")
        (field (name "LCSC_PART") "C728320")
        (field (name "MANUFACTURER") "Viking")
      )
      (libsource (lib "eagle-import") (part "0.002R-1%2512"))
    )
    (comp (ref "R68")
      (value "470K 1%")
      (footprint "eagle-import:0805")
      (fields
        (field (name "HQ_PART") "RE0205756")
        (field (name "LCSC_PART") "C17709")
        (field (name "MANUFACTURER") "Panasonic")
      )
      (libsource (lib "eagle-import") (part "470K-1%0805"))
    )
    (comp (ref "R69")
      (value "470K 1%")
      (footprint "eagle-import:0805")
      (fields
        (field (name "HQ_PART") "RE0205756")
        (field (name "LCSC_PART") "C17709")
        (field (name "MANUFACTURER") "Panasonic")
      )
      (libsource (lib "eagle-import") (part "470K-1%0805"))
    )
    (comp (ref "R70")
      (value "470K 1%")
      (footprint "eagle-import:0805")
      (fields
        (field (name "HQ_PART") "RE0205756")
        (field (name "LCSC_PART") "C17709")
        (field (name "MANUFACTURER") "Panasonic")
      )
      (libsource (lib "eagle-import") (part "470K-1%0805"))
    )
    (comp (ref "R71")
      (value "470K 1%")
      (footprint "eagle-import:0805")
      (fields
        (field (name "HQ_PART") "RE0205756")
        (field (name "LCSC_PART") "C17709")
        (field (name "MANUFACTURER") "Panasonic")
      )
      (libsource (lib "eagle-import") (part "470K-1%0805"))
    )
    (comp (ref "R72")
      (value "1K 1%")
      (footprint "eagle-import:0805")
      (fields
        (field (name "HQ_PART") "RE0203459")
        (field (name "LCSC_PART") "C17513")
        (field (name "MANUFACTURER") "FH")
      )
      (libsource (lib "eagle-import") (part "1K-1%0805"))
    )
    (comp (ref "R81")
      (value "1K 1%")
      (footprint "eagle-import:0805")
      (fields
        (field (name "HQ_PART") "RE0203459")
        (field (name "LCSC_PART") "C17513")
        (field (name "MANUFACTURER") "FH")
      )
      (libsource (lib "eagle-import") (part "1K-1%0805"))
    )
    (comp (ref "R82")
      (value "1K 1%")
      (footprint "eagle-import:0805")
      (fields
        (field (name "HQ_PART") "RE0203459")
        (field (name "LCSC_PART") "C17513")
        (field (name "MANUFACTURER") "FH")
      )
      (libsource (lib "eagle-import") (part "1K-1%0805"))
    )
    (comp (ref "R83")
      (value "0.002R 1%")
      (footprint "eagle-import:2512")
      (fields
        (field (name "HQ_PART") "RE0716514")
        (field (name "LCSC_PART") "C728320")
        (field (name "MANUFACTURER") "Viking")
      )
      (libsource (lib "eagle-import") (part "0.002R-1%2512"))
    )
    (comp (ref "R84")
      (value "470K 1%")
      (footprint "eagle-import:0805")
      (fields
        (field (name "HQ_PART") "RE0205756")
        (field (name "LCSC_PART") "C17709")
        (field (name "MANUFACTURER") "Panasonic")
      )
      (libsource (lib "eagle-import") (part "470K-1%0805"))
    )
    (comp (ref "R85")
      (value "470K 1%")
      (footprint "eagle-import:0805")
      (fields
        (field (name "HQ_PART") "RE0205756")
        (field (name "LCSC_PART") "C17709")
        (field (name "MANUFACTURER") "Panasonic")
      )
      (libsource (lib "eagle-import") (part "470K-1%0805"))
    )
    (comp (ref "R86")
      (value "470K 1%")
      (footprint "eagle-import:0805")
      (fields
        (field (name "HQ_PART") "RE0205756")
        (field (name "LCSC_PART") "C17709")
        (field (name "MANUFACTURER") "Panasonic")
      )
      (libsource (lib "eagle-import") (part "470K-1%0805"))
    )
    (comp (ref "R87")
      (value "470K 1%")
      (footprint "eagle-import:0805")
      (fields
        (field (name "HQ_PART") "RE0205756")
        (field (name "LCSC_PART") "C17709")
        (field (name "MANUFACTURER") "Panasonic")
      )
      (libsource (lib "eagle-import") (part "470K-1%0805"))
    )
    (comp (ref "R88")
      (value "1K 1%")
      (footprint "eagle-import:0805")
      (fields
        (field (name "HQ_PART") "RE0203459")
        (field (name "LCSC_PART") "C17513")
        (field (name "MANUFACTURER") "FH")
      )
      (libsource (lib "eagle-import") (part "1K-1%0805"))
    )
    (comp (ref "ADC_TEMP")
      (value "DNI")
      (footprint "eagle-import:TP-ROUND")
      (libsource (lib "eagle-import") (part "TP-ROUND"))
    )
    (comp (ref "AVDD")
      (value "DNI")
      (footprint "eagle-import:TP-ROUND")
      (libsource (lib "eagle-import") (part "TP-ROUND"))
    )
    (comp (ref "C58")
      (value "15pF 50V")
      (footprint "eagle-import:0201")
      (fields
        (field (name "HQ_PART") "CA0136888")
        (field (name "LCSC_PART") "C22374851")
        (field (name "MANUFACTURER") "Yageo")
      )
      (libsource (lib "eagle-import") (part "15PF-50V0201"))
    )
    (comp (ref "C59")
      (value "15pF 50V")
      (footprint "eagle-import:0201")
      (fields
        (field (name "HQ_PART") "CA0136888")
        (field (name "LCSC_PART") "C22374851")
        (field (name "MANUFACTURER") "Yageo")
      )
      (libsource (lib "eagle-import") (part "15PF-50V0201"))
    )
    (comp (ref "C60")
      (value "1uF 25V")
      (footprint "eagle-import:0402")
      (fields
        (field (name "HQ_PART") "CA0175588")
        (field (name "LCSC_PART") "C52923")
        (field (name "MANUFACTURER") "TDK")
      )
      (libsource (lib "eagle-import") (part "1UF-25V0402"))
    )
    (comp (ref "C61")
      (value "100nF 25V")
      (footprint "eagle-import:0201")
      (fields
        (field (name "HQ_PART") "CA0183221")
        (field (name "LCSC_PART") "C76939")
        (field (name "MANUFACTURER") "Samsung")
      )
      (libsource (lib "eagle-import") (part "100NF-25V-0201"))
    )
    (comp (ref "C62")
      (value "100nF 25V")
      (footprint "eagle-import:0201")
      (fields
        (field (name "HQ_PART") "CA0183221")
        (field (name "LCSC_PART") "C76939")
        (field (name "MANUFACTURER") "Samsung")
      )
      (libsource (lib "eagle-import") (part "100NF-25V-0201"))
    )
    (comp (ref "C63")
      (value "100nF 25V")
      (footprint "eagle-import:0201")
      (fields
        (field (name "HQ_PART") "CA0183221")
        (field (name "LCSC_PART") "C76939")
        (field (name "MANUFACTURER") "Samsung")
      )
      (libsource (lib "eagle-import") (part "100NF-25V-0201"))
    )
    (comp (ref "C64")
      (value "100nF 25V")
      (footprint "eagle-import:0201")
      (fields
        (field (name "HQ_PART") "CA0183221")
        (field (name "LCSC_PART") "C76939")
        (field (name "MANUFACTURER") "Samsung")
      )
      (libsource (lib "eagle-import") (part "100NF-25V-0201"))
    )
    (comp (ref "C102")
      (value "1uF 16V")
      (footprint "eagle-import:0201")
      (fields
        (field (name "HQ_PART") "CA0176810")
        (field (name "LCSC_PART") "C307385")
        (field (name "MANUFACTURER") "WALSIN")
      )
      (libsource (lib "eagle-import") (part "1UF-16V0201"))
    )
    (comp (ref "C104")
      (value "1uF 25V")
      (footprint "eagle-import:0402")
      (fields
        (field (name "HQ_PART") "CA0175588")
        (field (name "LCSC_PART") "C52923")
        (field (name "MANUFACTURER") "TDK")
      )
      (libsource (lib "eagle-import") (part "1UF-25V0402"))
    )
    (comp (ref "C105")
      (value "100nF 25V")
      (footprint "eagle-import:0201")
      (fields
        (field (name "HQ_PART") "CA0183221")
        (field (name "LCSC_PART") "C76939")
        (field (name "MANUFACTURER") "Samsung")
      )
      (libsource (lib "eagle-import") (part "100NF-25V-0201"))
    )
    (comp (ref "DNI")
      (value "0R 1%")
      (footprint "eagle-import:0402")
      (fields
        (field (name "PACKAGE") "0402")
        (field (name "HQ_PART") "RE0250181")
        (field (name "LCSC_PART") "C17168")
        (field (name "MANUFACTURER") "YAGEO")
      )
      (libsource (lib "eagle-import") (part "0R0402"))
    )
    (comp (ref "IC17")
      (value "MCP6001RT-I/OT")
      (footprint "eagle-import:SOT23-5")
      (fields
        (field (name "HQ_PART") "IC0119727")
        (field (name "LCSC_PART") "C154973")
        (field (name "MANUFACTURER") "MICROCHIP")
      )
      (libsource (lib "eagle-import") (part "MCP6001RT"))
    )
    (comp (ref "IC18")
      (value "W25Q128JVPIQ")
      (footprint "eagle-import:SON127P600X500X75-8N")
      (fields
        (field (name "HQ_PART") "IC0150933")
        (field (name "LCSC_PART") "C190862")
        (field (name "MANUFACTURER") "Winbond")
      )
      (libsource (lib "eagle-import") (part "W25Q128JVP"))
    )
    (comp (ref "IC19")
      (value "CAT24C256HU4IGT3")
      (footprint "eagle-import:SON50P300X200X50-9T130X140N")
      (fields
        (field (name "HQ_PART") "IC0066897")
        (field (name "LCSC_PART") "C233771")
        (field (name "MANUFACTURER") "ON")
      )
      (libsource (lib "eagle-import") (part "CAT24C256-HU4"))
    )
    (comp (ref "IC23")
      (value "MCP9700AT-E/LT")
      (footprint "eagle-import:SC70-5")
      (fields (field (name "LCSC_PART") "C97546") (field (name "MANUFACTURER") "Microchip "))
      (libsource (lib "eagle-import") (part "MCP9700AT-E/LT"))
    )
    (comp (ref "MCPVIN")
      (value "DNI")
      (footprint "eagle-import:TP-ROUND")
      (libsource (lib "eagle-import") (part "TP-ROUND"))
    )
    (comp (ref "R16")
      (value "1K 1%")
      (footprint "eagle-import:0201")
      (fields
        (field (name "HQ_PART") "RE0015967")
        (field (name "LCSC_PART") "C270365")
        (field (name "MANUFACTURER") "Yageo")
      )
      (libsource (lib "eagle-import") (part "1K-1%0201"))
    )
    (comp (ref "R109")
      (value "4.7K 1%")
      (footprint "eagle-import:0201")
      (fields
        (field (name "HQ_PART") "RE0208670")
        (field (name "LCSC_PART") "C270346")
        (field (name "MANUFACTURER") "RALEC")
      )
      (libsource (lib "eagle-import") (part "4.7K-1%0201"))
    )
    (comp (ref "R111")
      (value "DNI")
      (footprint "eagle-import:R0201")
      (libsource (lib "eagle-import") (part "R0201"))
    )
    (comp (ref "R112")
      (value "1K 1%")
      (footprint "eagle-import:0402")
      (fields
        (field (name "HQ_PART") "RE0208724")
        (field (name "LCSC_PART") "C11702")
        (field (name "MANUFACTURER") "FH")
      )
      (libsource (lib "eagle-import") (part "1K-1%0402"))
    )
    (comp (ref "R128")
      (value "DNI")
      (footprint "eagle-import:R0201")
      (libsource (lib "eagle-import") (part "R0201"))
    )
    (comp (ref "R129")
      (value "4.7K 1%")
      (footprint "eagle-import:0201")
      (fields
        (field (name "HQ_PART") "RE0208670")
        (field (name "LCSC_PART") "C270346")
        (field (name "MANUFACTURER") "RALEC")
      )
      (libsource (lib "eagle-import") (part "4.7K-1%0201"))
    )
    (comp (ref "R152")
      (value "10R 1%")
      (footprint "eagle-import:0201")
      (fields
        (field (name "HQ_PART") "RE0210247")
        (field (name "LCSC_PART") "C270817")
        (field (name "MANUFACTURER") "Yageo")
      )
      (libsource (lib "eagle-import") (part "10R-1%0201"))
    )
    (comp (ref "REF1")
      (value "LM4040x30")
      (footprint "eagle-import:SOT23")
      (fields
        (field (name "HQ_PART") "IC0022950")
        (field (name "LCSC_PART") "C460604")
        (field (name "MANUFACTURER") "DIODES")
      )
      (libsource (lib "eagle-import") (part "LM4040BXX"))
    )
    (comp (ref "VREF")
      (value "DNI")
      (footprint "eagle-import:TP-ROUND")
      (libsource (lib "eagle-import") (part "TP-ROUND"))
    )
    (comp (ref "X1")
      (value "12MHz")
      (footprint "eagle-import:WE-XTAL_CFPX-180")
      (fields
        (field (name "HQ_PART") "CR0250194")
        (field (name "LCSC_PART") "C20625731")
        (field (name "MANUFACTURER") "TKD")
      )
      (libsource (lib "eagle-import") (part "CRYSTAL-3225X322512MSB4SI"))
    )
  )
  (nets
    (net (code "1") (name "+1V1") (class "Default")
      (node (ref "C75") (pin "1") (pinfunction "1_1") (pintype "passive"))
      (node (ref "C76") (pin "1") (pinfunction "1_1") (pintype "passive"))
      (node (ref "C77") (pin "1") (pinfunction "1_1") (pintype "passive"))
      (node (ref "DVDD") (pin "TP") (pinfunction "P$1_TP") (pintype "bidirectional"))
      (node (ref "IC15") (pin "23") (pinfunction "DVDD_23") (pintype "bidirectional"))
      (node (ref "IC15") (pin "45") (pinfunction "VREG_VOUT_45") (pintype "bidirectional"))
      (node (ref "IC15") (pin "50") (pinfunction "DVDD_50") (pintype "bidirectional"))
    )
    (net (code "2") (name "+3V3") (class "Default")
      (node (ref "3VDC") (pin "TP") (pinfunction "P$1_TP") (pintype "bidirectional"))
      (node (ref "C103") (pin "1") (pinfunction "1_1") (pintype "passive"))
      (node (ref "C105") (pin "1") (pinfunction "1_1") (pintype "passive"))
      (node (ref "C12") (pin "1") (pinfunction "1_1") (pintype "passive"))
      (node (ref "C15") (pin "1") (pinfunction "1_1") (pintype "passive"))
      (node (ref "C18") (pin "1") (pinfunction "1_1") (pintype "passive"))
      (node (ref "C19") (pin "1") (pinfunction "1_1") (pintype "passive"))
      (node (ref "C20") (pin "1") (pinfunction "1_1") (pintype "passive"))
      (node (ref "C33") (pin "1") (pinfunction "1_1") (pintype "passive"))
      (node (ref "C34") (pin "1") (pinfunction "1_1") (pintype "passive"))
      (node (ref "C88") (pin "1") (pinfunction "1_1") (pintype "passive"))
      (node (ref "C89") (pin "1") (pinfunction "1_1") (pintype "passive"))
      (node (ref "C90") (pin "1") (pinfunction "1_1") (pintype "passive"))
      (node (ref "DSP") (pin "1") (pinfunction "1_1") (pintype "bidirectional"))
      (node (ref "DSP") (pin "2") (pinfunction "2_2") (pintype "bidirectional"))
      (node (ref "ETH1") (pin "10") (pinfunction "GREEN+_10") (pintype "passive"))
      (node (ref "ETH1") (pin "12") (pinfunction "YELLOW+_12") (pintype "passive"))
      (node (ref "IC20") (pin "28") (pinfunction "VDD_28") (pintype "power_in"))
      (node (ref "IC20") (pin "43") (pinfunction "PMODE2_43") (pintype "input"))
      (node (ref "IC20") (pin "44") (pinfunction "PMODE1_44") (pintype "input"))
      (node (ref "IC20") (pin "45") (pinfunction "PMODE0_45") (pintype "input"))
      (node (ref "IC22") (pin "2") (pinfunction "V+_2") (pintype "power_in"))
      (node (ref "IC23") (pin "4") (pinfunction "VDD_4") (pintype "power_in"))
      (node (ref "IC4") (pin "5") (pinfunction "VDD_5") (pintype "bidirectional"))
      (node (ref "IC9") (pin "16") (pinfunction "VCC_16") (pintype "power_in"))
      (node (ref "L2") (pin "2") (pinfunction "2_2") (pintype "passive"))
      (node (ref "L4") (pin "1") (pinfunction "1_1") (pintype "passive"))
      (node (ref "R123") (pin "1") (pinfunction "1_1") (pintype "passive"))
      (node (ref "R13") (pin "1") (pinfunction "1_1") (pintype "passive"))
      (node (ref "R145") (pin "2") (pinfunction "2_2") (pintype "passive"))
      (node (ref "R147") (pin "2") (pinfunction "2_2") (pintype "passive"))
      (node (ref "R149") (pin "A1") (pinfunction "1_A1") (pintype "passive"))
      (node (ref "R149") (pin "B1") (pinfunction "2_B1") (pintype "passive"))
      (node (ref "R149") (pin "C1") (pinfunction "3_C1") (pintype "passive"))
      (node (ref "R149") (pin "D1") (pinfunction "4_D1") (pintype "passive"))
      (node (ref "R169") (pin "1") (pinfunction "1_1") (pintype "passive"))
      (node (ref "R89") (pin "A2") (pinfunction "8_A2") (pintype "passive"))
      (node (ref "R89") (pin "B2") (pinfunction "7_B2") (pintype "passive"))
      (node (ref "R89") (pin "C2") (pinfunction "6_C2") (pintype "passive"))
      (node (ref "R89") (pin "D2") (pinfunction "5_D2") (pintype "passive"))
      (node (ref "R90") (pin "A2") (pinfunction "8_A2") (pintype "passive"))
      (node (ref "R90") (pin "B2") (pinfunction "7_B2") (pintype "passive"))
      (node (ref "R90") (pin "C2") (pinfunction "6_C2") (pintype "passive"))
      (node (ref "R90") (pin "D2") (pinfunction "5_D2") (pintype "passive"))
    )
    (net (code "3") (name "+3V3_A") (class "Default")
      (node (ref "3V3A") (pin "TP") (pinfunction "P$1_TP") (pintype "bidirectional"))
      (node (ref "C91") (pin "1") (pinfunction "1_1") (pintype "passive"))
      (node (ref "C92") (pin "1") (pinfunction "1_1") (pintype "passive"))
      (node (ref "C93") (pin "1") (pinfunction "1_1") (pintype "passive"))
      (node (ref "C94") (pin "1") (pinfunction "1_1") (pintype "passive"))
      (node (ref "C95") (pin "1") (pinfunction "1_1") (pintype "passive"))
      (node (ref "C96") (pin "1") (pinfunction "1_1") (pintype "passive"))
      (node (ref "IC20") (pin "11") (pinfunction "AVDD_11") (pintype "power_in"))
      (node (ref "IC20") (pin "15") (pinfunction "AVDD_15") (pintype "power_in"))
      (node (ref "IC20") (pin "17") (pinfunction "AVDD_17") (pintype "power_in"))
      (node (ref "IC20") (pin "21") (pinfunction "AVDD_21") (pintype "power_in"))
      (node (ref "IC20") (pin "4") (pinfunction "AVDD_4") (pintype "power_in"))
      (node (ref "IC20") (pin "8") (pinfunction "AVDD_8") (pintype "power_in"))
      (node (ref "L4") (pin "2") (pinfunction "2_2") (pintype "passive"))
      (node (ref "R139") (pin "2") (pinfunction "2_2") (pintype "passive"))
      (node (ref "R140") (pin "2") (pinfunction "2_2") (pintype "passive"))
      (node (ref "R146") (pin "2") (pinfunction "2_2") (pintype "passive"))
    )
    (net (code "4") (name "+3V3_MCU") (class "Default")
      (node (ref "C100") (pin "1") (pinfunction "1_1") (pintype "passive"))
      (node (ref "C101") (pin "1") (pinfunction "1_1") (pintype "passive"))
      (node (ref "C104") (pin "1") (pinfunction "1_1") (pintype "passive"))
      (node (ref "C64") (pin "1") (pinfunction "1_1") (pintype "passive"))
      (node (ref "C67") (pin "1") (pinfunction "1_1") (pintype "passive"))
      (node (ref "C68") (pin "1") (pinfunction "1_1") (pintype "passive"))
      (node (ref "C69") (pin "1") (pinfunction "1_1") (pintype "passive"))
      (node (ref "C70") (pin "1") (pinfunction "1_1") (pintype "passive"))
      (node (ref "C71") (pin "1") (pinfunction "1_1") (pintype "passive"))
      (node (ref "C72") (pin "1") (pinfunction "1_1") (pintype "passive"))
      (node (ref "C73") (pin "1") (pinfunction "1_1") (pintype "passive"))
      (node (ref "C99") (pin "1") (pinfunction "1_1") (pintype "passive"))
      (node (ref "IC15") (pin "1") (pinfunction "IOVDD_1") (pintype "bidirectional"))
      (node (ref "IC15") (pin "10") (pinfunction "IOVDD_10") (pintype "bidirectional"))
      (node (ref "IC15") (pin "22") (pinfunction "IOVDD_22") (pintype "bidirectional"))
      (node (ref "IC15") (pin "33") (pinfunction "IOVDD_33") (pintype "bidirectional"))
      (node (ref "IC15") (pin "42") (pinfunction "IOVDD_42") (pintype "bidirectional"))
      (node (ref "IC15") (pin "44") (pinfunction "VREG_VIN_44") (pintype "bidirectional"))
      (node (ref "IC15") (pin "48") (pinfunction "USB_VDD_48") (pintype "bidirectional"))
      (node (ref "IC15") (pin "49") (pinfunction "IOVDD_49") (pintype "bidirectional"))
      (node (ref "IC18") (pin "8") (pinfunction "VCC_8") (pintype "power_in"))
      (node (ref "IC19") (pin "8") (pinfunction "VCC_8") (pintype "power_in"))
      (node (ref "IC21") (pin "5") (pinfunction "VOUT_5") (pintype "bidirectional"))
      (node (ref "IOVDD") (pin "TP") (pinfunction "P$1_TP") (pintype "bidirectional"))
      (node (ref "PWR") (pin "A") (pinfunction "A_A") (pintype "passive"))
      (node (ref "R109") (pin "2") (pinfunction "2_2") (pintype "passive"))
      (node (ref "R111") (pin "2") (pinfunction "2_2") (pintype "passive"))
      (node (ref "R128") (pin "2") (pinfunction "2_2") (pintype "passive"))
      (node (ref "R130") (pin "1") (pinfunction "1_1") (pintype "passive"))
      (node (ref "R132") (pin "1") (pinfunction "1_1") (pintype "passive"))
      (node (ref "R152") (pin "1") (pinfunction "1_1") (pintype "passive"))
      (node (ref "R165") (pin "2") (pinfunction "2_2") (pintype "passive"))
      (node (ref "R166") (pin "1") (pinfunction "1_1") (pintype "passive"))
      (node (ref "R167") (pin "1") (pinfunction "1_1") (pintype "passive"))
      (node (ref "R168") (pin "1") (pinfunction "1_1") (pintype "passive"))
      (node (ref "R169") (pin "2") (pinfunction "2_2") (pintype "passive"))
    )
    (net (code "5") (name "+5V") (class "Default")
      (node (ref "5VDC") (pin "TP") (pinfunction "P$1_TP") (pintype "bidirectional"))
      (node (ref "C11") (pin "1") (pinfunction "1_1") (pintype "passive"))
      (node (ref "C14") (pin "1") (pinfunction "1_1") (pintype "passive"))
      (node (ref "C17") (pin "1") (pinfunction "1_1") (pintype "passive"))
      (node (ref "D15") (pin "A") (pinfunction "A_A") (pintype "passive"))
      (node (ref "DSP") (pin "3") (pinfunction "3_3") (pintype "bidirectional"))
      (node (ref "DSP") (pin "4") (pinfunction "4_4") (pintype "bidirectional"))
      (node (ref "L1") (pin "2") (pinfunction "2_2") (pintype "passive"))
      (node (ref "R11") (pin "1") (pinfunction "1_1") (pintype "passive"))
      (node (ref "R148") (pin "1") (pinfunction "1_1") (pintype "passive"))
    )
    (net (code "6") (name "+5V_MEA") (class "Default")
      (node (ref "IC10") (pin "1") (pinfunction "VDD_1") (pintype "power_in"))
      (node (ref "IC11") (pin "1") (pinfunction "VDD_1") (pintype "power_in"))
      (node (ref "IC12") (pin "1") (pinfunction "VDD_1") (pintype "power_in"))
      (node (ref "IC14") (pin "1") (pinfunction "VDD_1") (pintype "power_in"))
      (node (ref "IC16") (pin "1") (pinfunction "VDD_1") (pintype "power_in"))
      (node (ref "IC6") (pin "1") (pinfunction "VDD_1") (pintype "power_in"))
      (node (ref "IC7") (pin "1") (pinfunction "VDD_1") (pintype "power_in"))
      (node (ref "IC8") (pin "1") (pinfunction "VDD_1") (pintype "power_in"))
      (node (ref "J2") (pin "2") (pinfunction "2_2") (pintype "passive"))
      (node (ref "J7") (pin "2") (pinfunction "2_2") (pintype "passive"))
      (node (ref "R63") (pin "A1") (pinfunction "1_A1") (pintype "passive"))
      (node (ref "R63") (pin "B1") (pinfunction "2_B1") (pintype "passive"))
      (node (ref "R63") (pin "C1") (pinfunction "3_C1") (pintype "passive"))
      (node (ref "R63") (pin "D1") (pinfunction "4_D1") (pintype "passive"))
      (node (ref "R64") (pin "A1") (pinfunction "1_A1") (pintype "passive"))
      (node (ref "R64") (pin "B1") (pinfunction "2_B1") (pintype "passive"))
      (node (ref "R64") (pin "C1") (pinfunction "3_C1") (pintype "passive"))
      (node (ref "R64") (pin "D1") (pinfunction "4_D1") (pintype "passive"))
    )
    (net (code "7") (name "+5V_MEA1") (class "Default")
      (node (ref "5V-NI1") (pin "TP") (pinfunction "P$1_TP") (pintype "bidirectional"))
      (node (ref "C23") (pin "1") (pinfunction "+_1") (pintype "passive"))
      (node (ref "C45") (pin "2") (pinfunction "2_2") (pintype "passive"))
      (node (ref "D9") (pin "A") (pinfunction "A_A") (pintype "passive"))
      (node (ref "J2") (pin "1") (pinfunction "1_1") (pintype "passive"))
      (node (ref "L3") (pin "2") (pinfunction "2_2") (pintype "passive"))
      (node (ref "R96") (pin "1") (pinfunction "1_1") (pintype "passive"))
    )
    (net (code "8") (name "+5V_MEA2") (class "Default")
      (node (ref "5V-NI2") (pin "TP") (pinfunction "P$1_TP") (pintype "bidirectional"))
      (node (ref "C53") (pin "1") (pinfunction "+_1") (pintype "passive"))
      (node (ref "C57") (pin "2") (pinfunction "2_2") (pintype "passive"))
      (node (ref "D13") (pin "A") (pinfunction "A_A") (pintype "passive"))
      (node (ref "J7") (pin "1") (pinfunction "1_1") (pintype "passive"))
      (node (ref "L5") (pin "2") (pinfunction "2_2") (pintype "passive"))
      (node (ref "R108") (pin "1") (pinfunction "1_1") (pintype "passive"))
    )
    (net (code "9") (name "+12V") (class "Default")
      (node (ref "C1") (pin "1") (pinfunction "1_1") (pintype "passive"))
      (node (ref "C2") (pin "1") (pinfunction "1_1") (pintype "passive"))
      (node (ref "C3") (pin "1") (pinfunction "1_1") (pintype "passive"))
      (node (ref "C4") (pin "1") (pinfunction "1_1") (pintype "passive"))
      (node (ref "D1") (pin "C") (pinfunction "C_C") (pintype "passive"))
      (node (ref "D2") (pin "C") (pinfunction "C_C") (pintype "passive"))
      (node (ref "D3") (pin "C") (pinfunction "C_C") (pintype "passive"))
      (node (ref "D4") (pin "C") (pinfunction "C_C") (pintype "passive"))
      (node (ref "D5") (pin "C") (pinfunction "C_C") (pintype "passive"))
      (node (ref "D6") (pin "C") (pinfunction "C_C") (pintype "passive"))
      (node (ref "D7") (pin "C") (pinfunction "C_C") (pintype "passive"))
      (node (ref "D8") (pin "C") (pinfunction "C_C") (pintype "passive"))
      (node (ref "FAN") (pin "2") (pinfunction "2_2") (pintype "passive"))
      (node (ref "IC1") (pin "2") (pinfunction "IN_2") (pintype "bidirectional"))
      (node (ref "IC2") (pin "2") (pinfunction "IN_2") (pintype "bidirectional"))
      (node (ref "IC3") (pin "10") (pinfunction "COM_10") (pintype "bidirectional"))
      (node (ref "J10") (pin "1") (pinfunction "1_1") (pintype "passive"))
      (node (ref "J8") (pin "1") (pinfunction "1_1") (pintype "passive"))
      (node (ref "J9") (pin "1") (pinfunction "1_1") (pintype "passive"))
      (node (ref "K1") (pin "8") (pinfunction "8_8") (pintype "passive"))
      (node (ref "K2") (pin "8") (pinfunction "8_8") (pintype "passive"))
      (node (ref "K3") (pin "8") (pinfunction "8_8") (pintype "passive"))
      (node (ref "K4") (pin "8") (pinfunction "8_8") (pintype "passive"))
      (node (ref "K5") (pin "8") (pinfunction "8_8") (pintype "passive"))
      (node (ref "K6") (pin "8") (pinfunction "8_8") (pintype "passive"))
      (node (ref "K7") (pin "8") (pinfunction "8_8") (pintype "passive"))
      (node (ref "K8") (pin "8") (pinfunction "8_8") (pintype "passive"))
      (node (ref "R150") (pin "1") (pinfunction "1_1") (pintype "passive"))
      (node (ref "R162") (pin "2") (pinfunction "2_2") (pintype "passive"))
      (node (ref "R171") (pin "2") (pinfunction "2_2") (pintype "passive"))
      (node (ref "R94") (pin "2") (pinfunction "2_2") (pintype "passive"))
    )
    (net (code "10") (name "+12V_MEA") (class "Default")
      (node (ref "ADC12") (pin "TP") (pinfunction "P$1_TP") (pintype "bidirectional"))
      (node (ref "IC15") (pin "41") (pinfunction "GPIO29/ADC3_41") (pintype "bidirectional"))
      (node (ref "R94") (pin "1") (pinfunction "1_1") (pintype "passive"))
      (node (ref "R95") (pin "2") (pinfunction "2_2") (pintype "passive"))
    )
    (net (code "11") (name "5V_EN") (class "Default")
      (node (ref "IC1") (pin "6") (pinfunction "EN_6") (pintype "bidirectional"))
      (node (ref "R1") (pin "1") (pinfunction "1_1") (pintype "passive"))
      (node (ref "R161") (pin "2") (pinfunction "2_2") (pintype "passive"))
      (node (ref "R162") (pin "1") (pinfunction "1_1") (pintype "passive"))
    )
    (net (code "12") (name "AC_L") (class "Default")
      (node (ref "AC/DC1") (pin "AC_L") (pinfunction "AC/L_AC_L") (pintype "input"))
      (node (ref "AC/DC2") (pin "AC/L") (pinfunction "AC/L_AC/L") (pintype "input"))
      (node (ref "AC_L") (pin "1") (pinfunction "MOUNT_1") (pintype "passive"))
      (node (ref "AC_L") (pin "2") (pinfunction "MOUNT_2") (pintype "passive"))
      (node (ref "K1") (pin "3") (pinfunction "3_3") (pintype "passive"))
      (node (ref "K1") (pin "6") (pinfunction "6_6") (pintype "passive"))
      (node (ref "K2") (pin "3") (pinfunction "3_3") (pintype "passive"))
      (node (ref "K2") (pin "6") (pinfunction "6_6") (pintype "passive"))
      (node (ref "K3") (pin "3") (pinfunction "3_3") (pintype "passive"))
      (node (ref "K3") (pin "6") (pinfunction "6_6") (pintype "passive"))
      (node (ref "K4") (pin "3") (pinfunction "3_3") (pintype "passive"))
      (node (ref "K4") (pin "6") (pinfunction "6_6") (pintype "passive"))
      (node (ref "K5") (pin "3") (pinfunction "3_3") (pintype "passive"))
      (node (ref "K5") (pin "6") (pinfunction "6_6") (pintype "passive"))
      (node (ref "K6") (pin "3") (pinfunction "3_3") (pintype "passive"))
      (node (ref "K6") (pin "6") (pinfunction "6_6") (pintype "passive"))
      (node (ref "K7") (pin "3") (pinfunction "3_3") (pintype "passive"))
      (node (ref "K7") (pin "6") (pinfunction "6_6") (pintype "passive"))
      (node (ref "K8") (pin "3") (pinfunction "3_3") (pintype "passive"))
      (node (ref "K8") (pin "6") (pinfunction "6_6") (pintype "passive"))
      (node (ref "R106") (pin "1") (pinfunction "1_1") (pintype "passive"))
      (node (ref "R62") (pin "1") (pinfunction "1_1") (pintype "passive"))
    )
    (net (code "13") (name "ADC_TEMP") (class "Default")
      (node (ref "ADC_TEMP") (pin "TP") (pinfunction "P$1_TP") (pintype "bidirectional"))
      (node (ref "IC15") (pin "39") (pinfunction "GPIO27/ADC1_39") (pintype "bidirectional"))
      (node (ref "IC23") (pin "3") (pinfunction "VOUT_3") (pintype "output"))
    )
    (net (code "14") (name "ADC_V_USB") (class "Default")
      (node (ref "ADCUSB") (pin "TP") (pinfunction "P$1_TP") (pintype "bidirectional"))
      (node (ref "IC15") (pin "38") (pinfunction "GPIO26/ADC0_38") (pintype "bidirectional"))
      (node (ref "R126") (pin "2") (pinfunction "2_2") (pintype "passive"))
      (node (ref "R127") (pin "1") (pinfunction "1_1") (pintype "passive"))
    )
    (net (code "15") (name "AGND") (class "Default")
      (node (ref "AC/DC1") (pin "AC_N") (pinfunction "AC/N_AC_N") (pintype "input"))
      (node (ref "AC/DC2") (pin "AC/N") (pinfunction "AC/N_AC/N") (pintype "input"))
      (node (ref "AC_N") (pin "1") (pinfunction "MOUNT_1") (pintype "passive"))
      (node (ref "AC_N") (pin "2") (pinfunction "MOUNT_2") (pintype "passive"))
      (node (ref "C106") (pin "2") (pinfunction "2_2") (pintype "passive"))
      (node (ref "C107") (pin "2") (pinfunction "2_2") (pintype "passive"))
      (node (ref "C108") (pin "2") (pinfunction "2_2") (pintype "passive"))
      (node (ref "C109") (pin "2") (pinfunction "2_2") (pintype "passive"))
      (node (ref "C110") (pin "2") (pinfunction "2_2") (pintype "passive"))
      (node (ref "C111") (pin "2") (pinfunction "2_2") (pintype "passive"))
      (node (ref "C112") (pin "2") (pinfunction "2_2") (pintype "passive"))
      (node (ref "C113") (pin "2") (pinfunction "2_2") (pintype "passive"))
      (node (ref "C23") (pin "2") (pinfunction "-_2") (pintype "passive"))
      (node (ref "C24") (pin "2") (pinfunction "2_2") (pintype "passive"))
      (node (ref "C25") (pin "2") (pinfunction "2_2") (pintype "passive"))
      (node (ref "C26") (pin "2") (pinfunction "2_2") (pintype "passive"))
      (node (ref "C27") (pin "2") (pinfunction "2_2") (pintype "passive"))
      (node (ref "C28") (pin "2") (pinfunction "2_2") (pintype "passive"))
      (node (ref "C29") (pin "2") (pinfunction "2_2") (pintype "passive"))
      (node (ref "C30") (pin "2") (pinfunction "2_2") (pintype "passive"))
      (node (ref "C31") (pin "2") (pinfunction "2_2") (pintype "passive"))
      (node (ref "C32") (pin "2") (pinfunction "2_2") (pintype "passive"))
      (node (ref "C35") (pin "2") (pinfunction "-_2") (pintype "passive"))
      (node (ref "C36") (pin "2") (pinfunction "2_2") (pintype "passive"))
      (node (ref "C37") (pin "2") (pinfunction "2_2") (pintype "passive"))
      (node (ref "C38") (pin "2") (pinfunction "2_2") (pintype "passive"))
      (node (ref "C39") (pin "2") (pinfunction "2_2") (pintype "passive"))
      (node (ref "C40") (pin "2") (pinfunction "2_2") (pintype "passive"))
      (node (ref "C41") (pin "2") (pinfunction "2_2") (pintype "passive"))
      (node (ref "C42") (pin "2") (pinfunction "2_2") (pintype "passive"))
      (node (ref "C43") (pin "2") (pinfunction "2_2") (pintype "passive"))
      (node (ref "C44") (pin "2") (pinfunction "2_2") (pintype "passive"))
      (node (ref "C45") (pin "1") (pinfunction "1_1") (pintype "passive"))
      (node (ref "C47") (pin "2") (pinfunction "-_2") (pintype "passive"))
      (node (ref "C48") (pin "2") (pinfunction "2_2") (pintype "passive"))
      (node (ref "C49") (pin "2") (pinfunction "2_2") (pintype "passive"))
      (node (ref "C50") (pin "2") (pinfunction "2_2") (pintype "passive"))
      (node (ref "C53") (pin "2") (pinfunction "-_2") (pintype "passive"))
      (node (ref "C54") (pin "2") (pinfunction "2_2") (pintype "passive"))
      (node (ref "C55") (pin "2") (pinfunction "2_2") (pintype "passive"))
      (node (ref "C56") (pin "2") (pinfunction "2_2") (pintype "passive"))
      (node (ref "C57") (pin "1") (pinfunction "1_1") (pintype "passive"))
      (node (ref "D11") (pin "A") (pinfunction "A_A") (pintype "passive"))
      (node (ref "D14") (pin "A") (pinfunction "A_A") (pintype "passive"))
      (node (ref "IC10") (pin "5") (pinfunction "GND_5") (pintype "power_in"))
      (node (ref "IC11") (pin "5") (pinfunction "GND_5") (pintype "power_in"))
      (node (ref "IC12") (pin "5") (pinfunction "GND_5") (pintype "power_in"))
      (node (ref "IC14") (pin "5") (pinfunction "GND_5") (pintype "power_in"))
      (node (ref "IC16") (pin "5") (pinfunction "GND_5") (pintype "power_in"))
      (node (ref "IC6") (pin "5") (pinfunction "GND_5") (pintype "power_in"))
      (node (ref "IC7") (pin "5") (pinfunction "GND_5") (pintype "power_in"))
      (node (ref "IC8") (pin "5") (pinfunction "GND_5") (pintype "power_in"))
      (node (ref "R104") (pin "2") (pinfunction "2_2") (pintype "passive"))
      (node (ref "R108") (pin "2") (pinfunction "2_2") (pintype "passive"))
      (node (ref "R113") (pin "1") (pinfunction "1_1") (pintype "passive"))
      (node (ref "R115") (pin "2") (pinfunction "2_2") (pintype "passive"))
      (node (ref "R120") (pin "2") (pinfunction "2_2") (pintype "passive"))
      (node (ref "R25") (pin "2") (pinfunction "2_2") (pintype "passive"))
      (node (ref "R26") (pin "2") (pinfunction "2_2") (pintype "passive"))
      (node (ref "R27") (pin "2") (pinfunction "2_2") (pintype "passive"))
      (node (ref "R28") (pin "2") (pinfunction "2_2") (pintype "passive"))
      (node (ref "R29") (pin "2") (pinfunction "2_2") (pintype "passive"))
      (node (ref "R30") (pin "2") (pinfunction "2_2") (pintype "passive"))
      (node (ref "R31") (pin "2") (pinfunction "2_2") (pintype "passive"))
      (node (ref "R32") (pin "2") (pinfunction "2_2") (pintype "passive"))
      (node (ref "R33") (pin "1") (pinfunction "1_1") (pintype "passive"))
      (node (ref "R35") (pin "2") (pinfunction "2_2") (pintype "passive"))
      (node (ref "R40") (pin "2") (pinfunction "2_2") (pintype "passive"))
      (node (ref "R41") (pin "1") (pinfunction "1_1") (pintype "passive"))
      (node (ref "R43") (pin "2") (pinfunction "2_2") (pintype "passive"))
      (node (ref "R48") (pin "2") (pinfunction "2_2") (pintype "passive"))
      (node (ref "R49") (pin "1") (pinfunction "1_1") (pintype "passive"))
      (node (ref "R51") (pin "2") (pinfunction "2_2") (pintype "passive"))
      (node (ref "R56") (pin "2") (pinfunction "2_2") (pintype "passive"))
      (node (ref "R65") (pin "1") (pinfunction "1_1") (pintype "passive"))
      (node (ref "R67") (pin "2") (pinfunction "2_2") (pintype "passive"))
      (node (ref "R72") (pin "2") (pinfunction "2_2") (pintype "passive"))
      (node (ref "R73") (pin "1") (pinfunction "1_1") (pintype "passive"))
      (node (ref "R75") (pin "2") (pinfunction "2_2") (pintype "passive"))
      (node (ref "R80") (pin "2") (pinfunction "2_2") (pintype "passive"))
      (node (ref "R81") (pin "1") (pinfunction "1_1") (pintype "passive"))
      (node (ref "R83") (pin "2") (pinfunction "2_2") (pintype "passive"))
      (node (ref "R88") (pin "2") (pinfunction "2_2") (pintype "passive"))
      (node (ref "R96") (pin "2") (pinfunction "2_2") (pintype "passive"))
      (node (ref "R97") (pin "1") (pinfunction "1_1") (pintype "passive"))
      (node (ref "R99") (pin "2") (pinfunction "2_2") (pintype "passive"))
    )
    (net (code "16") (name "AVDD") (class "Default")
      (node (ref "AVDD") (pin "TP") (pinfunction "P$1_TP") (pintype "bidirectional"))
      (node (ref "C62") (pin "1") (pinfunction "1_1") (pintype "passive"))
      (node (ref "C74") (pin "1") (pinfunction "1_1") (pintype "passive"))
      (node (ref "DNI") (pin "1") (pinfunction "1_1") (pintype "passive"))
      (node (ref "IC15") (pin "43") (pinfunction "ADC_AVDD_43") (pintype "bidirectional"))
      (node (ref "IC17") (pin "1") (pinfunction "OUT_1") (pintype "output"))
      (node (ref "IC17") (pin "4") (pinfunction "-IN_4") (pintype "input"))
    )
    (net (code "17") (name "BUCK_EN") (class "Default")
      (node (ref "IC15") (pin "37") (pinfunction "GPIO25_37") (pintype "bidirectional"))
      (node (ref "R1") (pin "2") (pinfunction "2_2") (pintype "passive"))
      (node (ref "R172") (pin "2") (pinfunction "2_2") (pintype "passive"))
    )
    (net (code "18") (name "CC1") (class "Default")
      (node (ref "R125") (pin "1") (pinfunction "1_1") (pintype "passive"))
      (node (ref "USB1") (pin "A5") (pinfunction "CC1_A5") (pintype "bidirectional"))
    )
    (net (code "19") (name "CC2") (class "Default")
      (node (ref "R124") (pin "1") (pinfunction "1_1") (pintype "passive"))
      (node (ref "USB1") (pin "B5") (pinfunction "CC2_B5") (pintype "bidirectional"))
    )
    (net (code "20") (name "FAN_CTRL") (class "Default")
      (node (ref "FCTL") (pin "TP") (pinfunction "P$1_TP") (pintype "bidirectional"))
      (node (ref "IC15") (pin "34") (pinfunction "GPIO22_34") (pintype "bidirectional"))
      (node (ref "R164") (pin "1") (pinfunction "1_1") (pintype "passive"))
      (node (ref "R165") (pin "1") (pinfunction "1_1") (pintype "passive"))
      (node (ref "T1") (pin "1") (pinfunction "G_1") (pintype "passive"))
    )
    (net (code "21") (name "FB1") (class "Default")
      (node (ref "C5") (pin "2") (pinfunction "2_2") (pintype "passive"))
      (node (ref "FB1") (pin "TP") (pinfunction "P$1_TP") (pintype "bidirectional"))
      (node (ref "IC13") (pin "2") (pinfunction "FB_2") (pintype "input"))
      (node (ref "R60") (pin "1") (pinfunction "1_1") (pintype "passive"))
      (node (ref "R61") (pin "2") (pinfunction "2_2") (pintype "passive"))
    )
    (net (code "22") (name "FB2") (class "Default")
      (node (ref "C51") (pin "2") (pinfunction "2_2") (pintype "passive"))
      (node (ref "FB2") (pin "TP") (pinfunction "P$1_TP") (pintype "bidirectional"))
      (node (ref "IC5") (pin "2") (pinfunction "FB_2") (pintype "input"))
      (node (ref "R105") (pin "2") (pinfunction "2_2") (pintype "passive"))
      (node (ref "R107") (pin "1") (pinfunction "1_1") (pintype "passive"))
    )
    (net (code "23") (name "FBIN1") (class "Default")
      (node (ref "C22") (pin "2") (pinfunction "2_2") (pintype "passive"))
      (node (ref "D9") (pin "C") (pinfunction "C_C") (pintype "passive"))
      (node (ref "R61") (pin "1") (pinfunction "1_1") (pintype "passive"))
    )
    (net (code "24") (name "FBIN2") (class "Default")
      (node (ref "C52") (pin "2") (pinfunction "2_2") (pintype "passive"))
      (node (ref "D13") (pin "C") (pinfunction "C_C") (pintype "passive"))
      (node (ref "R105") (pin "1") (pinfunction "1_1") (pintype "passive"))
    )
    (net (code "25") (name "GND") (class "Default")
      (node (ref "AC/DC1") (pin "-V") (pinfunction "-V_-V") (pintype "output"))
      (node (ref "AC/DC2") (pin "-V") (pinfunction "-V_-V") (pintype "output"))
      (node (ref "BT") (pin "2") (pinfunction "P$2_2") (pintype "bidirectional"))
      (node (ref "C1") (pin "2") (pinfunction "2_2") (pintype "passive"))
      (node (ref "C10") (pin "2") (pinfunction "-_2") (pintype "passive"))
      (node (ref "C100") (pin "2") (pinfunction "2_2") (pintype "passive"))
      (node (ref "C101") (pin "2") (pinfunction "2_2") (pintype "passive"))
      (node (ref "C102") (pin "2") (pinfunction "2_2") (pintype "passive"))
      (node (ref "C103") (pin "2") (pinfunction "2_2") (pintype "passive"))
      (node (ref "C104") (pin "2") (pinfunction "2_2") (pintype "passive"))
      (node (ref "C105") (pin "2") (pinfunction "2_2") (pintype "passive"))
      (node (ref "C13") (pin "2") (pinfunction "-_2") (pintype "passive"))
      (node (ref "C14") (pin "2") (pinfunction "2_2") (pintype "passive"))
      (node (ref "C15") (pin "2") (pinfunction "2_2") (pintype "passive"))
      (node (ref "C16") (pin "2") (pinfunction "-_2") (pintype "passive"))
      (node (ref "C17") (pin "2") (pinfunction "2_2") (pintype "passive"))
      (node (ref "C18") (pin "2") (pinfunction "2_2") (pintype "passive"))
      (node (ref "C19") (pin "2") (pinfunction "2_2") (pintype "passive"))
      (node (ref "C2") (pin "2") (pinfunction "2_2") (pintype "passive"))
      (node (ref "C20") (pin "2") (pinfunction "2_2") (pintype "passive"))
      (node (ref "C3") (pin "2") (pinfunction "2_2") (pintype "passive"))
      (node (ref "C33") (pin "2") (pinfunction "2_2") (pintype "passive"))
      (node (ref "C34") (pin "2") (pinfunction "2_2") (pintype "passive"))
      (node (ref "C4") (pin "2") (pinfunction "2_2") (pintype "passive"))
      (node (ref "C58") (pin "2") (pinfunction "2_2") (pintype "passive"))
      (node (ref "C59") (pin "2") (pinfunction "2_2") (pintype "passive"))
      (node (ref "C6") (pin "2") (pinfunction "2_2") (pintype "passive"))
      (node (ref "C60") (pin "2") (pinfunction "2_2") (pintype "passive"))
      (node (ref "C61") (pin "2") (pinfunction "2_2") (pintype "passive"))
      (node (ref "C62") (pin "2") (pinfunction "2_2") (pintype "passive"))
      (node (ref "C63") (pin "2") (pinfunction "2_2") (pintype "passive"))
      (node (ref "C64") (pin "2") (pinfunction "2_2") (pintype "passive"))
      (node (ref "C65") (pin "2") (pinfunction "2_2") (pintype "passive"))
      (node (ref "C66") (pin "2") (pinfunction "2_2") (pintype "passive"))
      (node (ref "C67") (pin "2") (pinfunction "2_2") (pintype "passive"))
      (node (ref "C68") (pin "2") (pinfunction "2_2") (pintype "passive"))
      (node (ref "C69") (pin "2") (pinfunction "2_2") (pintype "passive"))
      (node (ref "C7") (pin "2") (pinfunction "2_2") (pintype "passive"))
      (node (ref "C70") (pin "2") (pinfunction "2_2") (pintype "passive"))
      (node (ref "C71") (pin "2") (pinfunction "2_2") (pintype "passive"))
      (node (ref "C72") (pin "2") (pinfunction "2_2") (pintype "passive"))
      (node (ref "C73") (pin "2") (pinfunction "2_2") (pintype "passive"))
      (node (ref "C74") (pin "2") (pinfunction "2_2") (pintype "passive"))
      (node (ref "C75") (pin "2") (pinfunction "2_2") (pintype "passive"))
      (node (ref "C76") (pin "2") (pinfunction "2_2") (pintype "passive"))
      (node (ref "C77") (pin "2") (pinfunction "2_2") (pintype "passive"))
      (node (ref "C78") (pin "2") (pinfunction "2_2") (pintype "passive"))
      (node (ref "C79") (pin "2") (pinfunction "2_2") (pintype "passive"))
      (node (ref "C80") (pin "2") (pinfunction "2_2") (pintype "passive"))
      (node (ref "C83") (pin "1") (pinfunction "1_1") (pintype "passive"))
      (node (ref "C84") (pin "2") (pinfunction "2_2") (pintype "passive"))
      (node (ref "C85") (pin "2") (pinfunction "2_2") (pintype "passive"))
      (node (ref "C86") (pin "2") (pinfunction "2_2") (pintype "passive"))
      (node (ref "C87") (pin "2") (pinfunction "2_2") (pintype "passive"))
      (node (ref "C88") (pin "2") (pinfunction "2_2") (pintype "passive"))
      (node (ref "C89") (pin "2") (pinfunction "2_2") (pintype "passive"))
      (node (ref "C90") (pin "2") (pinfunction "2_2") (pintype "passive"))
      (node (ref "C91") (pin "2") (pinfunction "2_2") (pintype "passive"))
      (node (ref "C92") (pin "2") (pinfunction "2_2") (pintype "passive"))
      (node (ref "C93") (pin "2") (pinfunction "2_2") (pintype "passive"))
      (node (ref "C94") (pin "2") (pinfunction "2_2") (pintype "passive"))
      (node (ref "C95") (pin "2") (pinfunction "2_2") (pintype "passive"))
      (node (ref "C96") (pin "2") (pinfunction "2_2") (pintype "passive"))
      (node (ref "C97") (pin "2") (pinfunction "2_2") (pintype "passive"))
      (node (ref "C98") (pin "2") (pinfunction "2_2") (pintype "passive"))
      (node (ref "C99") (pin "2") (pinfunction "2_2") (pintype "passive"))
      (node (ref "D16") (pin "A") (pinfunction "A_A") (pintype "passive"))
      (node (ref "D17") (pin "3") (pinfunction "3_3") (pintype "bidirectional"))
      (node (ref "D18") (pin "3") (pinfunction "3_3") (pintype "bidirectional"))
      (node (ref "DAT") (pin "C") (pinfunction "C_C") (pintype "passive"))
      (node (ref "DSP") (pin "5") (pinfunction "5_5") (pintype "bidirectional"))
      (node (ref "DSP") (pin "8") (pinfunction "8_8") (pintype "bidirectional"))
      (node (ref "DSP") (pin "Z0") (pinfunction "Z1_Z0") (pintype "bidirectional"))
      (node (ref "DSP") (pin "Z1") (pinfunction "Z1_Z1") (pintype "bidirectional"))
      (node (ref "DSP") (pin "Z2") (pinfunction "Z2_Z2") (pintype "bidirectional"))
      (node (ref "DSP") (pin "Z3") (pinfunction "Z3_Z3") (pintype "bidirectional"))
      (node (ref "DSP") (pin "Z4") (pinfunction "Z3_Z4") (pintype "bidirectional"))
      (node (ref "DSP") (pin "Z5") (pinfunction "Z4_Z5") (pintype "bidirectional"))
      (node (ref "ESD1") (pin "1") (pinfunction "A_1") (pintype "bidirectional"))
      (node (ref "ETH1") (pin "8") (pinfunction "GND_8") (pintype "power_in"))
      (node (ref "GDRC") (pin "4") (pinfunction "P$4_4") (pintype "bidirectional"))
      (node (ref "GND") (pin "TP") (pinfunction "P$1_TP") (pintype "bidirectional"))
      (node (ref "GND-3") (pin "TP") (pinfunction "P$1_TP") (pintype "bidirectional"))
      (node (ref "GND-5") (pin "TP") (pinfunction "P$1_TP") (pintype "bidirectional"))
      (node (ref "IC1") (pin "4") (pinfunction "GND_4") (pintype "bidirectional"))
      (node (ref "IC15") (pin "19") (pinfunction "TESTEN_19") (pintype "bidirectional"))
      (node (ref "IC15") (pin "PAD") (pinfunction "GND_PAD") (pintype "bidirectional"))
      (node (ref "IC17") (pin "5") (pinfunction "V-_5") (pintype "power_in"))
      (node (ref "IC18") (pin "4") (pinfunction "GND_4") (pintype "power_in"))
      (node (ref "IC18") (pin "PAD") (pinfunction "GND_PAD") (pintype "power_in"))
      (node (ref "IC19") (pin "2") (pinfunction "A1_2") (pintype "bidirectional"))
      (node (ref "IC19") (pin "3") (pinfunction "A2_3") (pintype "bidirectional"))
      (node (ref "IC19") (pin "4") (pinfunction "GND_4") (pintype "power_in"))
      (node (ref "IC19") (pin "7") (pinfunction "WP_7") (pintype "bidirectional"))
      (node (ref "IC19") (pin "9") (pinfunction "GND_9") (pintype "power_in"))
      (node (ref "IC2") (pin "4") (pinfunction "GND_4") (pintype "bidirectional"))
      (node (ref "IC20") (pin "14") (pinfunction "AGND_14") (pintype "power_in"))
      (node (ref "IC20") (pin "16") (pinfunction "AGND_16") (pintype "power_in"))
      (node (ref "IC20") (pin "19") (pinfunction "AGND_19") (pintype "power_in"))
      (node (ref "IC20") (pin "29") (pinfunction "GND_29") (pintype "passive"))
      (node (ref "IC20") (pin "3") (pinfunction "AGND_3") (pintype "power_in"))
      (node (ref "IC20") (pin "48") (pinfunction "AGND_48") (pintype "power_in"))
      (node (ref "IC20") (pin "9") (pinfunction "AGND_9") (pintype "power_in"))
      (node (ref "IC21") (pin "2") (pinfunction "GND_2") (pintype "bidirectional"))
      (node (ref "IC22") (pin "5") (pinfunction "V-_5") (pintype "power_in"))
      (node (ref "IC23") (pin "2") (pinfunction "GND_2") (pintype "power_in"))
      (node (ref "IC3") (pin "9") (pinfunction "GND_9") (pintype "bidirectional"))
      (node (ref "IC4") (pin "11") (pinfunction "A0_11") (pintype "bidirectional"))
      (node (ref "IC4") (pin "12") (pinfunction "A1_12") (pintype "bidirectional"))
      (node (ref "IC4") (pin "13") (pinfunction "A2_13") (pintype "bidirectional"))
      (node (ref "IC4") (pin "6") (pinfunction "VSS_6") (pintype "bidirectional"))
      (node (ref "IC4") (pin "PAD") (pinfunction "VSS_PAD") (pintype "bidirectional"))
      (node (ref "IC9") (pin "8") (pinfunction "GND_8") (pintype "power_in"))
      (node (ref "OPT1") (pin "11") (pinfunction "11_11") (pintype "passive"))
      (node (ref "OPT1") (pin "13") (pinfunction "13_13") (pintype "passive"))
      (node (ref "OPT1") (pin "15") (pinfunction "15_15") (pintype "passive"))
      (node (ref "OPT1") (pin "9") (pinfunction "9_9") (pintype "passive"))
      (node (ref "OPT2") (pin "11") (pinfunction "11_11") (pintype "passive"))
      (node (ref "OPT2") (pin "13") (pinfunction "13_13") (pintype "passive"))
      (node (ref "OPT2") (pin "15") (pinfunction "15_15") (pintype "passive"))
      (node (ref "OPT2") (pin "9") (pinfunction "9_9") (pintype "passive"))
      (node (ref "P12ON") (pin "C") (pinfunction "C_C") (pintype "passive"))
      (node (ref "P3ON") (pin "C") (pinfunction "C_C") (pintype "passive"))
      (node (ref "P5ON") (pin "C") (pinfunction "C_C") (pintype "passive"))
      (node (ref "PROC") (pin "C") (pinfunction "C_C") (pintype "passive"))
      (node (ref "R110") (pin "1") (pinfunction "1_1") (pintype "passive"))
      (node (ref "R12") (pin "2") (pinfunction "2_2") (pintype "passive"))
      (node (ref "R121") (pin "2") (pinfunction "2_2") (pintype "passive"))
      (node (ref "R124") (pin "2") (pinfunction "2_2") (pintype "passive"))
      (node (ref "R125") (pin "2") (pinfunction "2_2") (pintype "passive"))
      (node (ref "R127") (pin "2") (pinfunction "2_2") (pintype "passive"))
      (node (ref "R129") (pin "1") (pinfunction "1_1") (pintype "passive"))
      (node (ref "R131") (pin "2") (pinfunction "2_2") (pintype "passive"))
      (node (ref "R14") (pin "2") (pinfunction "2_2") (pintype "passive"))
      (node (ref "R143") (pin "1") (pinfunction "1_1") (pintype "passive"))
      (node (ref "R151") (pin "1") (pinfunction "1_1") (pintype "passive"))
      (node (ref "R161") (pin "1") (pinfunction "1_1") (pintype "passive"))
      (node (ref "R164") (pin "2") (pinfunction "2_2") (pintype "passive"))
      (node (ref "R2") (pin "1") (pinfunction "1_1") (pintype "passive"))
      (node (ref "R4") (pin "2") (pinfunction "2_2") (pintype "passive"))
      (node (ref "R6") (pin "2") (pinfunction "2_2") (pintype "passive"))
      (node (ref "R93") (pin "A2") (pinfunction "8_A2") (pintype "passive"))
      (node (ref "R93") (pin "B2") (pinfunction "7_B2") (pintype "passive"))
      (node (ref "R93") (pin "C2") (pinfunction "6_C2") (pintype "passive"))
      (node (ref "R93") (pin "D2") (pinfunction "5_D2") (pintype "passive"))
      (node (ref "R95") (pin "1") (pinfunction "1_1") (pintype "passive"))
      (node (ref "REF1") (pin "2") (pinfunction "A_2") (pintype "passive"))
      (node (ref "REF1") (pin "3") (pinfunction "A_3") (pintype "passive"))
      (node (ref "RES") (pin "1") (pinfunction "P$1_1") (pintype "bidirectional"))
      (node (ref "RGTG") (pin "2") (pinfunction "P$2_2") (pintype "bidirectional"))
      (node (ref "RGTG") (pin "4") (pinfunction "P$4_4") (pintype "bidirectional"))
      (node (ref "RN1") (pin "A1") (pinfunction "1_A1") (pintype "passive"))
      (node (ref "RN1") (pin "B1") (pinfunction "1_B1") (pintype "passive"))
      (node (ref "RN1") (pin "C1") (pinfunction "1_C1") (pintype "passive"))
      (node (ref "RN1") (pin "D1") (pinfunction "1_D1") (pintype "passive"))
      (node (ref "RN2") (pin "A1") (pinfunction "1_A1") (pintype "passive"))
      (node (ref "RN2") (pin "B1") (pinfunction "1_B1") (pintype "passive"))
      (node (ref "RN2") (pin "C1") (pinfunction "1_C1") (pintype "passive"))
      (node (ref "RN2") (pin "D1") (pinfunction "1_D1") (pintype "passive"))
      (node (ref "T1") (pin "2") (pinfunction "S_2") (pintype "passive"))
      (node (ref "USB1") (pin "GND") (pinfunction "GND_GND") (pintype "power_in"))
      (node (ref "USB1") (pin "GND2") (pinfunction "GND_GND2") (pintype "power_in"))
      (node (ref "X1") (pin "2") (pinfunction "GND_2") (pintype "passive"))
      (node (ref "X1") (pin "4") (pinfunction "GND_4") (pintype "passive"))
      (node (ref "X2") (pin "2") (pinfunction "GND_2") (pintype "passive"))
      (node (ref "X2") (pin "4") (pinfunction "GND_4") (pintype "passive"))
    )
    (net (code "26") (name "I2C0_SCL") (class "Default")
      (node (ref "D17") (pin "1") (pinfunction "1_1") (pintype "bidirectional"))
      (node (ref "DSP") (pin "7") (pinfunction "7_7") (pintype "bidirectional"))
      (node (ref "IC15") (pin "7") (pinfunction "GPIO5_7") (pintype "bidirectional"))
      (node (ref "R130") (pin "2") (pinfunction "2_2") (pintype "passive"))
      (node (ref "SCL0") (pin "TP") (pinfunction "P$1_TP") (pintype "bidirectional"))
    )
    (net (code "27") (name "I2C0_SDA") (class "Default")
      (node (ref "D17") (pin "2") (pinfunction "2_2") (pintype "bidirectional"))
      (node (ref "DSP") (pin "6") (pinfunction "6_6") (pintype "bidirectional"))
      (node (ref "IC15") (pin "6") (pinfunction "GPIO4_6") (pintype "bidirectional"))
      (node (ref "R166") (pin "2") (pinfunction "2_2") (pintype "passive"))
      (node (ref "SDA0") (pin "TP") (pinfunction "P$1_TP") (pintype "bidirectional"))
    )
    (net (code "28") (name "I2C1_SCL") (class "Default")
      (node (ref "D18") (pin "2") (pinfunction "2_2") (pintype "bidirectional"))
      (node (ref "IC15") (pin "5") (pinfunction "GPIO3_5") (pintype "bidirectional"))
      (node (ref "IC19") (pin "6") (pinfunction "SCL_6") (pintype "bidirectional"))
      (node (ref "IC4") (pin "8") (pinfunction "SCL_8") (pintype "bidirectional"))
      (node (ref "R167") (pin "2") (pinfunction "2_2") (pintype "passive"))
      (node (ref "SCL1") (pin "TP") (pinfunction "P$1_TP") (pintype "bidirectional"))
    )
    (net (code "29") (name "I2C1_SDA") (class "Default")
      (node (ref "D18") (pin "1") (pinfunction "1_1") (pintype "bidirectional"))
      (node (ref "IC15") (pin "4") (pinfunction "GPIO2_4") (pintype "bidirectional"))
      (node (ref "IC19") (pin "5") (pinfunction "SDA_5") (pintype "bidirectional"))
      (node (ref "IC4") (pin "9") (pinfunction "SDA_9") (pintype "bidirectional"))
      (node (ref "R168") (pin "2") (pinfunction "2_2") (pintype "passive"))
      (node (ref "SDA1") (pin "TP") (pinfunction "P$1_TP") (pintype "bidirectional"))
    )
    (net (code "30") (name "KEY_0") (class "Default")
      (node (ref "DSP") (pin "12") (pinfunction "12_12") (pintype "bidirectional"))
      (node (ref "IC15") (pin "15") (pinfunction "GPIO12_15") (pintype "bidirectional"))
    )
    (net (code "31") (name "KEY_1") (class "Default")
      (node (ref "DSP") (pin "11") (pinfunction "11_11") (pintype "bidirectional"))
      (node (ref "IC15") (pin "16") (pinfunction "GPIO13_16") (pintype "bidirectional"))
    )
    (net (code "32") (name "KEY_2") (class "Default")
      (node (ref "DSP") (pin "10") (pinfunction "10_10") (pintype "bidirectional"))
      (node (ref "IC15") (pin "17") (pinfunction "GPIO14_17") (pintype "bidirectional"))
    )
    (net (code "33") (name "KEY_3") (class "Default")
      (node (ref "DSP") (pin "9") (pinfunction "9_9") (pintype "bidirectional"))
      (node (ref "IC15") (pin "18") (pinfunction "GPIO15_18") (pintype "bidirectional"))
    )
    (net (code "34") (name "LCD_BL") (class "Default")
      (node (ref "DSP") (pin "13") (pinfunction "13_13") (pintype "bidirectional"))
      (node (ref "IC15") (pin "9") (pinfunction "GPIO7_9") (pintype "bidirectional"))
    )
    (net (code "35") (name "LCD_CS") (class "Default")
      (node (ref "CS") (pin "TP") (pinfunction "P$1_TP") (pintype "bidirectional"))
      (node (ref "DSP") (pin "19") (pinfunction "19_19") (pintype "bidirectional"))
      (node (ref "IC15") (pin "12") (pinfunction "GPIO9_12") (pintype "bidirectional"))
      (node (ref "R149") (pin "C2") (pinfunction "6_C2") (pintype "passive"))
    )
    (net (code "36") (name "LCD_DC") (class "Default")
      (node (ref "DSP") (pin "18") (pinfunction "18_18") (pintype "bidirectional"))
      (node (ref "IC15") (pin "8") (pinfunction "GPIO6_8") (pintype "bidirectional"))
    )
    (net (code "37") (name "LCD_MISO") (class "Default")
      (node (ref "DSP") (pin "15") (pinfunction "15_15") (pintype "bidirectional"))
      (node (ref "IC15") (pin "11") (pinfunction "GPIO8_11") (pintype "bidirectional"))
      (node (ref "MI") (pin "TP") (pinfunction "P$1_TP") (pintype "bidirectional"))
      (node (ref "R149") (pin "B2") (pinfunction "7_B2") (pintype "passive"))
    )
    (net (code "38") (name "LCD_MOSI") (class "Default")
      (node (ref "DSP") (pin "16") (pinfunction "16_16") (pintype "bidirectional"))
      (node (ref "IC15") (pin "14") (pinfunction "GPIO11_14") (pintype "bidirectional"))
      (node (ref "MO") (pin "TP") (pinfunction "P$1_TP") (pintype "bidirectional"))
    )
    (net (code "39") (name "LCD_RES") (class "Default")
      (node (ref "DSP") (pin "14") (pinfunction "14_14") (pintype "bidirectional"))
      (node (ref "R149") (pin "A2") (pinfunction "8_A2") (pintype "passive"))
    )
    (net (code "40") (name "LCD_SCLK") (class "Default")
      (node (ref "DSP") (pin "17") (pinfunction "17_17") (pintype "bidirectional"))
      (node (ref "IC15") (pin "13") (pinfunction "GPIO10_13") (pintype "bidirectional"))
      (node (ref "SC") (pin "TP") (pinfunction "P$1_TP") (pintype "bidirectional"))
    )
    (net (code "41") (name "LREC1") (class "Default")
      (node (ref "C35") (pin "1") (pinfunction "+_1") (pintype "passive"))
      (node (ref "D10") (pin "C") (pinfunction "C_C") (pintype "passive"))
      (node (ref "IC13") (pin "5") (pinfunction "DRAIN_5") (pintype "input"))
      (node (ref "L-REC1") (pin "TP") (pinfunction "P$1_TP") (pintype "bidirectional"))
    )
    (net (code "42") (name "LREC2") (class "Default")
      (node (ref "C47") (pin "1") (pinfunction "+_1") (pintype "passive"))
      (node (ref "D12") (pin "C") (pinfunction "C_C") (pintype "passive"))
      (node (ref "IC5") (pin "5") (pinfunction "DRAIN_5") (pintype "input"))
      (node (ref "L-REC2") (pin "TP") (pinfunction "P$1_TP") (pintype "bidirectional"))
    )
    (net (code "43") (name "MCP_DSP_RST") (class "Default")
      (node (ref "DSP") (pin "20") (pinfunction "20_20") (pintype "bidirectional"))
      (node (ref "IC15") (pin "36") (pinfunction "GPIO24_36") (pintype "bidirectional"))
      (node (ref "R147") (pin "1") (pinfunction "1_1") (pintype "passive"))
    )
    (net (code "44") (name "MCP_REL_RST") (class "Default")
      (node (ref "IC15") (pin "35") (pinfunction "GPIO23_35") (pintype "bidirectional"))
      (node (ref "IC4") (pin "14") (pinfunction "~{RESET}_14") (pintype "bidirectional"))
    )
    (net (code "45") (name "MCP_VIN") (class "Default")
      (node (ref "C102") (pin "1") (pinfunction "1_1") (pintype "passive"))
      (node (ref "C63") (pin "1") (pinfunction "1_1") (pintype "passive"))
      (node (ref "DNI") (pin "2") (pinfunction "2_2") (pintype "passive"))
      (node (ref "IC17") (pin "2") (pinfunction "V+_2") (pintype "power_in"))
      (node (ref "MCPVIN") (pin "TP") (pinfunction "P$1_TP") (pintype "bidirectional"))
      (node (ref "R152") (pin "2") (pinfunction "2_2") (pintype "passive"))
    )
    (net (code "46") (name "MUX_A") (class "Default")
      (node (ref "IC4") (pin "25") (pinfunction "IO2.0_25") (pintype "bidirectional"))
      (node (ref "IC9") (pin "11") (pinfunction "A_11") (pintype "input"))
      (node (ref "R93") (pin "D1") (pinfunction "4_D1") (pintype "passive"))
    )
    (net (code "47") (name "MUX_B") (class "Default")
      (node (ref "IC4") (pin "26") (pinfunction "IO2.1_26") (pintype "bidirectional"))
      (node (ref "IC9") (pin "10") (pinfunction "B_10") (pintype "input"))
      (node (ref "R93") (pin "C1") (pinfunction "3_C1") (pintype "passive"))
    )
    (net (code "48") (name "MUX_C") (class "Default")
      (node (ref "IC4") (pin "27") (pinfunction "IO2.2_27") (pintype "bidirectional"))
      (node (ref "IC9") (pin "9") (pinfunction "C_9") (pintype "input"))
      (node (ref "R93") (pin "B1") (pinfunction "2_B1") (pintype "passive"))
    )
    (net (code "49") (name "MUX_EN") (class "Default")
      (node (ref "IC4") (pin "28") (pinfunction "IO2.3_28") (pintype "bidirectional"))
      (node (ref "IC9") (pin "7") (pinfunction "~{EN}_7") (pintype "input"))
      (node (ref "R93") (pin "A1") (pinfunction "1_A1") (pintype "passive"))
    )
    (net (code "50") (name "N_OUT1") (class "Default")
      (node (ref "N_OUT1") (pin "1") (pinfunction "MOUNT_1") (pintype "passive"))
      (node (ref "N_OUT1") (pin "2") (pinfunction "MOUNT_2") (pintype "passive"))
      (node (ref "R25") (pin "1") (pinfunction "1_1") (pintype "passive"))
      (node (ref "R34") (pin "1") (pinfunction "1_1") (pintype "passive"))
      (node (ref "R35") (pin "1") (pinfunction "1_1") (pintype "passive"))
    )
    (net (code "51") (name "N_OUT2") (class "Default")
      (node (ref "N_OUT2") (pin "1") (pinfunction "MOUNT_1") (pintype "passive"))
      (node (ref "N_OUT2") (pin "2") (pinfunction "MOUNT_2") (pintype "passive"))
      (node (ref "R32") (pin "1") (pinfunction "1_1") (pintype "passive"))
      (node (ref "R50") (pin "1") (pinfunction "1_1") (pintype "passive"))
      (node (ref "R51") (pin "1") (pinfunction "1_1") (pintype "passive"))
    )
    (net (code "52") (name "N_OUT3") (class "Default")
      (node (ref "N_OUT3") (pin "1") (pinfunction "MOUNT_1") (pintype "passive"))
      (node (ref "N_OUT3") (pin "2") (pinfunction "MOUNT_2") (pintype "passive"))
      (node (ref "R31") (pin "1") (pinfunction "1_1") (pintype "passive"))
      (node (ref "R66") (pin "1") (pinfunction "1_1") (pintype "passive"))
      (node (ref "R67") (pin "1") (pinfunction "1_1") (pintype "passive"))
    )
    (net (code "53") (name "N_OUT4") (class "Default")
      (node (ref "N_OUT4") (pin "1") (pinfunction "MOUNT_1") (pintype "passive"))
      (node (ref "N_OUT4") (pin "2") (pinfunction "MOUNT_2") (pintype "passive"))
      (node (ref "R30") (pin "1") (pinfunction "1_1") (pintype "passive"))
      (node (ref "R82") (pin "1") (pinfunction "1_1") (pintype "passive"))
      (node (ref "R83") (pin "1") (pinfunction "1_1") (pintype "passive"))
    )
    (net (code "54") (name "N_OUT5") (class "Default")
      (node (ref "N_OUT5") (pin "1") (pinfunction "MOUNT_1") (pintype "passive"))
      (node (ref "N_OUT5") (pin "2") (pinfunction "MOUNT_2") (pintype "passive"))
      (node (ref "R26") (pin "1") (pinfunction "1_1") (pintype "passive"))
      (node (ref "R42") (pin "1") (pinfunction "1_1") (pintype "passive"))
      (node (ref "R43") (pin "1") (pinfunction "1_1") (pintype "passive"))
    )
    (net (code "55") (name "N_OUT6") (class "Default")
      (node (ref "N_OUT6") (pin "1") (pinfunction "MOUNT_1") (pintype "passive"))
      (node (ref "N_OUT6") (pin "2") (pinfunction "MOUNT_2") (pintype "passive"))
      (node (ref "R27") (pin "1") (pinfunction "1_1") (pintype "passive"))
      (node (ref "R74") (pin "1") (pinfunction "1_1") (pintype "passive"))
      (node (ref "R75") (pin "1") (pinfunction "1_1") (pintype "passive"))
    )
    (net (code "56") (name "N_OUT7") (class "Default")
      (node (ref "N_OUT7") (pin "1") (pinfunction "MOUNT_1") (pintype "passive"))
      (node (ref "N_OUT7") (pin "2") (pinfunction "MOUNT_2") (pintype "passive"))
      (node (ref "R28") (pin "1") (pinfunction "1_1") (pintype "passive"))
      (node (ref "R98") (pin "1") (pinfunction "1_1") (pintype "passive"))
      (node (ref "R99") (pin "1") (pinfunction "1_1") (pintype "passive"))
    )
    (net (code "57") (name "N_OUT8") (class "Default")
      (node (ref "N_OUT8") (pin "1") (pinfunction "MOUNT_1") (pintype "passive"))
      (node (ref "N_OUT8") (pin "2") (pinfunction "MOUNT_2") (pintype "passive"))
      (node (ref "R114") (pin "1") (pinfunction "1_1") (pintype "passive"))
      (node (ref "R115") (pin "1") (pinfunction "1_1") (pintype "passive"))
      (node (ref "R29") (pin "1") (pinfunction "1_1") (pintype "passive"))
    )
    (net (code "58") (name "Net-(3VFB-P$1)") (class "Default")
      (node (ref "3VFB") (pin "TP") (pinfunction "P$1_TP") (pintype "bidirectional"))
      (node (ref "C12") (pin "2") (pinfunction "2_2") (pintype "passive"))
      (node (ref "R10") (pin "2") (pinfunction "2_2") (pintype "passive"))
      (node (ref "R13") (pin "2") (pinfunction "2_2") (pintype "passive"))
      (node (ref "R14") (pin "1") (pinfunction "1_1") (pintype "passive"))
    )
    (net (code "59") (name "Net-(5VFB-P$1)") (class "Default")
      (node (ref "5VFB") (pin "TP") (pinfunction "P$1_TP") (pintype "bidirectional"))
      (node (ref "C11") (pin "2") (pinfunction "2_2") (pintype "passive"))
      (node (ref "R11") (pin "2") (pinfunction "2_2") (pintype "passive"))
      (node (ref "R12") (pin "1") (pinfunction "1_1") (pintype "passive"))
      (node (ref "R8") (pin "2") (pinfunction "2_2") (pintype "passive"))
    )
    (net (code "60") (name "Net-(12VDC-P$1)") (class "Default")
      (node (ref "12VDC") (pin "TP") (pinfunction "P$1_TP") (pintype "bidirectional"))
      (node (ref "AC/DC1") (pin "+V") (pinfunction "+V_+V") (pintype "output"))
      (node (ref "AC/DC2") (pin "+V") (pinfunction "+V_+V") (pintype "output"))
      (node (ref "C10") (pin "1") (pinfunction "+_1") (pintype "passive"))
      (node (ref "C13") (pin "1") (pinfunction "+_1") (pintype "passive"))
      (node (ref "C16") (pin "1") (pinfunction "+_1") (pintype "passive"))
      (node (ref "D16") (pin "C") (pinfunction "C_C") (pintype "passive"))
      (node (ref "J10") (pin "2") (pinfunction "2_2") (pintype "passive"))
      (node (ref "J8") (pin "2") (pinfunction "2_2") (pintype "passive"))
      (node (ref "J9") (pin "2") (pinfunction "2_2") (pintype "passive"))
    )
    (net (code "61") (name "Net-(C8-Pad1)") (class "Default")
      (node (ref "C8") (pin "1") (pinfunction "1_1") (pintype "passive"))
      (node (ref "R7") (pin "1") (pinfunction "1_1") (pintype "passive"))
    )
    (net (code "62") (name "Net-(C9-Pad1)") (class "Default")
      (node (ref "C9") (pin "1") (pinfunction "1_1") (pintype "passive"))
      (node (ref "R9") (pin "1") (pinfunction "1_1") (pintype "passive"))
    )
    (net (code "63") (name "Net-(C106-Pad1)") (class "Default")
      (node (ref "C106") (pin "1") (pinfunction "1_1") (pintype "passive"))
      (node (ref "OPT1") (pin "2") (pinfunction "2_2") (pintype "passive"))
      (node (ref "R59") (pin "2") (pinfunction "2_2") (pintype "passive"))
    )
    (net (code "64") (name "Net-(C107-Pad1)") (class "Default")
      (node (ref "C107") (pin "1") (pinfunction "1_1") (pintype "passive"))
      (node (ref "OPT1") (pin "4") (pinfunction "4_4") (pintype "passive"))
      (node (ref "R153") (pin "2") (pinfunction "2_2") (pintype "passive"))
    )
    (net (code "65") (name "Net-(C108-Pad1)") (class "Default")
      (node (ref "C108") (pin "1") (pinfunction "1_1") (pintype "passive"))
      (node (ref "OPT1") (pin "6") (pinfunction "6_6") (pintype "passive"))
      (node (ref "R154") (pin "2") (pinfunction "2_2") (pintype "passive"))
    )
    (net (code "66") (name "Net-(C109-Pad1)") (class "Default")
      (node (ref "C109") (pin "1") (pinfunction "1_1") (pintype "passive"))
      (node (ref "OPT1") (pin "8") (pinfunction "8_8") (pintype "passive"))
      (node (ref "R155") (pin "2") (pinfunction "2_2") (pintype "passive"))
    )
    (net (code "67") (name "Net-(C110-Pad1)") (class "Default")
      (node (ref "C110") (pin "1") (pinfunction "1_1") (pintype "passive"))
      (node (ref "OPT2") (pin "2") (pinfunction "2_2") (pintype "passive"))
      (node (ref "R156") (pin "2") (pinfunction "2_2") (pintype "passive"))
    )
    (net (code "68") (name "Net-(C111-Pad1)") (class "Default")
      (node (ref "C111") (pin "1") (pinfunction "1_1") (pintype "passive"))
      (node (ref "OPT2") (pin "4") (pinfunction "4_4") (pintype "passive"))
      (node (ref "R157") (pin "2") (pinfunction "2_2") (pintype "passive"))
    )
    (net (code "69") (name "Net-(C112-Pad1)") (class "Default")
      (node (ref "C112") (pin "1") (pinfunction "1_1") (pintype "passive"))
      (node (ref "OPT2") (pin "6") (pinfunction "6_6") (pintype "passive"))
      (node (ref "R158") (pin "2") (pinfunction "2_2") (pintype "passive"))
    )
    (net (code "70") (name "Net-(C113-Pad1)") (class "Default")
      (node (ref "C113") (pin "1") (pinfunction "1_1") (pintype "passive"))
      (node (ref "OPT2") (pin "8") (pinfunction "8_8") (pintype "passive"))
      (node (ref "R159") (pin "2") (pinfunction "2_2") (pintype "passive"))
    )
    (net (code "71") (name "Net-(D10-PadA)") (class "Default")
      (node (ref "D10") (pin "A") (pinfunction "A_A") (pintype "passive"))
      (node (ref "R62") (pin "2") (pinfunction "2_2") (pintype "passive"))
    )
    (net (code "72") (name "Net-(D12-PadA)") (class "Default")
      (node (ref "D12") (pin "A") (pinfunction "A_A") (pintype "passive"))
      (node (ref "R106") (pin "2") (pinfunction "2_2") (pintype "passive"))
    )
    (net (code "73") (name "Net-(DAT-PadA)") (class "Default")
      (node (ref "DAT") (pin "A") (pinfunction "A_A") (pintype "passive"))
      (node (ref "R122") (pin "2") (pinfunction "2_2") (pintype "passive"))
    )
    (net (code "74") (name "Net-(ETH1-GREEN-)") (class "Default")
      (node (ref "ETH1") (pin "9") (pinfunction "GREEN-_9") (pintype "passive"))
      (node (ref "R142") (pin "2") (pinfunction "2_2") (pintype "passive"))
    )
    (net (code "75") (name "Net-(ETH1-YELLOW-)") (class "Default")
      (node (ref "ETH1") (pin "11") (pinfunction "YELLOW-_11") (pintype "passive"))
      (node (ref "R141") (pin "2") (pinfunction "2_2") (pintype "passive"))
    )
    (net (code "76") (name "Net-(IC1-AAM)") (class "Default")
      (node (ref "IC1") (pin "1") (pinfunction "AAM_1") (pintype "bidirectional"))
      (node (ref "R3") (pin "2") (pinfunction "2_2") (pintype "passive"))
      (node (ref "R4") (pin "1") (pinfunction "1_1") (pintype "passive"))
    )
    (net (code "77") (name "Net-(IC1-BST)") (class "Default")
      (node (ref "IC1") (pin "5") (pinfunction "BST_5") (pintype "bidirectional"))
      (node (ref "R7") (pin "2") (pinfunction "2_2") (pintype "passive"))
    )
    (net (code "78") (name "Net-(IC1-FB)") (class "Default")
      (node (ref "IC1") (pin "8") (pinfunction "FB_8") (pintype "bidirectional"))
      (node (ref "R8") (pin "1") (pinfunction "1_1") (pintype "passive"))
    )
    (net (code "79") (name "Net-(IC1-SW)") (class "Default")
      (node (ref "C8") (pin "2") (pinfunction "2_2") (pintype "passive"))
      (node (ref "IC1") (pin "3") (pinfunction "SW_3") (pintype "bidirectional"))
      (node (ref "L1") (pin "1") (pinfunction "1_1") (pintype "passive"))
      (node (ref "SW") (pin "TP") (pinfunction "P$1_TP") (pintype "bidirectional"))
    )
    (net (code "80") (name "Net-(IC1-VCC)") (class "Default")
      (node (ref "C6") (pin "1") (pinfunction "1_1") (pintype "passive"))
      (node (ref "IC1") (pin "7") (pinfunction "VCC_7") (pintype "bidirectional"))
      (node (ref "R3") (pin "1") (pinfunction "1_1") (pintype "passive"))
    )
    (net (code "81") (name "Net-(IC2-AAM)") (class "Default")
      (node (ref "IC2") (pin "1") (pinfunction "AAM_1") (pintype "bidirectional"))
      (node (ref "R5") (pin "2") (pinfunction "2_2") (pintype "passive"))
      (node (ref "R6") (pin "1") (pinfunction "1_1") (pintype "passive"))
    )
    (net (code "82") (name "Net-(IC2-BST)") (class "Default")
      (node (ref "IC2") (pin "5") (pinfunction "BST_5") (pintype "bidirectional"))
      (node (ref "R9") (pin "2") (pinfunction "2_2") (pintype "passive"))
    )
    (net (code "83") (name "Net-(IC2-EN)") (class "Default")
      (node (ref "IC2") (pin "6") (pinfunction "EN_6") (pintype "bidirectional"))
      (node (ref "R171") (pin "1") (pinfunction "1_1") (pintype "passive"))
      (node (ref "R172") (pin "1") (pinfunction "1_1") (pintype "passive"))
      (node (ref "R2") (pin "2") (pinfunction "2_2") (pintype "passive"))
    )
    (net (code "84") (name "Net-(IC2-FB)") (class "Default")
      (node (ref "IC2") (pin "8") (pinfunction "FB_8") (pintype "bidirectional"))
      (node (ref "R10") (pin "1") (pinfunction "1_1") (pintype "passive"))
    )
    (net (code "85") (name "Net-(IC2-SW)") (class "Default")
      (node (ref "C9") (pin "2") (pinfunction "2_2") (pintype "passive"))
      (node (ref "IC2") (pin "3") (pinfunction "SW_3") (pintype "bidirectional"))
      (node (ref "L2") (pin "1") (pinfunction "1_1") (pintype "passive"))
      (node (ref "SW3") (pin "TP") (pinfunction "P$1_TP") (pintype "bidirectional"))
    )
    (net (code "86") (name "Net-(IC2-VCC)") (class "Default")
      (node (ref "C7") (pin "1") (pinfunction "1_1") (pintype "passive"))
      (node (ref "IC2") (pin "7") (pinfunction "VCC_7") (pintype "bidirectional"))
      (node (ref "R5") (pin "1") (pinfunction "1_1") (pintype "passive"))
    )
    (net (code "87") (name "Net-(IC3-1C)") (class "Default")
      (node (ref "IC3") (pin "18") (pinfunction "1C_18") (pintype "bidirectional"))
      (node (ref "R17") (pin "1") (pinfunction "1_1") (pintype "passive"))
    )
    (net (code "88") (name "Net-(IC3-2C)") (class "Default")
      (node (ref "IC3") (pin "17") (pinfunction "2C_17") (pintype "bidirectional"))
      (node (ref "R18") (pin "1") (pinfunction "1_1") (pintype "passive"))
    )
    (net (code "89") (name "Net-(IC3-3C)") (class "Default")
      (node (ref "IC3") (pin "16") (pinfunction "3C_16") (pintype "bidirectional"))
      (node (ref "R19") (pin "1") (pinfunction "1_1") (pintype "passive"))
    )
    (net (code "90") (name "Net-(IC3-4C)") (class "Default")
      (node (ref "IC3") (pin "15") (pinfunction "4C_15") (pintype "bidirectional"))
      (node (ref "R20") (pin "1") (pinfunction "1_1") (pintype "passive"))
    )
    (net (code "91") (name "Net-(IC3-5C)") (class "Default")
      (node (ref "IC3") (pin "14") (pinfunction "5C_14") (pintype "bidirectional"))
      (node (ref "R21") (pin "1") (pinfunction "1_1") (pintype "passive"))
    )
    (net (code "92") (name "Net-(IC3-6C)") (class "Default")
      (node (ref "IC3") (pin "13") (pinfunction "6C_13") (pintype "bidirectional"))
      (node (ref "R22") (pin "1") (pinfunction "1_1") (pintype "passive"))
    )
    (net (code "93") (name "Net-(IC3-7C)") (class "Default")
      (node (ref "IC3") (pin "12") (pinfunction "7C_12") (pintype "bidirectional"))
      (node (ref "R23") (pin "1") (pinfunction "1_1") (pintype "passive"))
    )
    (net (code "94") (name "Net-(IC3-8C)") (class "Default")
      (node (ref "IC3") (pin "11") (pinfunction "8C_11") (pintype "bidirectional"))
      (node (ref "R24") (pin "1") (pinfunction "1_1") (pintype "passive"))
    )
    (net (code "95") (name "Net-(IC6-INN)") (class "Default")
      (node (ref "C25") (pin "1") (pinfunction "1_1") (pintype "passive"))
      (node (ref "IC6") (pin "3") (pinfunction "INN_3") (pintype "input"))
      (node (ref "R34") (pin "2") (pinfunction "2_2") (pintype "passive"))
    )
    (net (code "96") (name "Net-(IC6-INP)") (class "Default")
      (node (ref "C24") (pin "1") (pinfunction "1_1") (pintype "passive"))
      (node (ref "IC6") (pin "2") (pinfunction "INP_2") (pintype "input"))
      (node (ref "R33") (pin "2") (pinfunction "2_2") (pintype "passive"))
    )
    (net (code "97") (name "Net-(IC6-VP)") (class "Default")
      (node (ref "C26") (pin "1") (pinfunction "1_1") (pintype "passive"))
      (node (ref "IC6") (pin "4") (pinfunction "VP_4") (pintype "input"))
      (node (ref "R39") (pin "2") (pinfunction "2_2") (pintype "passive"))
      (node (ref "R40") (pin "1") (pinfunction "1_1") (pintype "passive"))
    )
    (net (code "98") (name "Net-(IC7-INN)") (class "Default")
      (node (ref "C28") (pin "1") (pinfunction "1_1") (pintype "passive"))
      (node (ref "IC7") (pin "3") (pinfunction "INN_3") (pintype "input"))
      (node (ref "R42") (pin "2") (pinfunction "2_2") (pintype "passive"))
    )
    (net (code "99") (name "Net-(IC7-INP)") (class "Default")
      (node (ref "C27") (pin "1") (pinfunction "1_1") (pintype "passive"))
      (node (ref "IC7") (pin "2") (pinfunction "INP_2") (pintype "input"))
      (node (ref "R41") (pin "2") (pinfunction "2_2") (pintype "passive"))
    )
    (net (code "100") (name "Net-(IC7-VP)") (class "Default")
      (node (ref "C29") (pin "1") (pinfunction "1_1") (pintype "passive"))
      (node (ref "IC7") (pin "4") (pinfunction "VP_4") (pintype "input"))
      (node (ref "R47") (pin "2") (pinfunction "2_2") (pintype "passive"))
      (node (ref "R48") (pin "1") (pinfunction "1_1") (pintype "passive"))
    )
    (net (code "101") (name "Net-(IC8-INN)") (class "Default")
      (node (ref "C31") (pin "1") (pinfunction "1_1") (pintype "passive"))
      (node (ref "IC8") (pin "3") (pinfunction "INN_3") (pintype "input"))
      (node (ref "R50") (pin "2") (pinfunction "2_2") (pintype "passive"))
    )
    (net (code "102") (name "Net-(IC8-INP)") (class "Default")
      (node (ref "C30") (pin "1") (pinfunction "1_1") (pintype "passive"))
      (node (ref "IC8") (pin "2") (pinfunction "INP_2") (pintype "input"))
      (node (ref "R49") (pin "2") (pinfunction "2_2") (pintype "passive"))
    )
    (net (code "103") (name "Net-(IC8-VP)") (class "Default")
      (node (ref "C32") (pin "1") (pinfunction "1_1") (pintype "passive"))
      (node (ref "IC8") (pin "4") (pinfunction "VP_4") (pintype "input"))
      (node (ref "R55") (pin "2") (pinfunction "2_2") (pintype "passive"))
      (node (ref "R56") (pin "1") (pinfunction "1_1") (pintype "passive"))
    )
    (net (code "104") (name "Net-(IC10-INN)") (class "Default")
      (node (ref "C37") (pin "1") (pinfunction "1_1") (pintype "passive"))
      (node (ref "IC10") (pin "3") (pinfunction "INN_3") (pintype "input"))
      (node (ref "R66") (pin "2") (pinfunction "2_2") (pintype "passive"))
    )
    (net (code "105") (name "Net-(IC10-INP)") (class "Default")
      (node (ref "C36") (pin "1") (pinfunction "1_1") (pintype "passive"))
      (node (ref "IC10") (pin "2") (pinfunction "INP_2") (pintype "input"))
      (node (ref "R65") (pin "2") (pinfunction "2_2") (pintype "passive"))
    )
    (net (code "106") (name "Net-(IC10-VP)") (class "Default")
      (node (ref "C38") (pin "1") (pinfunction "1_1") (pintype "passive"))
      (node (ref "IC10") (pin "4") (pinfunction "VP_4") (pintype "input"))
      (node (ref "R71") (pin "2") (pinfunction "2_2") (pintype "passive"))
      (node (ref "R72") (pin "1") (pinfunction "1_1") (pintype "passive"))
    )
    (net (code "107") (name "Net-(IC11-INN)") (class "Default")
      (node (ref "C40") (pin "1") (pinfunction "1_1") (pintype "passive"))
      (node (ref "IC11") (pin "3") (pinfunction "INN_3") (pintype "input"))
      (node (ref "R74") (pin "2") (pinfunction "2_2") (pintype "passive"))
    )
    (net (code "108") (name "Net-(IC11-INP)") (class "Default")
      (node (ref "C39") (pin "1") (pinfunction "1_1") (pintype "passive"))
      (node (ref "IC11") (pin "2") (pinfunction "INP_2") (pintype "input"))
      (node (ref "R73") (pin "2") (pinfunction "2_2") (pintype "passive"))
    )
    (net (code "109") (name "Net-(IC11-VP)") (class "Default")
      (node (ref "C41") (pin "1") (pinfunction "1_1") (pintype "passive"))
      (node (ref "IC11") (pin "4") (pinfunction "VP_4") (pintype "input"))
      (node (ref "R79") (pin "2") (pinfunction "2_2") (pintype "passive"))
      (node (ref "R80") (pin "1") (pinfunction "1_1") (pintype "passive"))
    )
    (net (code "110") (name "Net-(IC12-INN)") (class "Default")
      (node (ref "C43") (pin "1") (pinfunction "1_1") (pintype "passive"))
      (node (ref "IC12") (pin "3") (pinfunction "INN_3") (pintype "input"))
      (node (ref "R82") (pin "2") (pinfunction "2_2") (pintype "passive"))
    )
    (net (code "111") (name "Net-(IC12-INP)") (class "Default")
      (node (ref "C42") (pin "1") (pinfunction "1_1") (pintype "passive"))
      (node (ref "IC12") (pin "2") (pinfunction "INP_2") (pintype "input"))
      (node (ref "R81") (pin "2") (pinfunction "2_2") (pintype "passive"))
    )
    (net (code "112") (name "Net-(IC12-VP)") (class "Default")
      (node (ref "C44") (pin "1") (pinfunction "1_1") (pintype "passive"))
      (node (ref "IC12") (pin "4") (pinfunction "VP_4") (pintype "input"))
      (node (ref "R87") (pin "2") (pinfunction "2_2") (pintype "passive"))
      (node (ref "R88") (pin "1") (pinfunction "1_1") (pintype "passive"))
    )
    (net (code "113") (name "Net-(IC14-INN)") (class "Default")
      (node (ref "C49") (pin "1") (pinfunction "1_1") (pintype "passive"))
      (node (ref "IC14") (pin "3") (pinfunction "INN_3") (pintype "input"))
      (node (ref "R98") (pin "2") (pinfunction "2_2") (pintype "passive"))
    )
    (net (code "114") (name "Net-(IC14-INP)") (class "Default")
      (node (ref "C48") (pin "1") (pinfunction "1_1") (pintype "passive"))
      (node (ref "IC14") (pin "2") (pinfunction "INP_2") (pintype "input"))
      (node (ref "R97") (pin "2") (pinfunction "2_2") (pintype "passive"))
    )
    (net (code "115") (name "Net-(IC14-VP)") (class "Default")
      (node (ref "C50") (pin "1") (pinfunction "1_1") (pintype "passive"))
      (node (ref "IC14") (pin "4") (pinfunction "VP_4") (pintype "input"))
      (node (ref "R103") (pin "2") (pinfunction "2_2") (pintype "passive"))
      (node (ref "R104") (pin "1") (pinfunction "1_1") (pintype "passive"))
    )
    (net (code "116") (name "Net-(IC15-GPIO28{slash}ADC2)") (class "Default")
      (node (ref "IC15") (pin "40") (pinfunction "GPIO28/ADC2_40") (pintype "bidirectional"))
      (node (ref "R163") (pin "2") (pinfunction "2_2") (pintype "passive"))
    )
    (net (code "117") (name "Net-(IC15-USB_DM)") (class "Default")
      (node (ref "IC15") (pin "46") (pinfunction "USB_DM_46") (pintype "bidirectional"))
      (node (ref "R15") (pin "2") (pinfunction "2_2") (pintype "passive"))
    )
    (net (code "118") (name "Net-(IC15-USB_DP)") (class "Default")
      (node (ref "IC15") (pin "47") (pinfunction "USB_DP_47") (pintype "bidirectional"))
      (node (ref "R160") (pin "2") (pinfunction "2_2") (pintype "passive"))
    )
    (net (code "119") (name "Net-(IC16-INN)") (class "Default")
      (node (ref "C55") (pin "1") (pinfunction "1_1") (pintype "passive"))
      (node (ref "IC16") (pin "3") (pinfunction "INN_3") (pintype "input"))
      (node (ref "R114") (pin "2") (pinfunction "2_2") (pintype "passive"))
    )
    (net (code "120") (name "Net-(IC16-INP)") (class "Default")
      (node (ref "C54") (pin "1") (pinfunction "1_1") (pintype "passive"))
      (node (ref "IC16") (pin "2") (pinfunction "INP_2") (pintype "input"))
      (node (ref "R113") (pin "2") (pinfunction "2_2") (pintype "passive"))
    )
    (net (code "121") (name "Net-(IC16-VP)") (class "Default")
      (node (ref "C56") (pin "1") (pinfunction "1_1") (pintype "passive"))
      (node (ref "IC16") (pin "4") (pinfunction "VP_4") (pintype "input"))
      (node (ref "R119") (pin "2") (pinfunction "2_2") (pintype "passive"))
      (node (ref "R120") (pin "1") (pinfunction "1_1") (pintype "passive"))
    )
    (net (code "122") (name "Net-(IC17-+IN)") (class "Default")
      (node (ref "C60") (pin "1") (pinfunction "1_1") (pintype "passive"))
      (node (ref "C61") (pin "1") (pinfunction "1_1") (pintype "passive"))
      (node (ref "IC17") (pin "3") (pinfunction "+IN_3") (pintype "input"))
      (node (ref "R109") (pin "1") (pinfunction "1_1") (pintype "passive"))
      (node (ref "REF1") (pin "1") (pinfunction "C_1") (pintype "passive"))
      (node (ref "VREF") (pin "TP") (pinfunction "P$1_TP") (pintype "bidirectional"))
    )
    (net (code "123") (name "Net-(IC19-A0)") (class "Default")
      (node (ref "IC19") (pin "1") (pinfunction "A0_1") (pintype "bidirectional"))
      (node (ref "R128") (pin "1") (pinfunction "1_1") (pintype "passive"))
      (node (ref "R129") (pin "2") (pinfunction "2_2") (pintype "passive"))
    )
    (net (code "124") (name "Net-(IC20-1V2O)") (class "Default")
      (node (ref "C84") (pin "1") (pinfunction "1_1") (pintype "passive"))
      (node (ref "IC20") (pin "22") (pinfunction "1V2O_22") (pintype "output"))
    )
    (net (code "125") (name "Net-(IC20-EXRES1)") (class "Default")
      (node (ref "IC20") (pin "10") (pinfunction "EXRES1_10") (pintype "bidirectional"))
      (node (ref "R143") (pin "2") (pinfunction "2_2") (pintype "passive"))
    )
    (net (code "126") (name "Net-(IC20-TOCAP)") (class "Default")
      (node (ref "C85") (pin "1") (pinfunction "1_1") (pintype "passive"))
      (node (ref "IC20") (pin "20") (pinfunction "TOCAP_20") (pintype "output"))
    )
    (net (code "127") (name "Net-(IC20-XI)") (class "Default")
      (node (ref "C87") (pin "1") (pinfunction "1_1") (pintype "passive"))
      (node (ref "IC20") (pin "30") (pinfunction "XI_30") (pintype "input"))
      (node (ref "R144") (pin "1") (pinfunction "1_1") (pintype "passive"))
      (node (ref "X2") (pin "3") (pinfunction "2_3") (pintype "passive"))
    )
    (net (code "128") (name "Net-(IC20-XO)") (class "Default")
      (node (ref "C86") (pin "1") (pinfunction "1_1") (pintype "passive"))
      (node (ref "IC20") (pin "31") (pinfunction "XO_31") (pintype "output"))
      (node (ref "R144") (pin "2") (pinfunction "2_2") (pintype "passive"))
      (node (ref "X2") (pin "1") (pinfunction "1_1") (pintype "passive"))
    )
    (net (code "129") (name "Net-(IC22--IN)") (class "Default")
      (node (ref "IC22") (pin "1") (pinfunction "OUT_1") (pintype "output"))
      (node (ref "IC22") (pin "4") (pinfunction "-IN_4") (pintype "input"))
      (node (ref "R122") (pin "1") (pinfunction "1_1") (pintype "passive"))
    )
    (net (code "130") (name "Net-(P3ON-PadA)") (class "Default")
      (node (ref "P3ON") (pin "A") (pinfunction "A_A") (pintype "passive"))
      (node (ref "R123") (pin "2") (pinfunction "2_2") (pintype "passive"))
    )
    (net (code "131") (name "Net-(P5ON-PadA)") (class "Default")
      (node (ref "P5ON") (pin "A") (pinfunction "A_A") (pintype "passive"))
      (node (ref "R148") (pin "2") (pinfunction "2_2") (pintype "passive"))
    )
    (net (code "132") (name "Net-(P12ON-PadA)") (class "Default")
      (node (ref "P12ON") (pin "A") (pinfunction "A_A") (pintype "passive"))
      (node (ref "R150") (pin "2") (pinfunction "2_2") (pintype "passive"))
    )
    (net (code "133") (name "Net-(PROC-PadA)") (class "Default")
      (node (ref "PROC") (pin "A") (pinfunction "A_A") (pintype "passive"))
      (node (ref "R163") (pin "1") (pinfunction "1_1") (pintype "passive"))
    )
    (net (code "134") (name "Net-(PWR-PadC)") (class "Default")
      (node (ref "PWR") (pin "C") (pinfunction "C_C") (pintype "passive"))
      (node (ref "R151") (pin "2") (pinfunction "2_2") (pintype "passive"))
    )
    (net (code "135") (name "Net-(R36-Pad1)") (class "Default")
      (node (ref "R36") (pin "1") (pinfunction "1_1") (pintype "passive"))
      (node (ref "R37") (pin "2") (pinfunction "2_2") (pintype "passive"))
    )
    (net (code "136") (name "Net-(R37-Pad1)") (class "Default")
      (node (ref "R37") (pin "1") (pinfunction "1_1") (pintype "passive"))
      (node (ref "R38") (pin "1") (pinfunction "1_1") (pintype "passive"))
    )
    (net (code "137") (name "Net-(R38-Pad2)") (class "Default")
      (node (ref "R38") (pin "2") (pinfunction "2_2") (pintype "passive"))
      (node (ref "R39") (pin "1") (pinfunction "1_1") (pintype "passive"))
    )
    (net (code "138") (name "Net-(R44-Pad2)") (class "Default")
      (node (ref "R44") (pin "2") (pinfunction "2_2") (pintype "passive"))
      (node (ref "R45") (pin "2") (pinfunction "2_2") (pintype "passive"))
    )
    (net (code "139") (name "Net-(R45-Pad1)") (class "Default")
      (node (ref "R45") (pin "1") (pinfunction "1_1") (pintype "passive"))
      (node (ref "R46") (pin "1") (pinfunction "1_1") (pintype "passive"))
    )
    (net (code "140") (name "Net-(R46-Pad2)") (class "Default")
      (node (ref "R46") (pin "2") (pinfunction "2_2") (pintype "passive"))
      (node (ref "R47") (pin "1") (pinfunction "1_1") (pintype "passive"))
    )
    (net (code "141") (name "Net-(R52-Pad2)") (class "Default")
      (node (ref "R52") (pin "2") (pinfunction "2_2") (pintype "passive"))
      (node (ref "R53") (pin "2") (pinfunction "2_2") (pintype "passive"))
    )
    (net (code "142") (name "Net-(R53-Pad1)") (class "Default")
      (node (ref "R53") (pin "1") (pinfunction "1_1") (pintype "passive"))
      (node (ref "R54") (pin "1") (pinfunction "1_1") (pintype "passive"))
    )
    (net (code "143") (name "Net-(R54-Pad2)") (class "Default")
      (node (ref "R54") (pin "2") (pinfunction "2_2") (pintype "passive"))
      (node (ref "R55") (pin "1") (pinfunction "1_1") (pintype "passive"))
    )
    (net (code "144") (name "Net-(R63-5)") (class "Default")
      (node (ref "OPT1") (pin "7") (pinfunction "7_7") (pintype "passive"))
      (node (ref "R63") (pin "D2") (pinfunction "5_D2") (pintype "passive"))
    )
    (net (code "145") (name "Net-(R63-6)") (class "Default")
      (node (ref "OPT1") (pin "5") (pinfunction "5_5") (pintype "passive"))
      (node (ref "R63") (pin "C2") (pinfunction "6_C2") (pintype "passive"))
    )
    (net (code "146") (name "Net-(R63-7)") (class "Default")
      (node (ref "OPT1") (pin "3") (pinfunction "3_3") (pintype "passive"))
      (node (ref "R63") (pin "B2") (pinfunction "7_B2") (pintype "passive"))
    )
    (net (code "147") (name "Net-(R63-8)") (class "Default")
      (node (ref "OPT1") (pin "1") (pinfunction "1_1") (pintype "passive"))
      (node (ref "R63") (pin "A2") (pinfunction "8_A2") (pintype "passive"))
    )
    (net (code "148") (name "Net-(R64-5)") (class "Default")
      (node (ref "OPT2") (pin "7") (pinfunction "7_7") (pintype "passive"))
      (node (ref "R64") (pin "D2") (pinfunction "5_D2") (pintype "passive"))
    )
    (net (code "149") (name "Net-(R64-6)") (class "Default")
      (node (ref "OPT2") (pin "5") (pinfunction "5_5") (pintype "passive"))
      (node (ref "R64") (pin "C2") (pinfunction "6_C2") (pintype "passive"))
    )
    (net (code "150") (name "Net-(R64-7)") (class "Default")
      (node (ref "OPT2") (pin "3") (pinfunction "3_3") (pintype "passive"))
      (node (ref "R64") (pin "B2") (pinfunction "7_B2") (pintype "passive"))
    )
    (net (code "151") (name "Net-(R64-8)") (class "Default")
      (node (ref "OPT2") (pin "1") (pinfunction "1_1") (pintype "passive"))
      (node (ref "R64") (pin "A2") (pinfunction "8_A2") (pintype "passive"))
    )
    (net (code "152") (name "Net-(R68-Pad2)") (class "Default")
      (node (ref "R68") (pin "2") (pinfunction "2_2") (pintype "passive"))
      (node (ref "R69") (pin "2") (pinfunction "2_2") (pintype "passive"))
    )
    (net (code "153") (name "Net-(R69-Pad1)") (class "Default")
      (node (ref "R69") (pin "1") (pinfunction "1_1") (pintype "passive"))
      (node (ref "R70") (pin "1") (pinfunction "1_1") (pintype "passive"))
    )
    (net (code "154") (name "Net-(R70-Pad2)") (class "Default")
      (node (ref "R70") (pin "2") (pinfunction "2_2") (pintype "passive"))
      (node (ref "R71") (pin "1") (pinfunction "1_1") (pintype "passive"))
    )
    (net (code "155") (name "Net-(R76-Pad2)") (class "Default")
      (node (ref "R76") (pin "2") (pinfunction "2_2") (pintype "passive"))
      (node (ref "R77") (pin "2") (pinfunction "2_2") (pintype "passive"))
    )
    (net (code "156") (name "Net-(R77-Pad1)") (class "Default")
      (node (ref "R77") (pin "1") (pinfunction "1_1") (pintype "passive"))
      (node (ref "R78") (pin "1") (pinfunction "1_1") (pintype "passive"))
    )
    (net (code "157") (name "Net-(R78-Pad2)") (class "Default")
      (node (ref "R78") (pin "2") (pinfunction "2_2") (pintype "passive"))
      (node (ref "R79") (pin "1") (pinfunction "1_1") (pintype "passive"))
    )
    (net (code "158") (name "Net-(R84-Pad2)") (class "Default")
      (node (ref "R84") (pin "2") (pinfunction "2_2") (pintype "passive"))
      (node (ref "R85") (pin "2") (pinfunction "2_2") (pintype "passive"))
    )
    (net (code "159") (name "Net-(R85-Pad1)") (class "Default")
      (node (ref "R85") (pin "1") (pinfunction "1_1") (pintype "passive"))
      (node (ref "R86") (pin "1") (pinfunction "1_1") (pintype "passive"))
    )
    (net (code "160") (name "Net-(R86-Pad2)") (class "Default")
      (node (ref "R86") (pin "2") (pinfunction "2_2") (pintype "passive"))
      (node (ref "R87") (pin "1") (pinfunction "1_1") (pintype "passive"))
    )
    (net (code "161") (name "Net-(R100-Pad2)") (class "Default")
      (node (ref "R100") (pin "2") (pinfunction "2_2") (pintype "passive"))
      (node (ref "R101") (pin "2") (pinfunction "2_2") (pintype "passive"))
    )
    (net (code "162") (name "Net-(R101-Pad1)") (class "Default")
      (node (ref "R101") (pin "1") (pinfunction "1_1") (pintype "passive"))
      (node (ref "R102") (pin "1") (pinfunction "1_1") (pintype "passive"))
    )
    (net (code "163") (name "Net-(R102-Pad2)") (class "Default")
      (node (ref "R102") (pin "2") (pinfunction "2_2") (pintype "passive"))
      (node (ref "R103") (pin "1") (pinfunction "1_1") (pintype "passive"))
    )
    (net (code "164") (name "Net-(R116-Pad2)") (class "Default")
      (node (ref "R116") (pin "2") (pinfunction "2_2") (pintype "passive"))
      (node (ref "R117") (pin "2") (pinfunction "2_2") (pintype "passive"))
    )
    (net (code "165") (name "Net-(R117-Pad1)") (class "Default")
      (node (ref "R117") (pin "1") (pinfunction "1_1") (pintype "passive"))
      (node (ref "R118") (pin "1") (pinfunction "1_1") (pintype "passive"))
    )
    (net (code "166") (name "Net-(R118-Pad2)") (class "Default")
      (node (ref "R118") (pin "2") (pinfunction "2_2") (pintype "passive"))
      (node (ref "R119") (pin "1") (pinfunction "1_1") (pintype "passive"))
    )
    (net (code "167") (name "Net-(T1-D)") (class "Default")
      (node (ref "FAN") (pin "1") (pinfunction "1_1") (pintype "passive"))
      (node (ref "T1") (pin "3") (pinfunction "D_3") (pintype "passive"))
    )
    (net (code "168") (name "Net-(UTX-P$1)") (class "Default")
      (node (ref "R57") (pin "1") (pinfunction "1_1") (pintype "passive"))
      (node (ref "R58") (pin "1") (pinfunction "1_1") (pintype "passive"))
      (node (ref "R91") (pin "2") (pinfunction "2_2") (pintype "passive"))
      (node (ref "R92") (pin "2") (pinfunction "2_2") (pintype "passive"))
      (node (ref "UTX") (pin "TP") (pinfunction "P$1_TP") (pintype "bidirectional"))
    )
    (net (code "169") (name "Net-(X1-2)") (class "Default")
      (node (ref "C59") (pin "1") (pinfunction "1_1") (pintype "passive"))
      (node (ref "R16") (pin "1") (pinfunction "1_1") (pintype "passive"))
      (node (ref "X1") (pin "3") (pinfunction "2_3") (pintype "passive"))
    )
    (net (code "170") (name "OUT_1") (class "Default")
      (node (ref "K1") (pin "4") (pinfunction "4_4") (pintype "passive"))
      (node (ref "K1") (pin "5") (pinfunction "5_5") (pintype "passive"))
      (node (ref "L_OUT1") (pin "1") (pinfunction "MOUNT_1") (pintype "passive"))
      (node (ref "L_OUT1") (pin "2") (pinfunction "MOUNT_2") (pintype "passive"))
      (node (ref "R36") (pin "2") (pinfunction "2_2") (pintype "passive"))
    )
    (net (code "171") (name "OUT_2") (class "Default")
      (node (ref "K2") (pin "4") (pinfunction "4_4") (pintype "passive"))
      (node (ref "K2") (pin "5") (pinfunction "5_5") (pintype "passive"))
      (node (ref "L_OUT2") (pin "1") (pinfunction "MOUNT_1") (pintype "passive"))
      (node (ref "L_OUT2") (pin "2") (pinfunction "MOUNT_2") (pintype "passive"))
      (node (ref "R52") (pin "1") (pinfunction "1_1") (pintype "passive"))
    )
    (net (code "172") (name "OUT_3") (class "Default")
      (node (ref "K3") (pin "4") (pinfunction "4_4") (pintype "passive"))
      (node (ref "K3") (pin "5") (pinfunction "5_5") (pintype "passive"))
      (node (ref "L_OUT3") (pin "1") (pinfunction "MOUNT_1") (pintype "passive"))
      (node (ref "L_OUT3") (pin "2") (pinfunction "MOUNT_2") (pintype "passive"))
      (node (ref "R68") (pin "1") (pinfunction "1_1") (pintype "passive"))
    )
    (net (code "173") (name "OUT_4") (class "Default")
      (node (ref "K4") (pin "4") (pinfunction "4_4") (pintype "passive"))
      (node (ref "K4") (pin "5") (pinfunction "5_5") (pintype "passive"))
      (node (ref "L_OUT4") (pin "1") (pinfunction "MOUNT_1") (pintype "passive"))
      (node (ref "L_OUT4") (pin "2") (pinfunction "MOUNT_2") (pintype "passive"))
      (node (ref "R84") (pin "1") (pinfunction "1_1") (pintype "passive"))
    )
    (net (code "174") (name "OUT_5") (class "Default")
      (node (ref "K5") (pin "4") (pinfunction "4_4") (pintype "passive"))
      (node (ref "K5") (pin "5") (pinfunction "5_5") (pintype "passive"))
      (node (ref "L_OUT5") (pin "1") (pinfunction "MOUNT_1") (pintype "passive"))
      (node (ref "L_OUT5") (pin "2") (pinfunction "MOUNT_2") (pintype "passive"))
      (node (ref "R44") (pin "1") (pinfunction "1_1") (pintype "passive"))
    )
    (net (code "175") (name "OUT_6") (class "Default")
      (node (ref "K6") (pin "4") (pinfunction "4_4") (pintype "passive"))
      (node (ref "K6") (pin "5") (pinfunction "5_5") (pintype "passive"))
      (node (ref "L_OUT6") (pin "1") (pinfunction "MOUNT_1") (pintype "passive"))
      (node (ref "L_OUT6") (pin "2") (pinfunction "MOUNT_2") (pintype "passive"))
      (node (ref "R76") (pin "1") (pinfunction "1_1") (pintype "passive"))
    )
    (net (code "176") (name "OUT_7") (class "Default")
      (node (ref "K7") (pin "4") (pinfunction "4_4") (pintype "passive"))
      (node (ref "K7") (pin "5") (pinfunction "5_5") (pintype "passive"))
      (node (ref "L_OUT7") (pin "1") (pinfunction "MOUNT_1") (pintype "passive"))
      (node (ref "L_OUT7") (pin "2") (pinfunction "MOUNT_2") (pintype "passive"))
      (node (ref "R100") (pin "1") (pinfunction "1_1") (pintype "passive"))
    )
    (net (code "177") (name "OUT_8") (class "Default")
      (node (ref "K8") (pin "4") (pinfunction "4_4") (pintype "passive"))
      (node (ref "K8") (pin "5") (pinfunction "5_5") (pintype "passive"))
      (node (ref "L_OUT8") (pin "1") (pinfunction "MOUNT_1") (pintype "passive"))
      (node (ref "L_OUT8") (pin "2") (pinfunction "MOUNT_2") (pintype "passive"))
      (node (ref "R116") (pin "1") (pinfunction "1_1") (pintype "passive"))
    )
    (net (code "178") (name "QSPI_SCLK") (class "Default")
      (node (ref "IC15") (pin "52") (pinfunction "QSPI_SCLK_52") (pintype "bidirectional"))
      (node (ref "IC18") (pin "6") (pinfunction "CLK_6") (pintype "bidirectional"))
    )
    (net (code "179") (name "QSPI_SD0") (class "Default")
      (node (ref "IC15") (pin "53") (pinfunction "QSPI_SD0_53") (pintype "bidirectional"))
      (node (ref "IC18") (pin "5") (pinfunction "DI/IO0_5") (pintype "bidirectional"))
    )
    (net (code "180") (name "QSPI_SD1") (class "Default")
      (node (ref "IC15") (pin "55") (pinfunction "QSPI_SD1_55") (pintype "bidirectional"))
      (node (ref "IC18") (pin "2") (pinfunction "DO/IO1_2") (pintype "bidirectional"))
    )
    (net (code "181") (name "QSPI_SD2") (class "Default")
      (node (ref "IC15") (pin "54") (pinfunction "QSPI_SD2_54") (pintype "bidirectional"))
      (node (ref "IC18") (pin "3") (pinfunction "~{WP}/IO2_3") (pintype "bidirectional"))
    )
    (net (code "182") (name "QSPI_SD3") (class "Default")
      (node (ref "IC15") (pin "51") (pinfunction "QSPI_SD3_51") (pintype "bidirectional"))
      (node (ref "IC18") (pin "7") (pinfunction "~{HOLD}/IO3_7") (pintype "bidirectional"))
    )
    (net (code "183") (name "RCT") (class "Default")
      (node (ref "C79") (pin "1") (pinfunction "1_1") (pintype "passive"))
      (node (ref "ETH1") (pin "5") (pinfunction "P5/RCT_5") (pintype "passive"))
      (node (ref "R137") (pin "1") (pinfunction "1_1") (pintype "passive"))
      (node (ref "R138") (pin "1") (pinfunction "1_1") (pintype "passive"))
    )
    (net (code "184") (name "RDC_RD_N") (class "Default")
      (node (ref "C81") (pin "1") (pinfunction "1_1") (pintype "passive"))
      (node (ref "R136") (pin "2") (pinfunction "2_2") (pintype "passive"))
      (node (ref "R137") (pin "2") (pinfunction "2_2") (pintype "passive"))
    )
    (net (code "185") (name "RDC_RD_P") (class "Default")
      (node (ref "C82") (pin "1") (pinfunction "1_1") (pintype "passive"))
      (node (ref "R135") (pin "2") (pinfunction "2_2") (pintype "passive"))
      (node (ref "R138") (pin "2") (pinfunction "2_2") (pintype "passive"))
    )
    (net (code "186") (name "RD_N") (class "Default")
      (node (ref "C81") (pin "2") (pinfunction "2_2") (pintype "passive"))
      (node (ref "ETH1") (pin "6") (pinfunction "RD-_6") (pintype "passive"))
    )
    (net (code "187") (name "RD_P") (class "Default")
      (node (ref "C82") (pin "2") (pinfunction "2_2") (pintype "passive"))
      (node (ref "ETH1") (pin "4") (pinfunction "RD+_4") (pintype "passive"))
    )
    (net (code "188") (name "RELAY_1") (class "Default")
      (node (ref "D1") (pin "A") (pinfunction "A_A") (pintype "passive"))
      (node (ref "K1") (pin "1") (pinfunction "1_1") (pintype "passive"))
      (node (ref "R24") (pin "2") (pinfunction "2_2") (pintype "passive"))
    )
    (net (code "189") (name "RELAY_2") (class "Default")
      (node (ref "D2") (pin "A") (pinfunction "A_A") (pintype "passive"))
      (node (ref "K2") (pin "1") (pinfunction "1_1") (pintype "passive"))
      (node (ref "R23") (pin "2") (pinfunction "2_2") (pintype "passive"))
    )
    (net (code "190") (name "RELAY_3") (class "Default")
      (node (ref "D3") (pin "A") (pinfunction "A_A") (pintype "passive"))
      (node (ref "K3") (pin "1") (pinfunction "1_1") (pintype "passive"))
      (node (ref "R22") (pin "2") (pinfunction "2_2") (pintype "passive"))
    )
    (net (code "191") (name "RELAY_4") (class "Default")
      (node (ref "D4") (pin "A") (pinfunction "A_A") (pintype "passive"))
      (node (ref "K4") (pin "1") (pinfunction "1_1") (pintype "passive"))
      (node (ref "R21") (pin "2") (pinfunction "2_2") (pintype "passive"))
    )
    (net (code "192") (name "RELAY_5") (class "Default")
      (node (ref "D5") (pin "A") (pinfunction "A_A") (pintype "passive"))
      (node (ref "K5") (pin "1") (pinfunction "1_1") (pintype "passive"))
      (node (ref "R20") (pin "2") (pinfunction "2_2") (pintype "passive"))
    )
    (net (code "193") (name "RELAY_6") (class "Default")
      (node (ref "D6") (pin "A") (pinfunction "A_A") (pintype "passive"))
      (node (ref "K6") (pin "1") (pinfunction "1_1") (pintype "passive"))
      (node (ref "R19") (pin "2") (pinfunction "2_2") (pintype "passive"))
    )
    (net (code "194") (name "RELAY_7") (class "Default")
      (node (ref "D7") (pin "A") (pinfunction "A_A") (pintype "passive"))
      (node (ref "K7") (pin "1") (pinfunction "1_1") (pintype "passive"))
      (node (ref "R18") (pin "2") (pinfunction "2_2") (pintype "passive"))
    )
    (net (code "195") (name "RELAY_8") (class "Default")
      (node (ref "D8") (pin "A") (pinfunction "A_A") (pintype "passive"))
      (node (ref "K8") (pin "1") (pinfunction "1_1") (pintype "passive"))
      (node (ref "R17") (pin "2") (pinfunction "2_2") (pintype "passive"))
    )
    (net (code "196") (name "REL_0") (class "Default")
      (node (ref "IC3") (pin "8") (pinfunction "8B_8") (pintype "bidirectional"))
      (node (ref "IC4") (pin "17") (pinfunction "IO1.0_17") (pintype "bidirectional"))
      (node (ref "REL0") (pin "TP") (pinfunction "P$1_TP") (pintype "bidirectional"))
      (node (ref "RN1") (pin "A2") (pinfunction "2_A2") (pintype "passive"))
    )
    (net (code "197") (name "REL_1") (class "Default")
      (node (ref "IC3") (pin "7") (pinfunction "7B_7") (pintype "bidirectional"))
      (node (ref "IC4") (pin "18") (pinfunction "IO1.1_18") (pintype "bidirectional"))
      (node (ref "REL1") (pin "TP") (pinfunction "P$1_TP") (pintype "bidirectional"))
      (node (ref "RN1") (pin "B2") (pinfunction "2_B2") (pintype "passive"))
    )
    (net (code "198") (name "REL_2") (class "Default")
      (node (ref "IC3") (pin "6") (pinfunction "6B_6") (pintype "bidirectional"))
      (node (ref "IC4") (pin "19") (pinfunction "IO1.2_19") (pintype "bidirectional"))
      (node (ref "REL2") (pin "TP") (pinfunction "P$1_TP") (pintype "bidirectional"))
      (node (ref "RN1") (pin "C2") (pinfunction "2_C2") (pintype "passive"))
    )
    (net (code "199") (name "REL_3") (class "Default")
      (node (ref "IC3") (pin "5") (pinfunction "5B_5") (pintype "bidirectional"))
      (node (ref "IC4") (pin "20") (pinfunction "IO1.3_20") (pintype "bidirectional"))
      (node (ref "REL3") (pin "TP") (pinfunction "P$1_TP") (pintype "bidirectional"))
      (node (ref "RN1") (pin "D2") (pinfunction "2_D2") (pintype "passive"))
    )
    (net (code "200") (name "REL_4") (class "Default")
      (node (ref "IC3") (pin "4") (pinfunction "4B_4") (pintype "bidirectional"))
      (node (ref "IC4") (pin "21") (pinfunction "IO1.4_21") (pintype "bidirectional"))
      (node (ref "REL4") (pin "TP") (pinfunction "P$1_TP") (pintype "bidirectional"))
      (node (ref "RN2") (pin "A2") (pinfunction "2_A2") (pintype "passive"))
    )
    (net (code "201") (name "REL_5") (class "Default")
      (node (ref "IC3") (pin "3") (pinfunction "3B_3") (pintype "bidirectional"))
      (node (ref "IC4") (pin "22") (pinfunction "IO1.5_22") (pintype "bidirectional"))
      (node (ref "REL5") (pin "TP") (pinfunction "P$1_TP") (pintype "bidirectional"))
      (node (ref "RN2") (pin "B2") (pinfunction "2_B2") (pintype "passive"))
    )
    (net (code "202") (name "REL_6") (class "Default")
      (node (ref "IC3") (pin "2") (pinfunction "2B_2") (pintype "bidirectional"))
      (node (ref "IC4") (pin "23") (pinfunction "IO1.6_23") (pintype "bidirectional"))
      (node (ref "REL6") (pin "TP") (pinfunction "P$1_TP") (pintype "bidirectional"))
      (node (ref "RN2") (pin "C2") (pinfunction "2_C2") (pintype "passive"))
    )
    (net (code "203") (name "REL_7") (class "Default")
      (node (ref "IC3") (pin "1") (pinfunction "1B_1") (pintype "bidirectional"))
      (node (ref "IC4") (pin "24") (pinfunction "IO1.7_24") (pintype "bidirectional"))
      (node (ref "REL7") (pin "TP") (pinfunction "P$1_TP") (pintype "bidirectional"))
      (node (ref "RN2") (pin "D2") (pinfunction "2_D2") (pintype "passive"))
    )
    (net (code "204") (name "RP_XI") (class "Default")
      (node (ref "C58") (pin "1") (pinfunction "1_1") (pintype "passive"))
      (node (ref "IC15") (pin "20") (pinfunction "XIN_20") (pintype "bidirectional"))
      (node (ref "X1") (pin "1") (pinfunction "1_1") (pintype "passive"))
    )
    (net (code "205") (name "RP_XO") (class "Default")
      (node (ref "IC15") (pin "21") (pinfunction "XOUT_21") (pintype "bidirectional"))
      (node (ref "R16") (pin "2") (pinfunction "2_2") (pintype "passive"))
    )
    (net (code "206") (name "RUN") (class "Default")
      (node (ref "GDRC") (pin "2") (pinfunction "P$2_2") (pintype "bidirectional"))
      (node (ref "IC15") (pin "26") (pinfunction "RUN_26") (pintype "bidirectional"))
      (node (ref "R132") (pin "2") (pinfunction "2_2") (pintype "passive"))
      (node (ref "RES") (pin "2") (pinfunction "P$2_2") (pintype "bidirectional"))
      (node (ref "RST") (pin "TP") (pinfunction "P$1_TP") (pintype "bidirectional"))
    )
    (net (code "207") (name "RX_RD_N") (class "Default")
      (node (ref "IC20") (pin "5") (pinfunction "RXN_5") (pintype "input"))
      (node (ref "R136") (pin "1") (pinfunction "1_1") (pintype "passive"))
    )
    (net (code "208") (name "RX_RD_P") (class "Default")
      (node (ref "IC20") (pin "6") (pinfunction "RXP_6") (pintype "input"))
      (node (ref "R135") (pin "1") (pinfunction "1_1") (pintype "passive"))
    )
    (net (code "209") (name "SH") (class "Default")
      (node (ref "C78") (pin "1") (pinfunction "1_1") (pintype "passive"))
      (node (ref "C83") (pin "2") (pinfunction "2_2") (pintype "passive"))
      (node (ref "ETH1") (pin "13") (pinfunction "SHIELD_13") (pintype "passive"))
      (node (ref "ETH1") (pin "14") (pinfunction "SHIELD_14") (pintype "passive"))
      (node (ref "R110") (pin "2") (pinfunction "2_2") (pintype "passive"))
      (node (ref "R131") (pin "1") (pinfunction "1_1") (pintype "passive"))
      (node (ref "USB1") (pin "SHLD1") (pinfunction "SHILED_SHLD1") (pintype "power_in"))
      (node (ref "USB1") (pin "SHLD2") (pinfunction "SHILED_SHLD2") (pintype "power_in"))
      (node (ref "USB1") (pin "SHLD3") (pinfunction "SHILED_SHLD3") (pintype "power_in"))
      (node (ref "USB1") (pin "SHLD4") (pinfunction "SHILED_SHLD4") (pintype "power_in"))
    )
    (net (code "210") (name "SRC1") (class "Default")
      (node (ref "C21") (pin "1") (pinfunction "1_1") (pintype "passive"))
      (node (ref "C22") (pin "1") (pinfunction "1_1") (pintype "passive"))
      (node (ref "C5") (pin "1") (pinfunction "1_1") (pintype "passive"))
      (node (ref "D11") (pin "C") (pinfunction "C_C") (pintype "passive"))
      (node (ref "IC13") (pin "3") (pinfunction "SRC2_3") (pintype "output"))
      (node (ref "IC13") (pin "4") (pinfunction "SRC_4") (pintype "output"))
      (node (ref "L3") (pin "1") (pinfunction "1_1") (pintype "passive"))
      (node (ref "R60") (pin "2") (pinfunction "2_2") (pintype "passive"))
    )
    (net (code "211") (name "SRC2") (class "Default")
      (node (ref "C46") (pin "1") (pinfunction "1_1") (pintype "passive"))
      (node (ref "C51") (pin "1") (pinfunction "1_1") (pintype "passive"))
      (node (ref "C52") (pin "1") (pinfunction "1_1") (pintype "passive"))
      (node (ref "D14") (pin "C") (pinfunction "C_C") (pintype "passive"))
      (node (ref "IC5") (pin "3") (pinfunction "SRC2_3") (pintype "output"))
      (node (ref "IC5") (pin "4") (pinfunction "SRC_4") (pintype "output"))
      (node (ref "L5") (pin "1") (pinfunction "1_1") (pintype "passive"))
      (node (ref "R107") (pin "2") (pinfunction "2_2") (pintype "passive"))
    )
    (net (code "212") (name "SWCLK") (class "Default")
      (node (ref "GDRC") (pin "1") (pinfunction "P$1_1") (pintype "bidirectional"))
      (node (ref "IC15") (pin "24") (pinfunction "SWCLK_24") (pintype "bidirectional"))
    )
    (net (code "213") (name "SWDIO") (class "Default")
      (node (ref "GDRC") (pin "3") (pinfunction "P$3_3") (pintype "bidirectional"))
      (node (ref "IC15") (pin "25") (pinfunction "SWDIO_25") (pintype "bidirectional"))
    )
    (net (code "214") (name "TCT") (class "Default")
      (node (ref "C80") (pin "1") (pinfunction "1_1") (pintype "passive"))
      (node (ref "ETH1") (pin "2") (pinfunction "P4/TCT_2") (pintype "passive"))
      (node (ref "R146") (pin "1") (pinfunction "1_1") (pintype "passive"))
    )
    (net (code "215") (name "TD_N") (class "Default")
      (node (ref "ETH1") (pin "3") (pinfunction "TD-_3") (pintype "passive"))
      (node (ref "R134") (pin "2") (pinfunction "2_2") (pintype "passive"))
      (node (ref "R140") (pin "1") (pinfunction "1_1") (pintype "passive"))
    )
    (net (code "216") (name "TD_P") (class "Default")
      (node (ref "ETH1") (pin "1") (pinfunction "TD+_1") (pintype "passive"))
      (node (ref "R133") (pin "2") (pinfunction "2_2") (pintype "passive"))
      (node (ref "R139") (pin "1") (pinfunction "1_1") (pintype "passive"))
    )
    (net (code "217") (name "TX_CH1") (class "Default")
      (node (ref "IC6") (pin "6") (pinfunction "TX_6") (pintype "bidirectional"))
      (node (ref "R155") (pin "1") (pinfunction "1_1") (pintype "passive"))
    )
    (net (code "218") (name "TX_CH2") (class "Default")
      (node (ref "IC8") (pin "6") (pinfunction "TX_6") (pintype "bidirectional"))
      (node (ref "R154") (pin "1") (pinfunction "1_1") (pintype "passive"))
    )
    (net (code "219") (name "TX_CH3") (class "Default")
      (node (ref "IC10") (pin "6") (pinfunction "TX_6") (pintype "bidirectional"))
      (node (ref "R153") (pin "1") (pinfunction "1_1") (pintype "passive"))
    )
    (net (code "220") (name "TX_CH4") (class "Default")
      (node (ref "IC12") (pin "6") (pinfunction "TX_6") (pintype "bidirectional"))
      (node (ref "R59") (pin "1") (pinfunction "1_1") (pintype "passive"))
    )
    (net (code "221") (name "TX_CH5") (class "Default")
      (node (ref "IC7") (pin "6") (pinfunction "TX_6") (pintype "bidirectional"))
      (node (ref "R159") (pin "1") (pinfunction "1_1") (pintype "passive"))
    )
    (net (code "222") (name "TX_CH6") (class "Default")
      (node (ref "IC11") (pin "6") (pinfunction "TX_6") (pintype "bidirectional"))
      (node (ref "R158") (pin "1") (pinfunction "1_1") (pintype "passive"))
    )
    (net (code "223") (name "TX_CH7") (class "Default")
      (node (ref "IC14") (pin "6") (pinfunction "TX_6") (pintype "bidirectional"))
      (node (ref "R157") (pin "1") (pinfunction "1_1") (pintype "passive"))
    )
    (net (code "224") (name "TX_CH8") (class "Default")
      (node (ref "IC16") (pin "6") (pinfunction "TX_6") (pintype "bidirectional"))
      (node (ref "R156") (pin "1") (pinfunction "1_1") (pintype "passive"))
    )
    (net (code "225") (name "TX_MUX1") (class "Default")
      (node (ref "IC9") (pin "4") (pinfunction "D0_4") (pintype "bidirectional"))
      (node (ref "OPT1") (pin "10") (pinfunction "10_10") (pintype "passive"))
      (node (ref "R89") (pin "D1") (pinfunction "4_D1") (pintype "passive"))
    )
    (net (code "226") (name "TX_MUX2") (class "Default")
      (node (ref "IC9") (pin "3") (pinfunction "D1_3") (pintype "bidirectional"))
      (node (ref "OPT1") (pin "12") (pinfunction "12_12") (pintype "passive"))
      (node (ref "R89") (pin "C1") (pinfunction "3_C1") (pintype "passive"))
    )
    (net (code "227") (name "TX_MUX3") (class "Default")
      (node (ref "IC9") (pin "2") (pinfunction "D2_2") (pintype "bidirectional"))
      (node (ref "OPT1") (pin "14") (pinfunction "14_14") (pintype "passive"))
      (node (ref "R89") (pin "B1") (pinfunction "2_B1") (pintype "passive"))
    )
    (net (code "228") (name "TX_MUX4") (class "Default")
      (node (ref "IC9") (pin "1") (pinfunction "D3_1") (pintype "bidirectional"))
      (node (ref "OPT1") (pin "16") (pinfunction "16_16") (pintype "passive"))
      (node (ref "R89") (pin "A1") (pinfunction "1_A1") (pintype "passive"))
    )
    (net (code "229") (name "TX_MUX5") (class "Default")
      (node (ref "IC9") (pin "15") (pinfunction "D4_15") (pintype "bidirectional"))
      (node (ref "OPT2") (pin "10") (pinfunction "10_10") (pintype "passive"))
      (node (ref "R90") (pin "A1") (pinfunction "1_A1") (pintype "passive"))
    )
    (net (code "230") (name "TX_MUX6") (class "Default")
      (node (ref "IC9") (pin "14") (pinfunction "D5_14") (pintype "bidirectional"))
      (node (ref "OPT2") (pin "12") (pinfunction "12_12") (pintype "passive"))
      (node (ref "R90") (pin "B1") (pinfunction "2_B1") (pintype "passive"))
    )
    (net (code "231") (name "TX_MUX7") (class "Default")
      (node (ref "IC9") (pin "13") (pinfunction "D6_13") (pintype "bidirectional"))
      (node (ref "OPT2") (pin "14") (pinfunction "14_14") (pintype "passive"))
      (node (ref "R90") (pin "C1") (pinfunction "3_C1") (pintype "passive"))
    )
    (net (code "232") (name "TX_MUX8") (class "Default")
      (node (ref "IC9") (pin "12") (pinfunction "D7_12") (pintype "bidirectional"))
      (node (ref "OPT2") (pin "16") (pinfunction "16_16") (pintype "passive"))
      (node (ref "R90") (pin "D1") (pinfunction "4_D1") (pintype "passive"))
    )
    (net (code "233") (name "TX_OUT") (class "Default")
      (node (ref "IC9") (pin "5") (pinfunction "Y_5") (pintype "bidirectional"))
      (node (ref "R91") (pin "1") (pinfunction "1_1") (pintype "passive"))
    )
    (net (code "234") (name "TX_TD_N") (class "Default")
      (node (ref "IC20") (pin "1") (pinfunction "TXN_1") (pintype "output"))
      (node (ref "R134") (pin "1") (pinfunction "1_1") (pintype "passive"))
    )
    (net (code "235") (name "TX_TD_P") (class "Default")
      (node (ref "IC20") (pin "2") (pinfunction "TXP_2") (pintype "output"))
      (node (ref "R133") (pin "1") (pinfunction "1_1") (pintype "passive"))
    )
    (net (code "236") (name "UART0_RX") (class "Default")
      (node (ref "IC15") (pin "2") (pinfunction "GPIO0_2") (pintype "bidirectional"))
      (node (ref "R58") (pin "2") (pinfunction "2_2") (pintype "passive"))
      (node (ref "RGTG") (pin "1") (pinfunction "P$1_1") (pintype "bidirectional"))
      (node (ref "RX0") (pin "TP") (pinfunction "P$1_TP") (pintype "bidirectional"))
    )
    (net (code "237") (name "UART0_TX") (class "Default")
      (node (ref "IC15") (pin "3") (pinfunction "GPIO1_3") (pintype "bidirectional"))
      (node (ref "R57") (pin "2") (pinfunction "2_2") (pintype "passive"))
      (node (ref "RGTG") (pin "3") (pinfunction "P$3_3") (pintype "bidirectional"))
      (node (ref "TX0") (pin "TP") (pinfunction "P$1_TP") (pintype "bidirectional"))
    )
    (net (code "238") (name "USB2_DP_N") (class "Default")
      (node (ref "ESD1") (pin "3") (pinfunction "C2_3") (pintype "bidirectional"))
      (node (ref "R15") (pin "1") (pinfunction "1_1") (pintype "passive"))
      (node (ref "USB1") (pin "A7") (pinfunction "D-_A7") (pintype "bidirectional"))
      (node (ref "USB1") (pin "B7") (pinfunction "D-_B7") (pintype "bidirectional"))
    )
    (net (code "239") (name "USB2_DP_P") (class "Default")
      (node (ref "ESD1") (pin "2") (pinfunction "C1_2") (pintype "bidirectional"))
      (node (ref "R160") (pin "1") (pinfunction "1_1") (pintype "passive"))
      (node (ref "USB1") (pin "A6") (pinfunction "D+_A6") (pintype "bidirectional"))
      (node (ref "USB1") (pin "B6") (pinfunction "D+_B6") (pintype "bidirectional"))
    )
    (net (code "240") (name "USB_BOOT") (class "Default")
      (node (ref "BOOT") (pin "TP") (pinfunction "P$1_TP") (pintype "bidirectional"))
      (node (ref "BT") (pin "1") (pinfunction "P$1_1") (pintype "bidirectional"))
      (node (ref "R112") (pin "1") (pinfunction "1_1") (pintype "passive"))
    )
    (net (code "241") (name "USB_VBUS") (class "Default")
      (node (ref "R121") (pin "1") (pinfunction "1_1") (pintype "passive"))
      (node (ref "R126") (pin "1") (pinfunction "1_1") (pintype "passive"))
      (node (ref "R170") (pin "1") (pinfunction "1_1") (pintype "passive"))
      (node (ref "USB1") (pin "VBUS1") (pinfunction "VBUS_VBUS1") (pintype "power_in"))
      (node (ref "USB1") (pin "VBUS2") (pinfunction "VBUS_VBUS2") (pintype "power_in"))
    )
    (net (code "242") (name "VBUS") (class "Default")
      (node (ref "C65") (pin "1") (pinfunction "1_1") (pintype "passive"))
      (node (ref "C66") (pin "1") (pinfunction "1_1") (pintype "passive"))
      (node (ref "C97") (pin "1") (pinfunction "1_1") (pintype "passive"))
      (node (ref "C98") (pin "1") (pinfunction "1_1") (pintype "passive"))
      (node (ref "D15") (pin "C") (pinfunction "C_C") (pintype "passive"))
      (node (ref "ESD1") (pin "4") (pinfunction "C3_4") (pintype "bidirectional"))
      (node (ref "IC21") (pin "1") (pinfunction "VIN_1") (pintype "bidirectional"))
      (node (ref "IC21") (pin "3") (pinfunction "EN_3") (pintype "bidirectional"))
      (node (ref "R170") (pin "2") (pinfunction "2_2") (pintype "passive"))
      (node (ref "VBUS") (pin "TP") (pinfunction "P$1_TP") (pintype "bidirectional"))
    )
    (net (code "243") (name "VNI1") (class "Default")
      (node (ref "C21") (pin "2") (pinfunction "2_2") (pintype "passive"))
      (node (ref "IC13") (pin "1") (pinfunction "VCC_1") (pintype "output"))
      (node (ref "VCC") (pin "TP") (pinfunction "P$1_TP") (pintype "bidirectional"))
    )
    (net (code "244") (name "VNI2") (class "Default")
      (node (ref "C46") (pin "2") (pinfunction "2_2") (pintype "passive"))
      (node (ref "IC5") (pin "1") (pinfunction "VCC_1") (pintype "output"))
      (node (ref "VCC2") (pin "TP") (pinfunction "P$1_TP") (pintype "bidirectional"))
    )
    (net (code "245") (name "W5500_MISO") (class "Default")
      (node (ref "IC15") (pin "27") (pinfunction "GPIO16_27") (pintype "bidirectional"))
      (node (ref "IC20") (pin "34") (pinfunction "MISO_34") (pintype "output"))
      (node (ref "MISO1") (pin "TP") (pinfunction "P$1_TP") (pintype "bidirectional"))
    )
    (net (code "246") (name "W5500_MOSI") (class "Default")
      (node (ref "IC15") (pin "30") (pinfunction "GPIO19_30") (pintype "bidirectional"))
      (node (ref "IC20") (pin "35") (pinfunction "MOSI_35") (pintype "input"))
      (node (ref "MOSI1") (pin "TP") (pinfunction "P$1_TP") (pintype "bidirectional"))
    )
    (net (code "247") (name "W5500_SCK") (class "Default")
      (node (ref "IC15") (pin "29") (pinfunction "GPIO18_29") (pintype "bidirectional"))
      (node (ref "IC20") (pin "33") (pinfunction "SCLK_33") (pintype "input"))
      (node (ref "SCLK1") (pin "TP") (pinfunction "P$1_TP") (pintype "bidirectional"))
    )
    (net (code "248") (name "unconnected-(IC4-INTA-Pad16)") (class "Default")
      (node (ref "IC4") (pin "16") (pinfunction "INTA_16") (pintype "bidirectional"))
    )
    (net (code "249") (name "unconnected-(IC4-INTB-Pad15)") (class "Default")
      (node (ref "IC4") (pin "15") (pinfunction "INTB_15") (pintype "bidirectional"))
    )
    (net (code "250") (name "unconnected-(IC4-IO2.4-Pad1)") (class "Default")
      (node (ref "IC4") (pin "1") (pinfunction "IO2.4_1") (pintype "bidirectional"))
    )
    (net (code "251") (name "unconnected-(IC4-IO2.5-Pad2)") (class "Default")
      (node (ref "IC4") (pin "2") (pinfunction "IO2.5_2") (pintype "bidirectional"))
    )
    (net (code "252") (name "unconnected-(IC4-IO2.6-Pad3)") (class "Default")
      (node (ref "IC4") (pin "3") (pinfunction "IO2.6_3") (pintype "bidirectional"))
    )
    (net (code "253") (name "unconnected-(IC4-IO2.7-Pad4)") (class "Default")
      (node (ref "IC4") (pin "4") (pinfunction "IO2.7_4") (pintype "bidirectional"))
    )
    (net (code "254") (name "unconnected-(IC6-PF-Pad7)") (class "Default")
      (node (ref "IC6") (pin "7") (pinfunction "PF_7") (pintype "bidirectional"))
    )
    (net (code "255") (name "unconnected-(IC6-RX-Pad8)") (class "Default")
      (node (ref "IC6") (pin "8") (pinfunction "RX_8") (pintype "bidirectional"))
    )
    (net (code "256") (name "unconnected-(IC7-PF-Pad7)") (class "Default")
      (node (ref "IC7") (pin "7") (pinfunction "PF_7") (pintype "bidirectional"))
    )
    (net (code "257") (name "unconnected-(IC7-RX-Pad8)") (class "Default")
      (node (ref "IC7") (pin "8") (pinfunction "RX_8") (pintype "bidirectional"))
    )
    (net (code "258") (name "unconnected-(IC8-PF-Pad7)") (class "Default")
      (node (ref "IC8") (pin "7") (pinfunction "PF_7") (pintype "bidirectional"))
    )
    (net (code "259") (name "unconnected-(IC8-RX-Pad8)") (class "Default")
      (node (ref "IC8") (pin "8") (pinfunction "RX_8") (pintype "bidirectional"))
    )
    (net (code "260") (name "unconnected-(IC10-PF-Pad7)") (class "Default")
      (node (ref "IC10") (pin "7") (pinfunction "PF_7") (pintype "bidirectional"))
    )
    (net (code "261") (name "unconnected-(IC10-RX-Pad8)") (class "Default")
      (node (ref "IC10") (pin "8") (pinfunction "RX_8") (pintype "bidirectional"))
    )
    (net (code "262") (name "unconnected-(IC11-PF-Pad7)") (class "Default")
      (node (ref "IC11") (pin "7") (pinfunction "PF_7") (pintype "bidirectional"))
    )
    (net (code "263") (name "unconnected-(IC11-RX-Pad8)") (class "Default")
      (node (ref "IC11") (pin "8") (pinfunction "RX_8") (pintype "bidirectional"))
    )
    (net (code "264") (name "unconnected-(IC12-PF-Pad7)") (class "Default")
      (node (ref "IC12") (pin "7") (pinfunction "PF_7") (pintype "bidirectional"))
    )
    (net (code "265") (name "unconnected-(IC12-RX-Pad8)") (class "Default")
      (node (ref "IC12") (pin "8") (pinfunction "RX_8") (pintype "bidirectional"))
    )
    (net (code "266") (name "unconnected-(IC14-PF-Pad7)") (class "Default")
      (node (ref "IC14") (pin "7") (pinfunction "PF_7") (pintype "bidirectional"))
    )
    (net (code "267") (name "unconnected-(IC14-RX-Pad8)") (class "Default")
      (node (ref "IC14") (pin "8") (pinfunction "RX_8") (pintype "bidirectional"))
    )
    (net (code "268") (name "unconnected-(IC16-PF-Pad7)") (class "Default")
      (node (ref "IC16") (pin "7") (pinfunction "PF_7") (pintype "bidirectional"))
    )
    (net (code "269") (name "unconnected-(IC16-RX-Pad8)") (class "Default")
      (node (ref "IC16") (pin "8") (pinfunction "RX_8") (pintype "bidirectional"))
    )
    (net (code "270") (name "unconnected-(IC20-DNC-Pad7)") (class "Default")
      (node (ref "IC20") (pin "7") (pinfunction "DNC_7") (pintype "bidirectional"))
    )
    (net (code "271") (name "unconnected-(IC20-DUPLED-Pad26)") (class "Default")
      (node (ref "IC20") (pin "26") (pinfunction "DUPLED_26") (pintype "output"))
    )
    (net (code "272") (name "unconnected-(IC20-RSVD1-Pad23)") (class "Default")
      (node (ref "IC20") (pin "23") (pinfunction "RSVD1_23") (pintype "input"))
    )
    (net (code "273") (name "unconnected-(IC20-RSVD2-Pad38)") (class "Default")
      (node (ref "IC20") (pin "38") (pinfunction "RSVD2_38") (pintype "input"))
    )
    (net (code "274") (name "unconnected-(IC20-RSVD3-Pad39)") (class "Default")
      (node (ref "IC20") (pin "39") (pinfunction "RSVD3_39") (pintype "input"))
    )
    (net (code "275") (name "unconnected-(IC20-RSVD4-Pad40)") (class "Default")
      (node (ref "IC20") (pin "40") (pinfunction "RSVD4_40") (pintype "input"))
    )
    (net (code "276") (name "unconnected-(IC20-RSVD5-Pad41)") (class "Default")
      (node (ref "IC20") (pin "41") (pinfunction "RSVD5_41") (pintype "input"))
    )
    (net (code "277") (name "unconnected-(IC20-RSVD6-Pad42)") (class "Default")
      (node (ref "IC20") (pin "42") (pinfunction "RSVD6_42") (pintype "input"))
    )
    (net (code "278") (name "unconnected-(IC20-SPDLED-Pad24)") (class "Default")
      (node (ref "IC20") (pin "24") (pinfunction "SPDLED_24") (pintype "output"))
    )
    (net (code "279") (name "unconnected-(IC20-VBG-Pad18)") (class "Default")
      (node (ref "IC20") (pin "18") (pinfunction "VBG_18") (pintype "output"))
    )
    (net (code "280") (name "unconnected-(IC21-NC-Pad4)") (class "Default")
      (node (ref "IC21") (pin "4") (pinfunction "NC_4") (pintype "bidirectional"))
    )
    (net (code "281") (name "unconnected-(R149-5-PadD2)") (class "Default")
      (node (ref "R149") (pin "D2") (pinfunction "5_D2") (pintype "passive"))
    )
    (net (code "282") (name "unconnected-(USB1-SBU1-PadA8)") (class "Default")
      (node (ref "USB1") (pin "A8") (pinfunction "SBU1_A8") (pintype "bidirectional"))
    )
    (net (code "283") (name "unconnected-(USB1-SBU2-PadB8)") (class "Default")
      (node (ref "USB1") (pin "B8") (pinfunction "SBU2_B8") (pintype "bidirectional"))
    )
    (net (code "284") (name "~{ACT}") (class "Default")
      (node (ref "IC20") (pin "27") (pinfunction "ACTLED_27") (pintype "output"))
      (node (ref "R142") (pin "1") (pinfunction "1_1") (pintype "passive"))
    )
    (net (code "285") (name "~{LINK}") (class "Default")
      (node (ref "IC20") (pin "25") (pinfunction "LINKLED_25") (pintype "output"))
      (node (ref "R141") (pin "1") (pinfunction "1_1") (pintype "passive"))
    )
    (net (code "286") (name "~{QSPI_SS}") (class "Default")
      (node (ref "IC15") (pin "56") (pinfunction "QSPI_SS_N_56") (pintype "bidirectional"))
      (node (ref "IC18") (pin "1") (pinfunction "~{CS}_1") (pintype "bidirectional"))
      (node (ref "R111") (pin "1") (pinfunction "1_1") (pintype "passive"))
      (node (ref "R112") (pin "2") (pinfunction "2_2") (pintype "passive"))
    )
    (net (code "287") (name "~{TX_OUT}") (class "Default")
      (node (ref "IC22") (pin "3") (pinfunction "+IN_3") (pintype "input"))
      (node (ref "IC9") (pin "6") (pinfunction "~{Y}_6") (pintype "bidirectional"))
      (node (ref "R92") (pin "1") (pinfunction "1_1") (pintype "passive"))
    )
    (net (code "288") (name "~{W5500_CS}") (class "Default")
      (node (ref "CS1") (pin "TP") (pinfunction "P$1_TP") (pintype "bidirectional"))
      (node (ref "IC15") (pin "28") (pinfunction "GPIO17_28") (pintype "bidirectional"))
      (node (ref "IC20") (pin "32") (pinfunction "~{SCSN}_32") (pintype "input"))
    )
    (net (code "289") (name "~{W5500_INT}") (class "Default")
      (node (ref "IC15") (pin "32") (pinfunction "GPIO21_32") (pintype "bidirectional"))
      (node (ref "IC20") (pin "36") (pinfunction "~{INTN}_36") (pintype "input"))
    )
    (net (code "290") (name "~{W5500_RST}") (class "Default")
      (node (ref "IC15") (pin "31") (pinfunction "GPIO20_31") (pintype "bidirectional"))
      (node (ref "IC20") (pin "37") (pinfunction "~{RSTN}_37") (pintype "input"))
      (node (ref "R145") (pin "1") (pinfunction "1_1") (pintype "passive"))
    )
  )
)
